# quantum_AnalougeEngine_V6_1.net
KiCad netlist of a schematic drawn in EAGLE
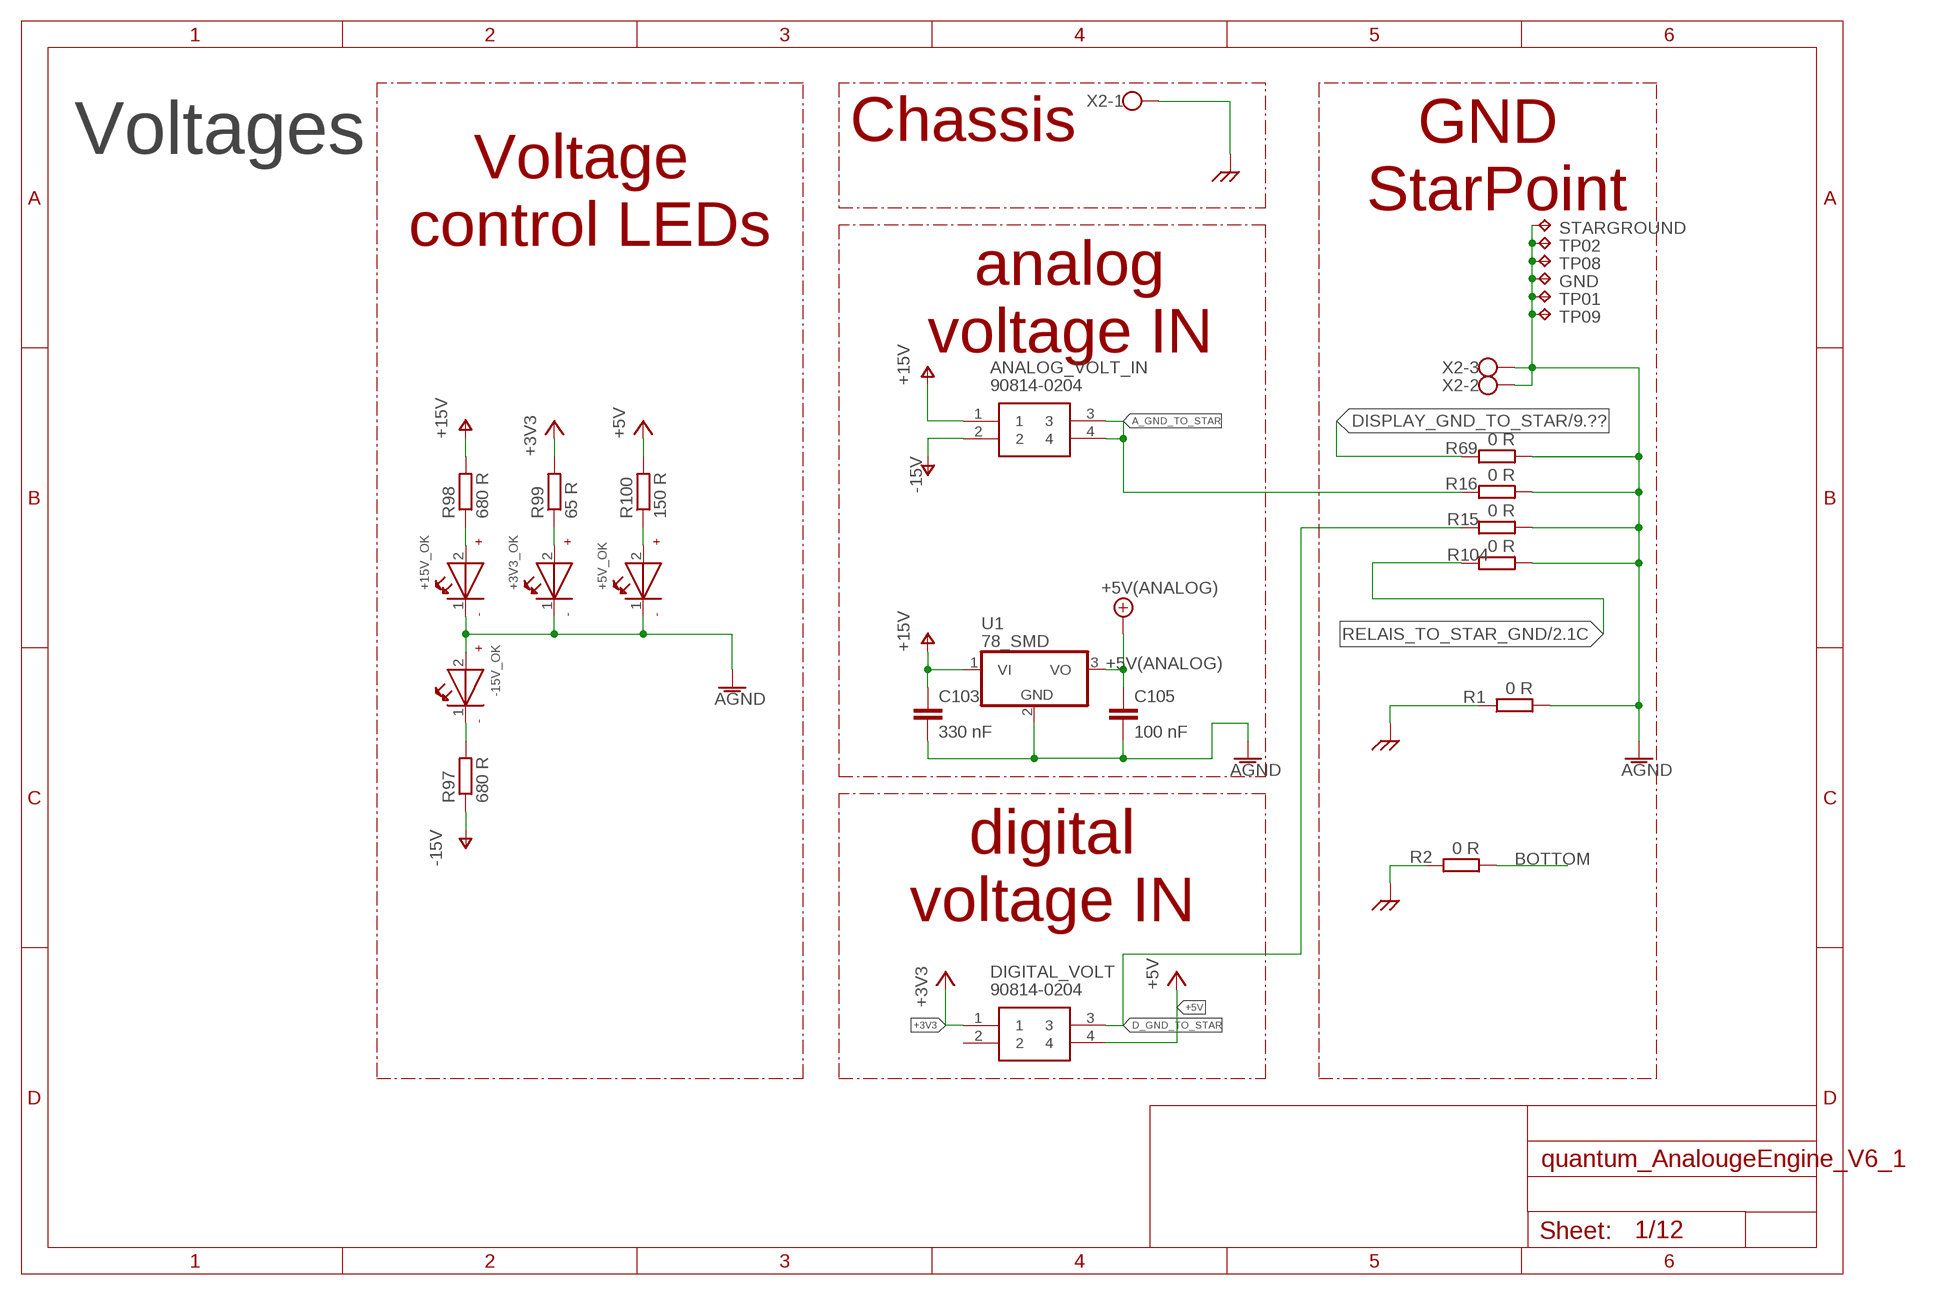
[diagram p0: schematic, sheet 1]
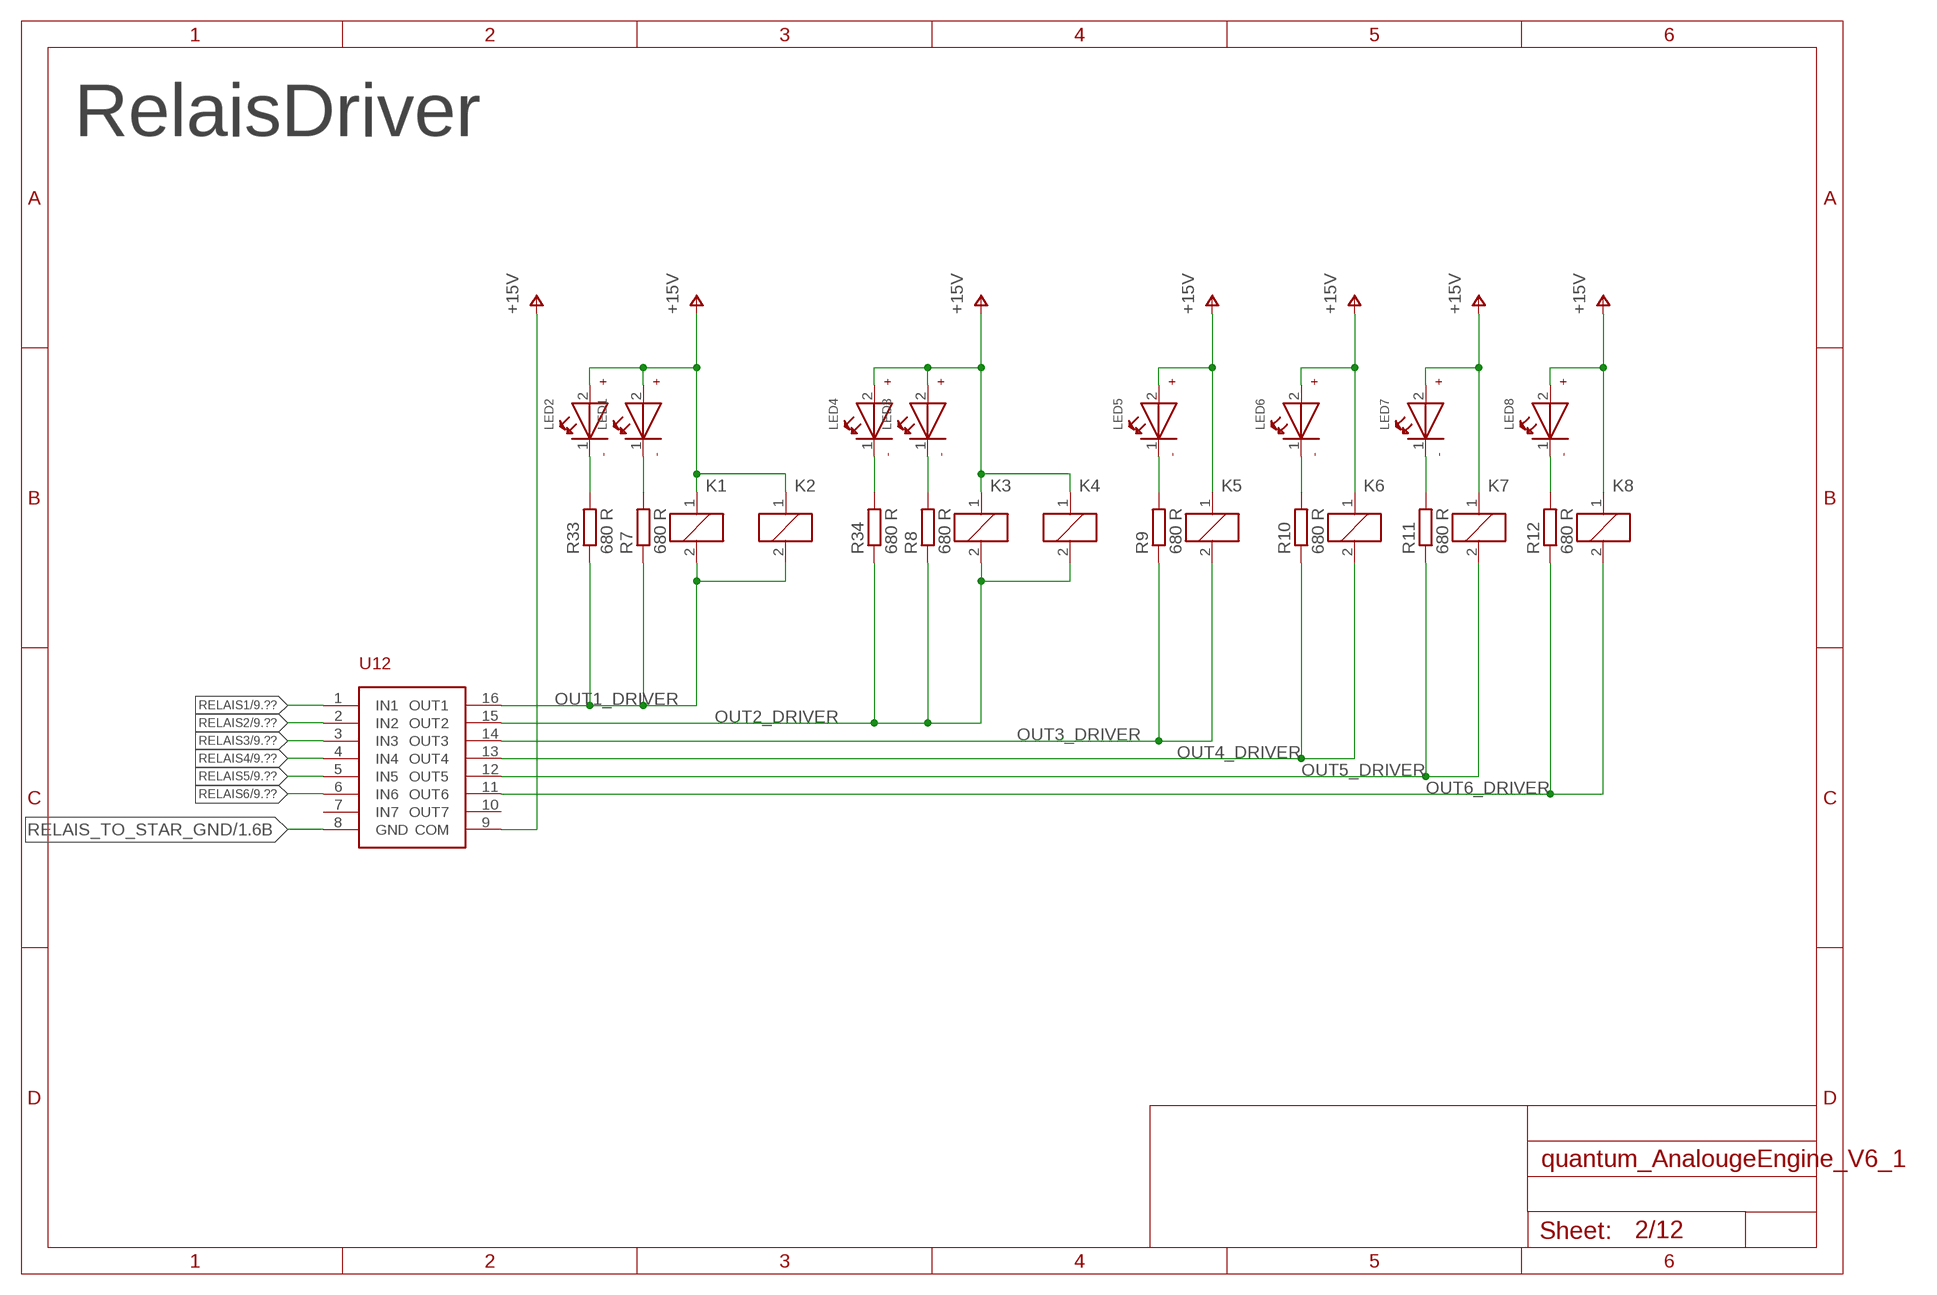
[diagram p1: schematic, sheet 2]
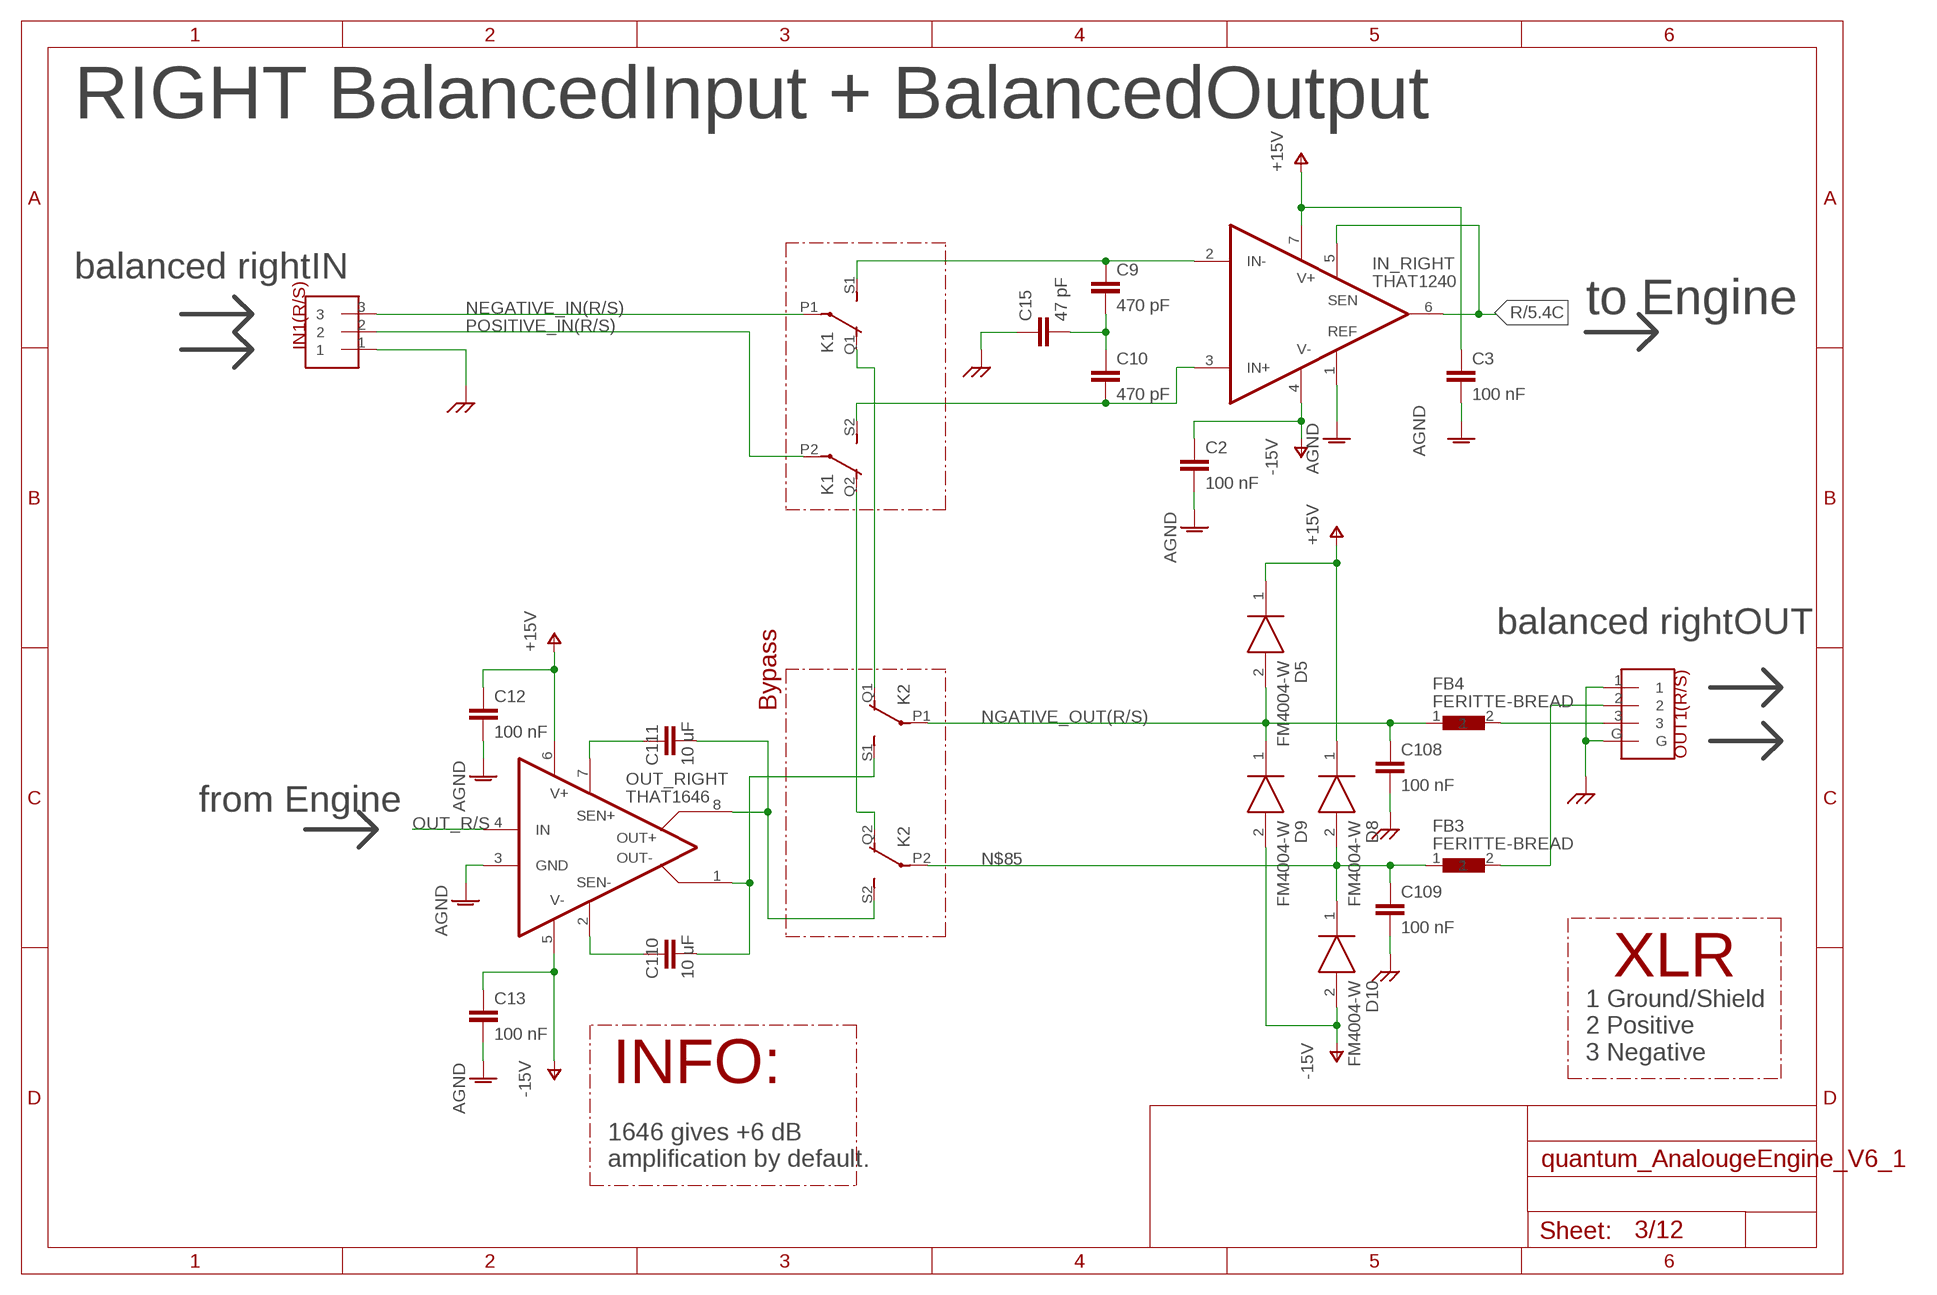
[diagram p2: schematic, sheet 3]
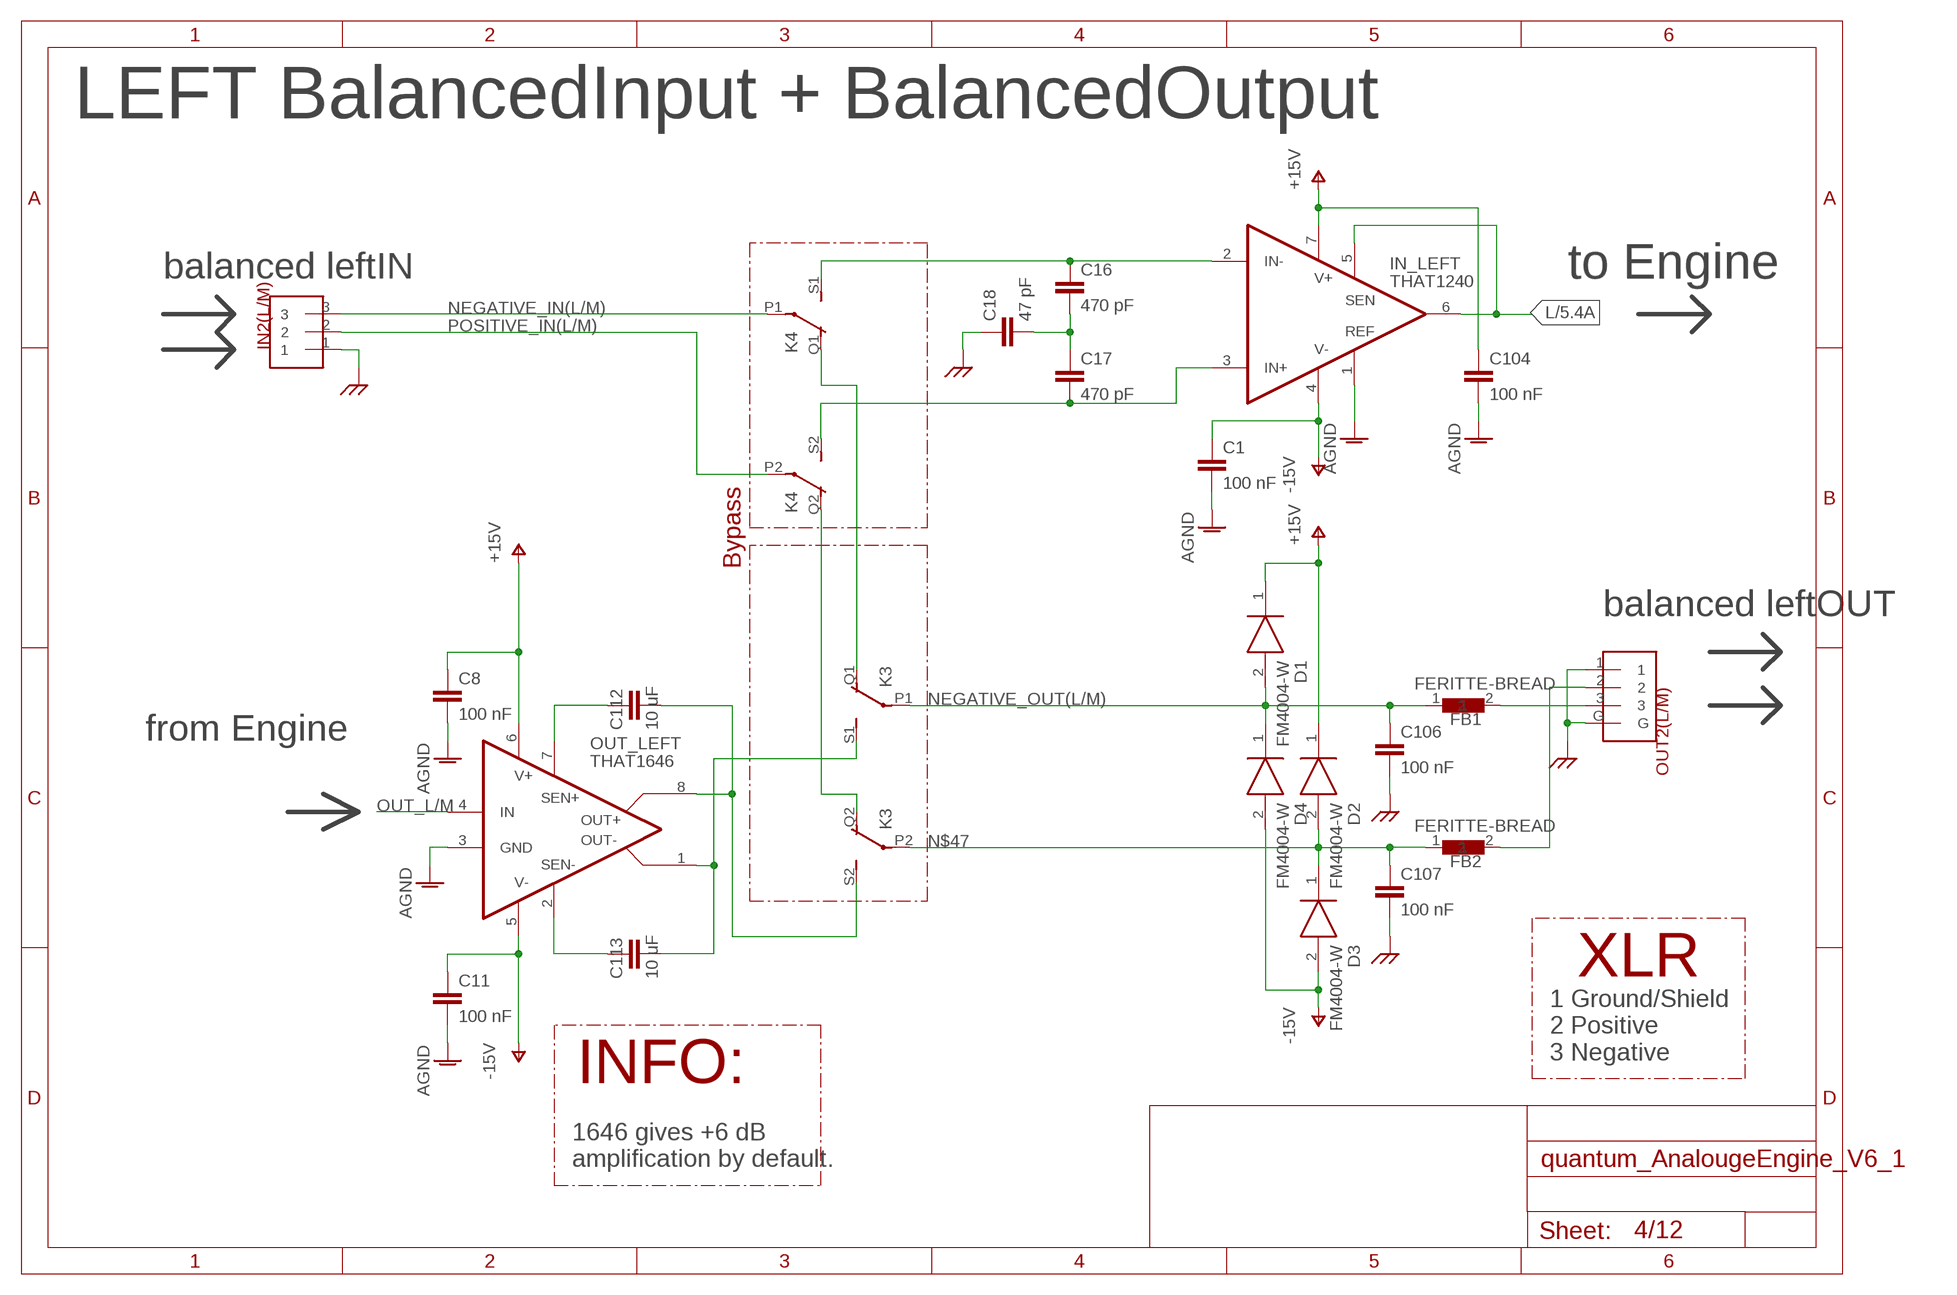
[diagram p3: schematic, sheet 4]
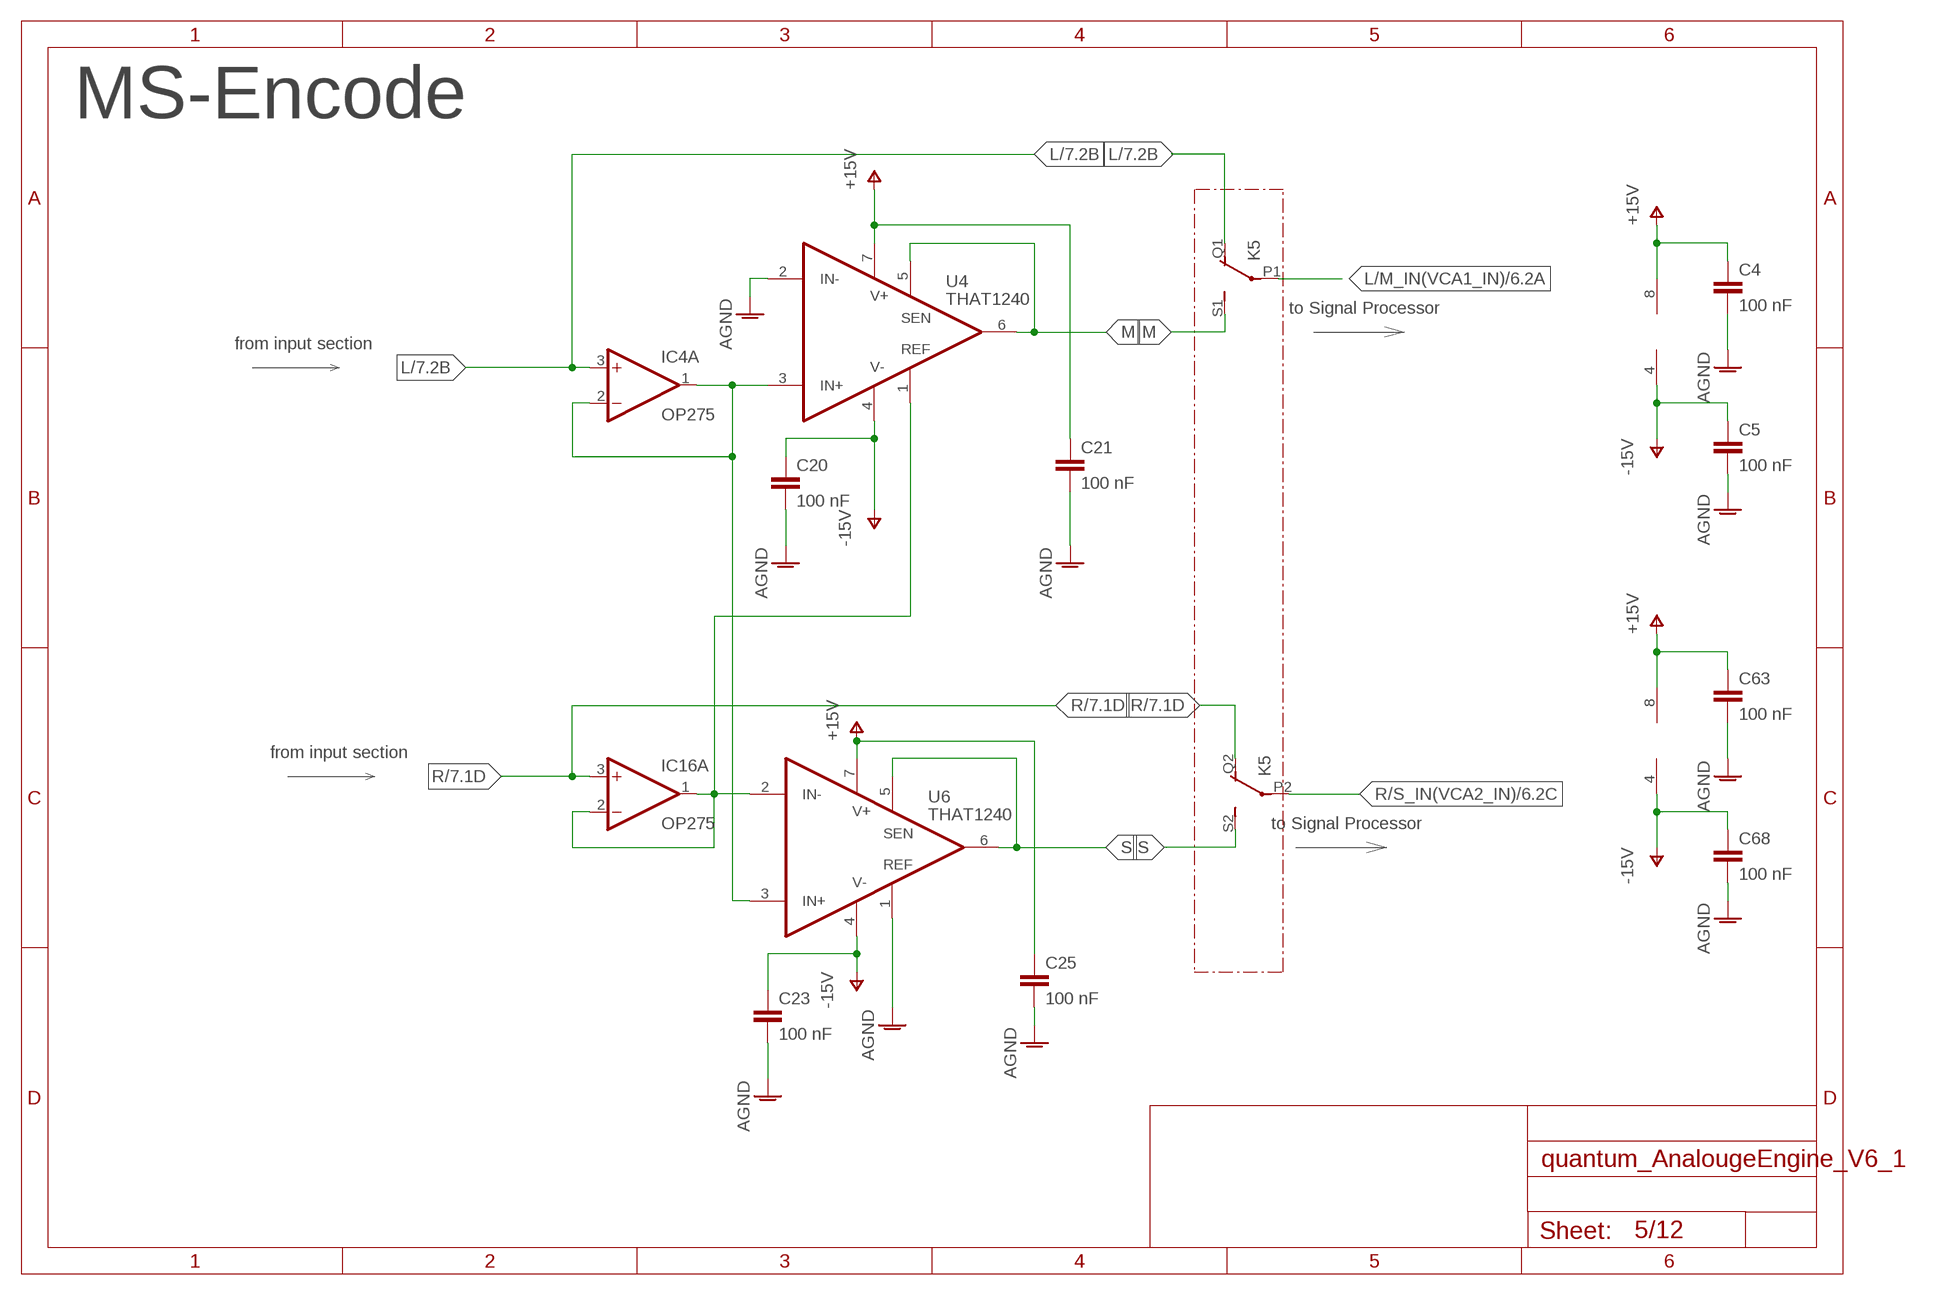
[diagram p4: schematic, sheet 5]
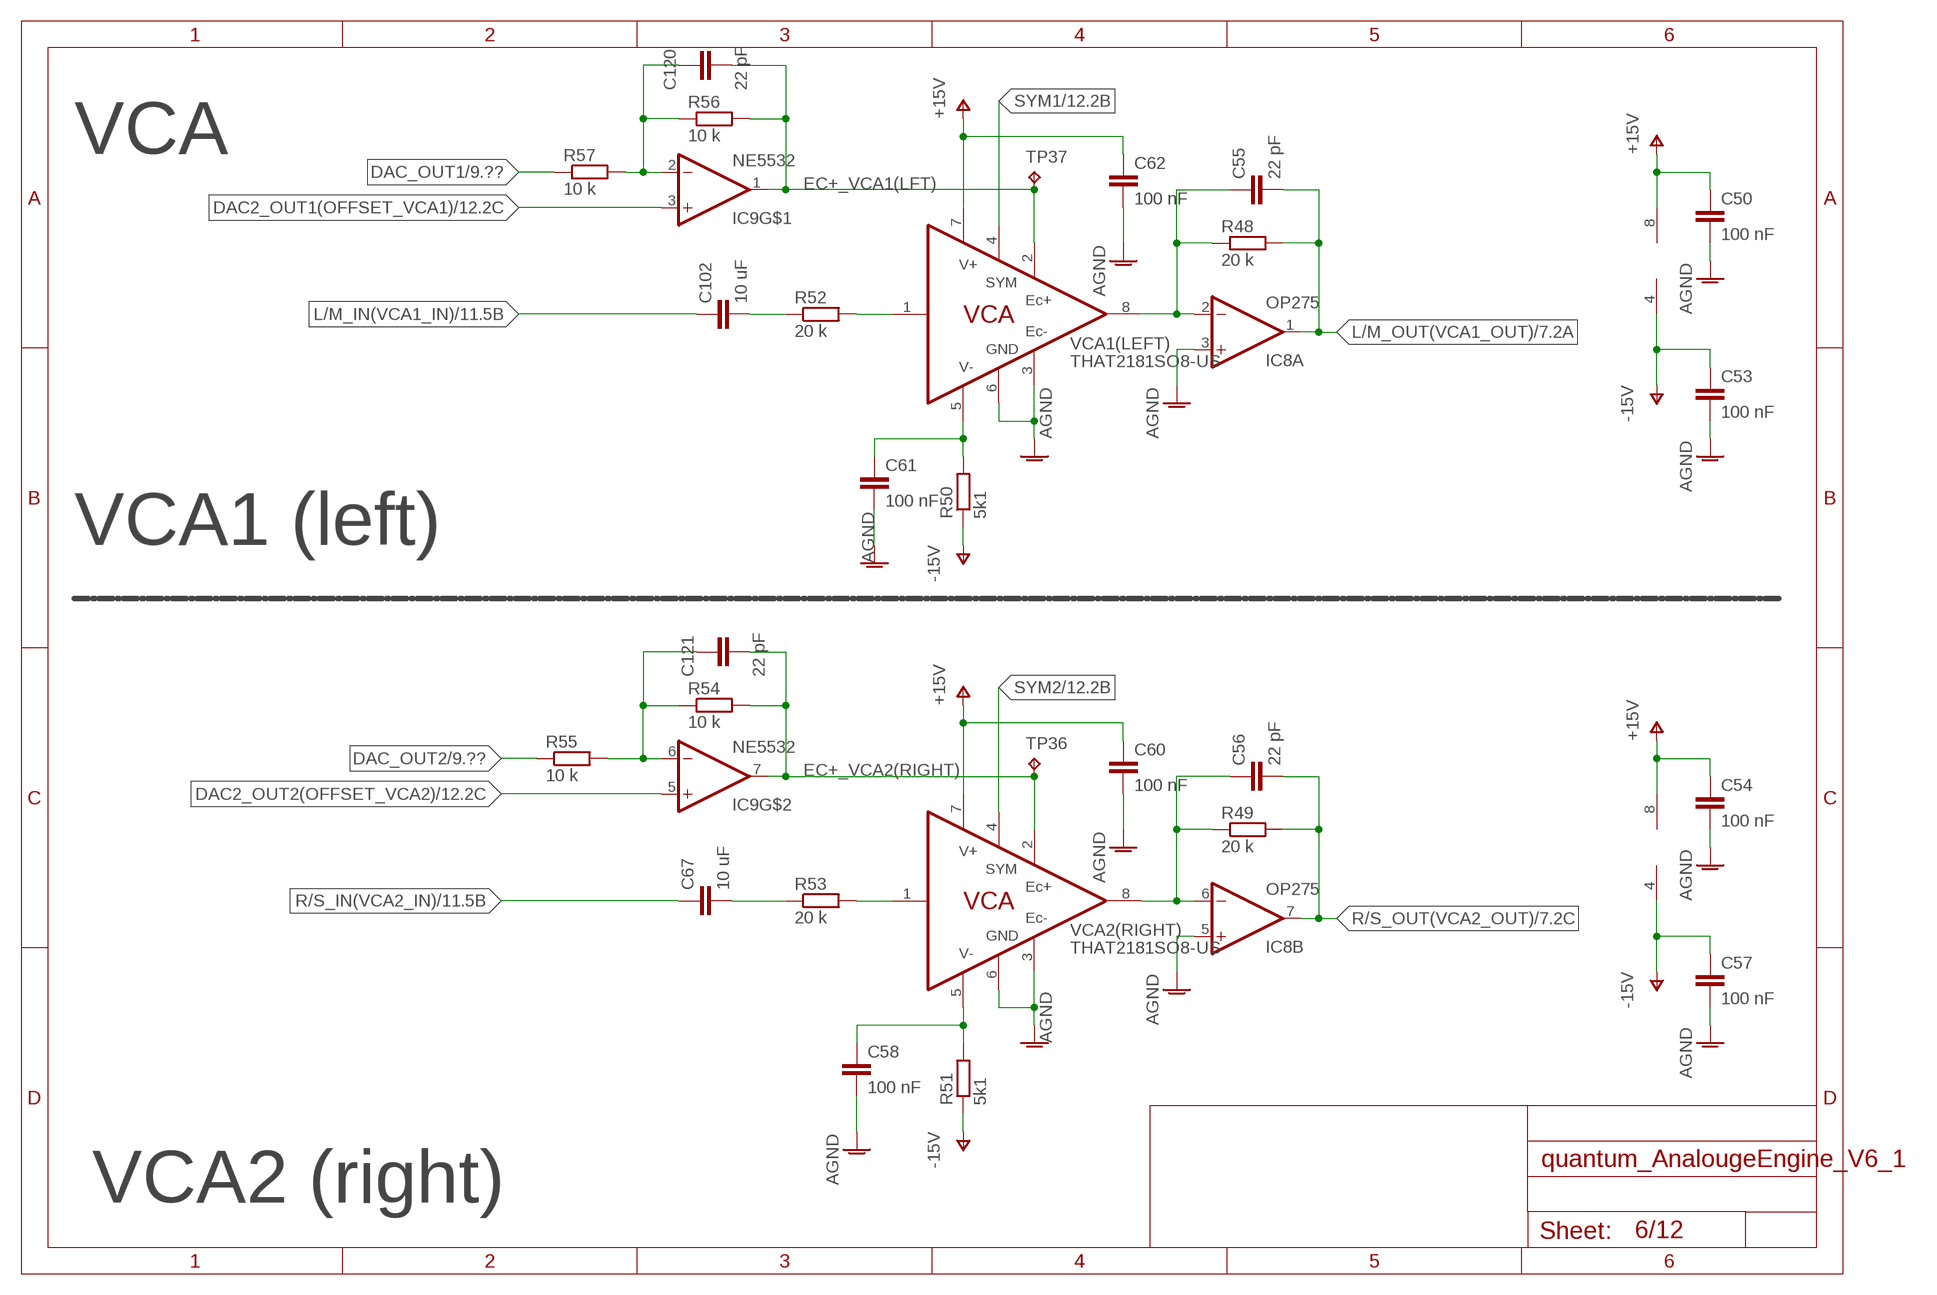
[diagram p5: schematic, sheet 6]
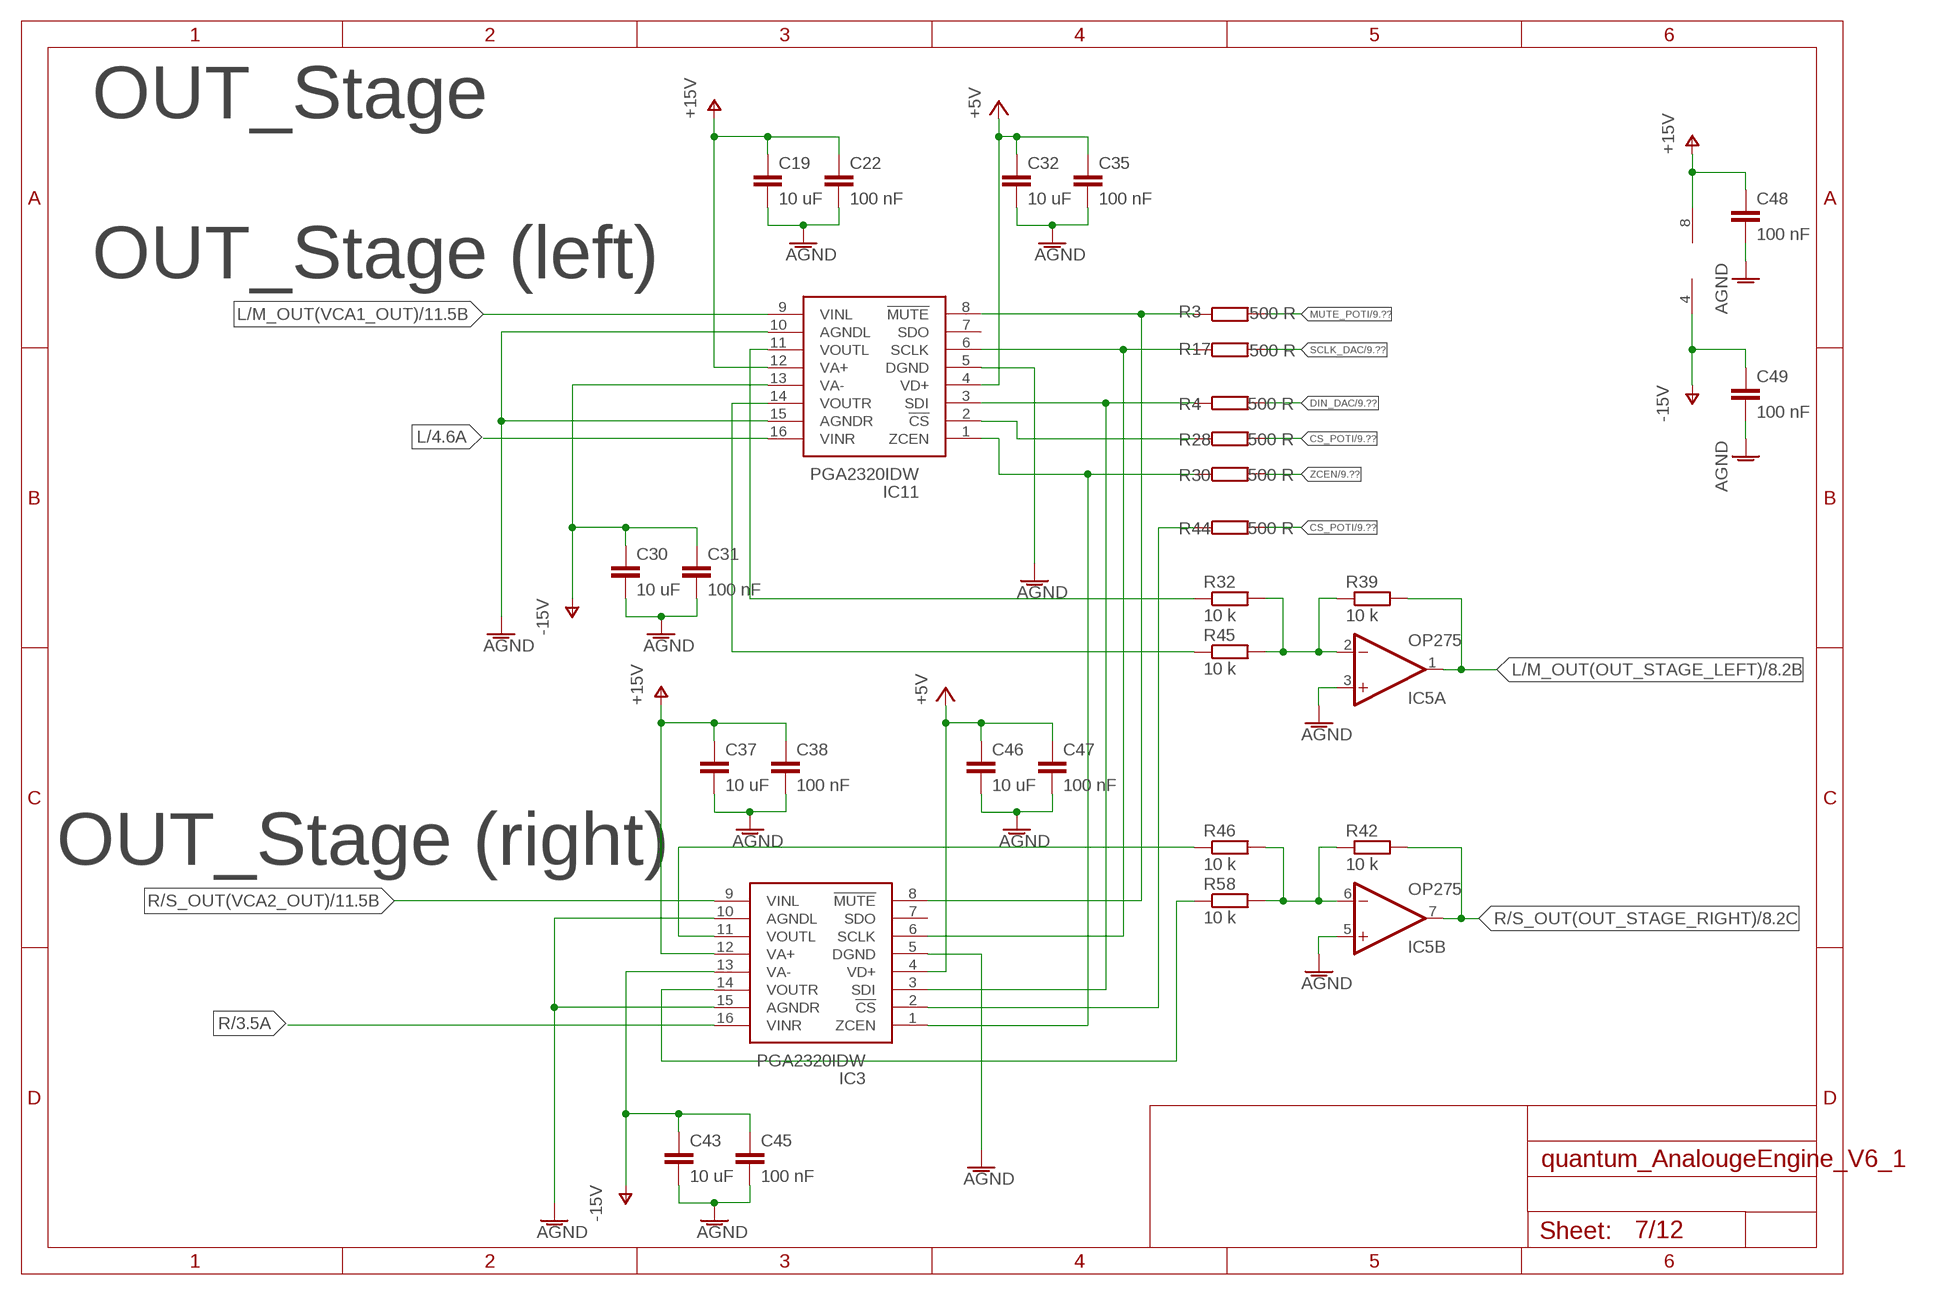
[diagram p6: schematic, sheet 7]
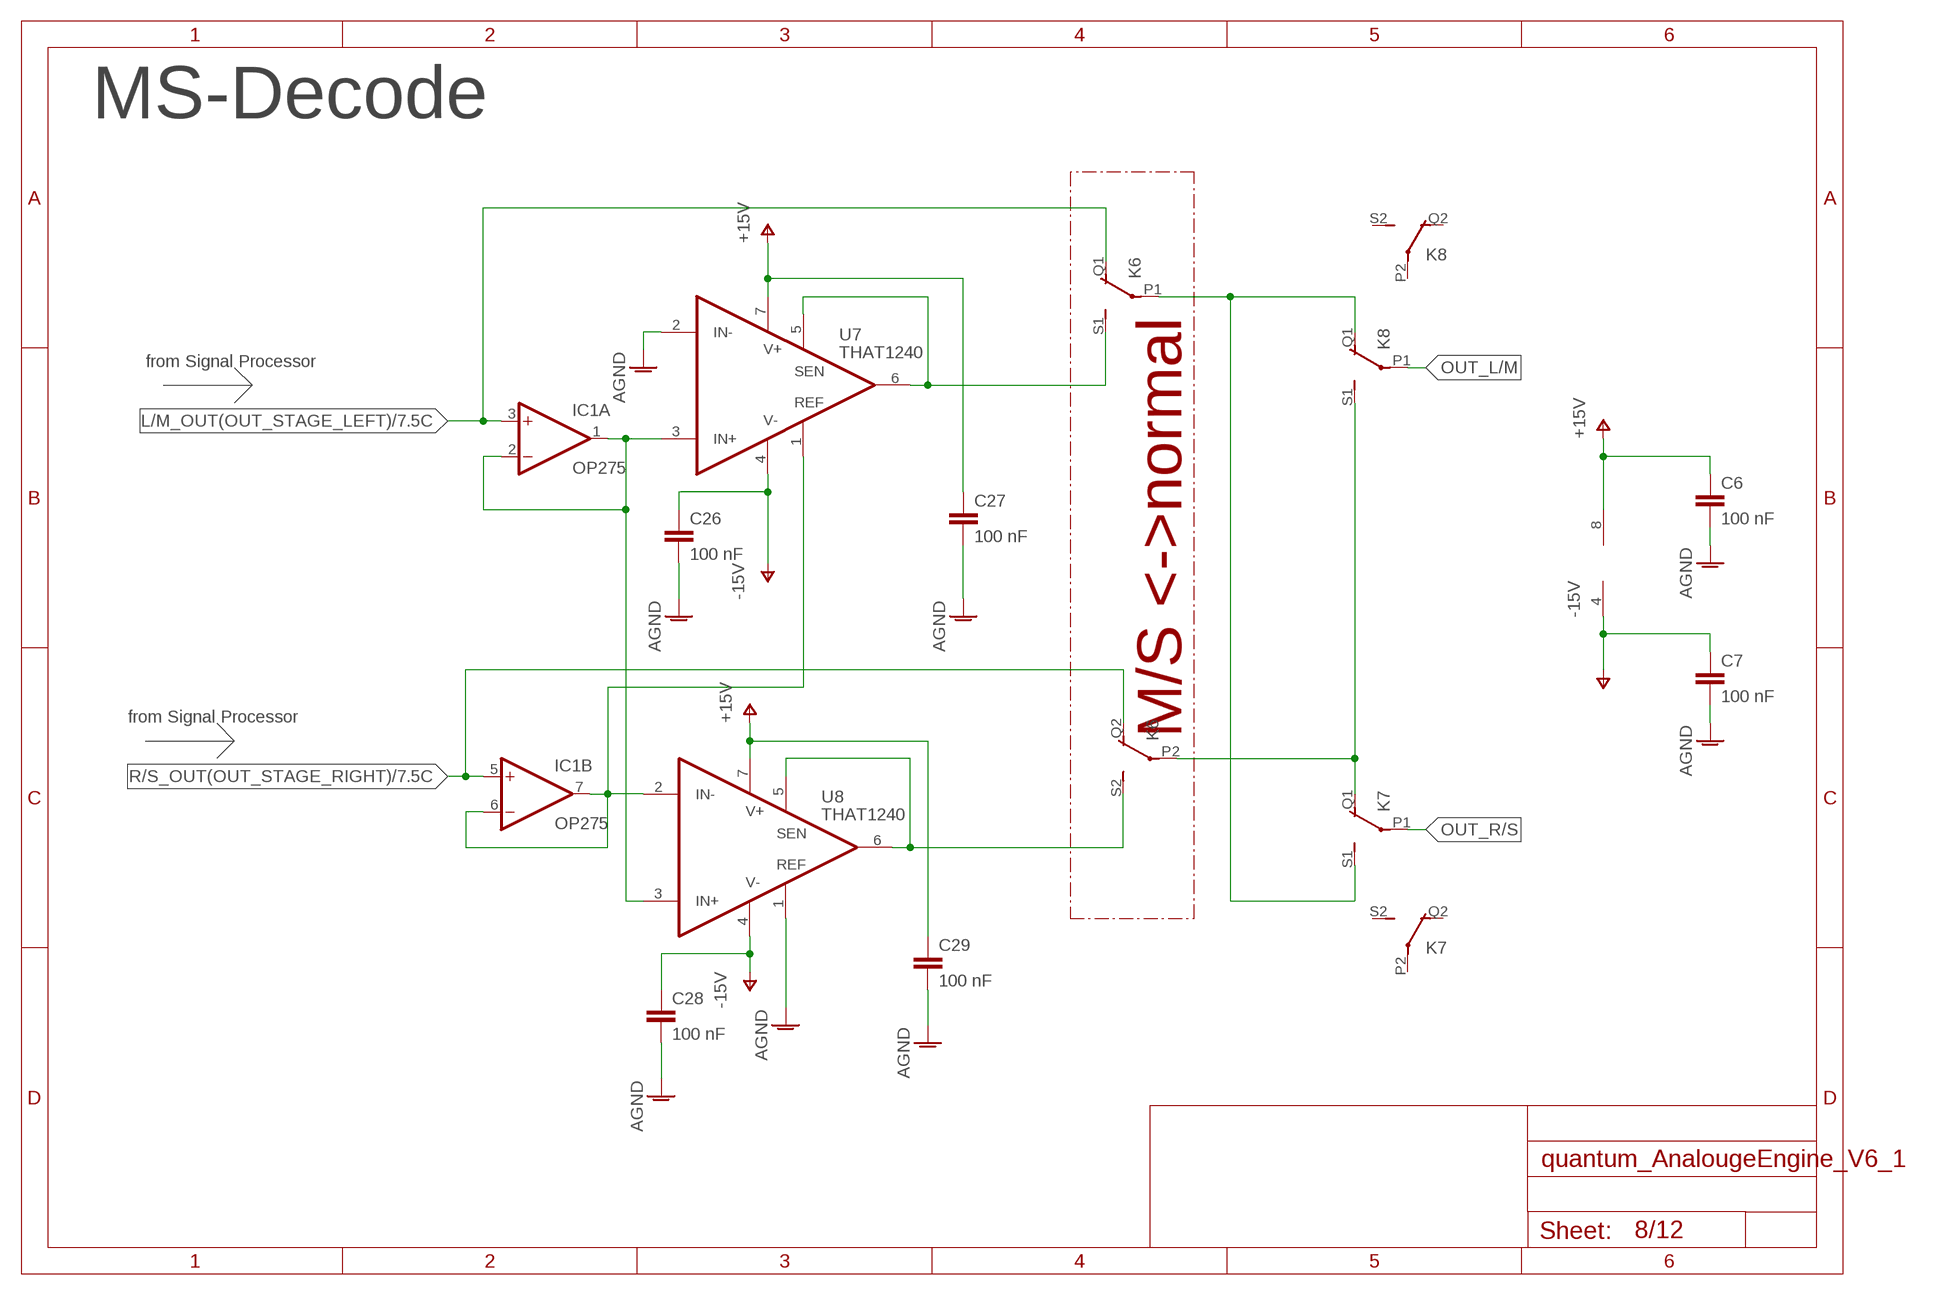
[diagram p7: schematic, sheet 8]
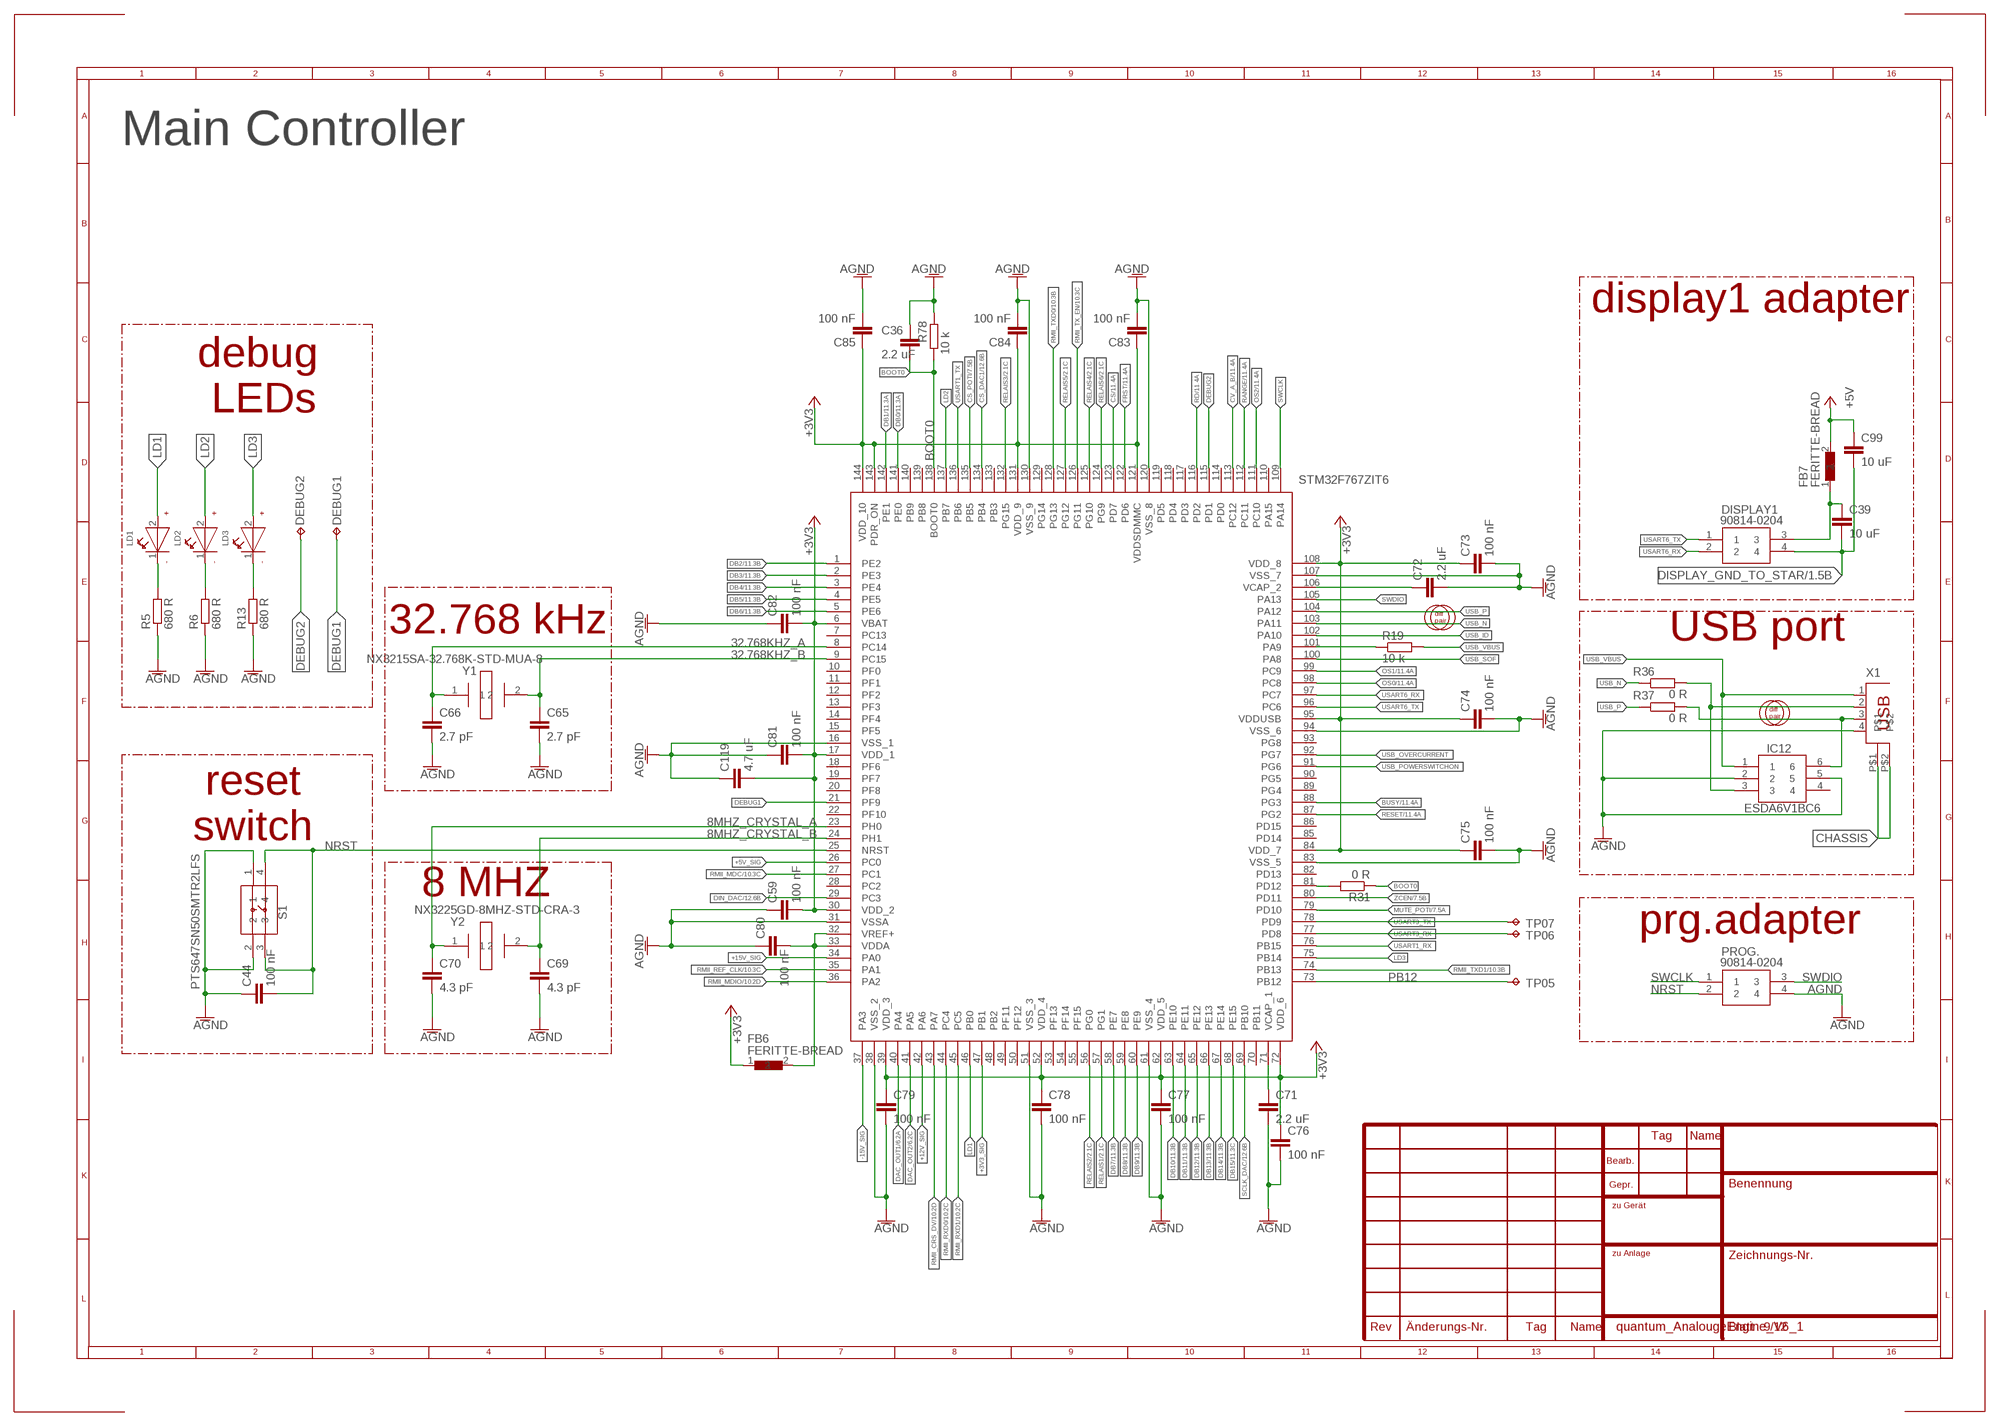
[diagram p8: schematic, sheet 9]
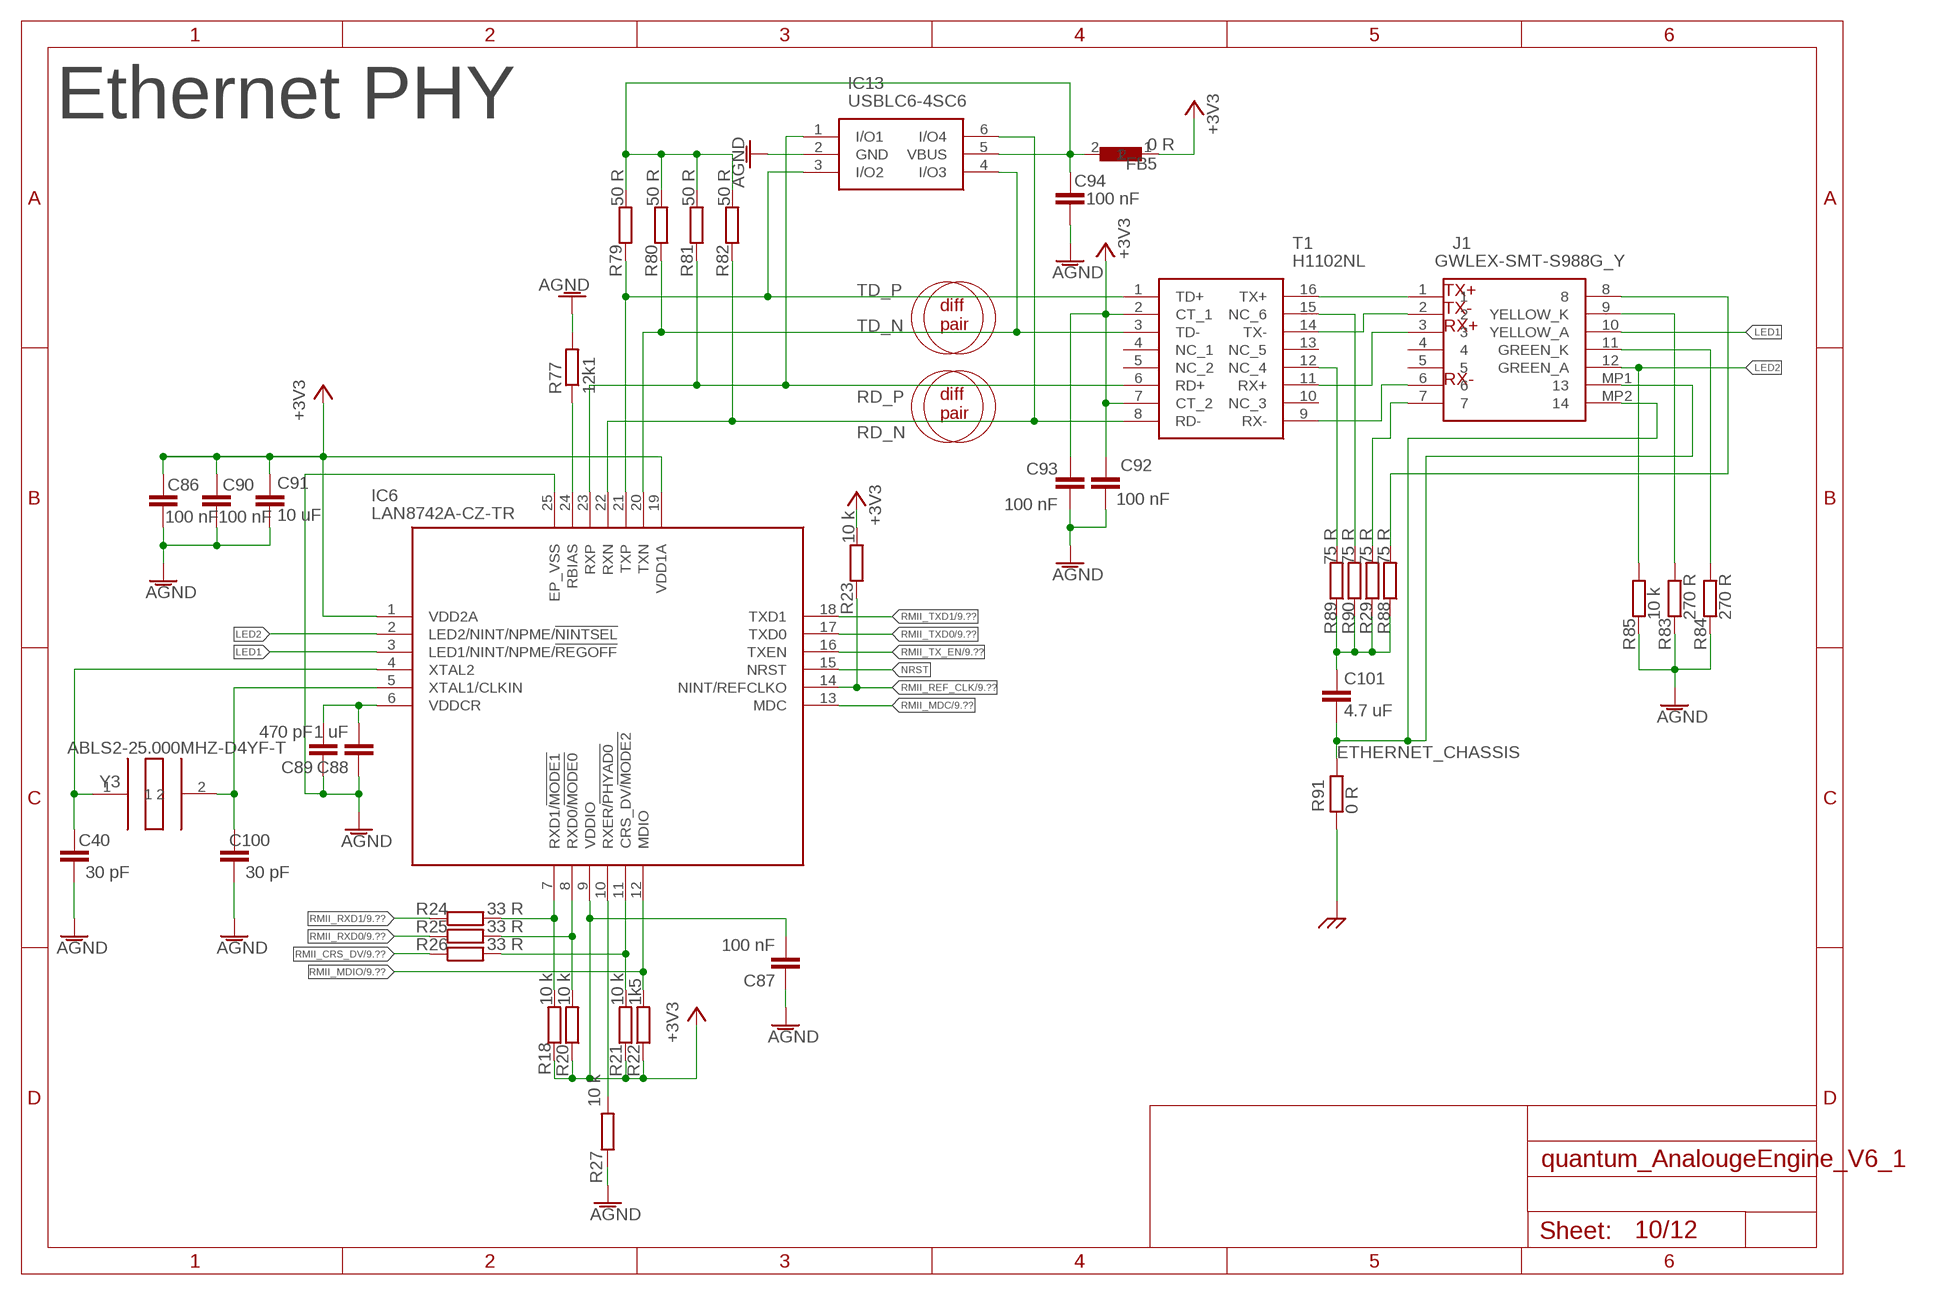
[diagram p9: schematic, sheet 10]
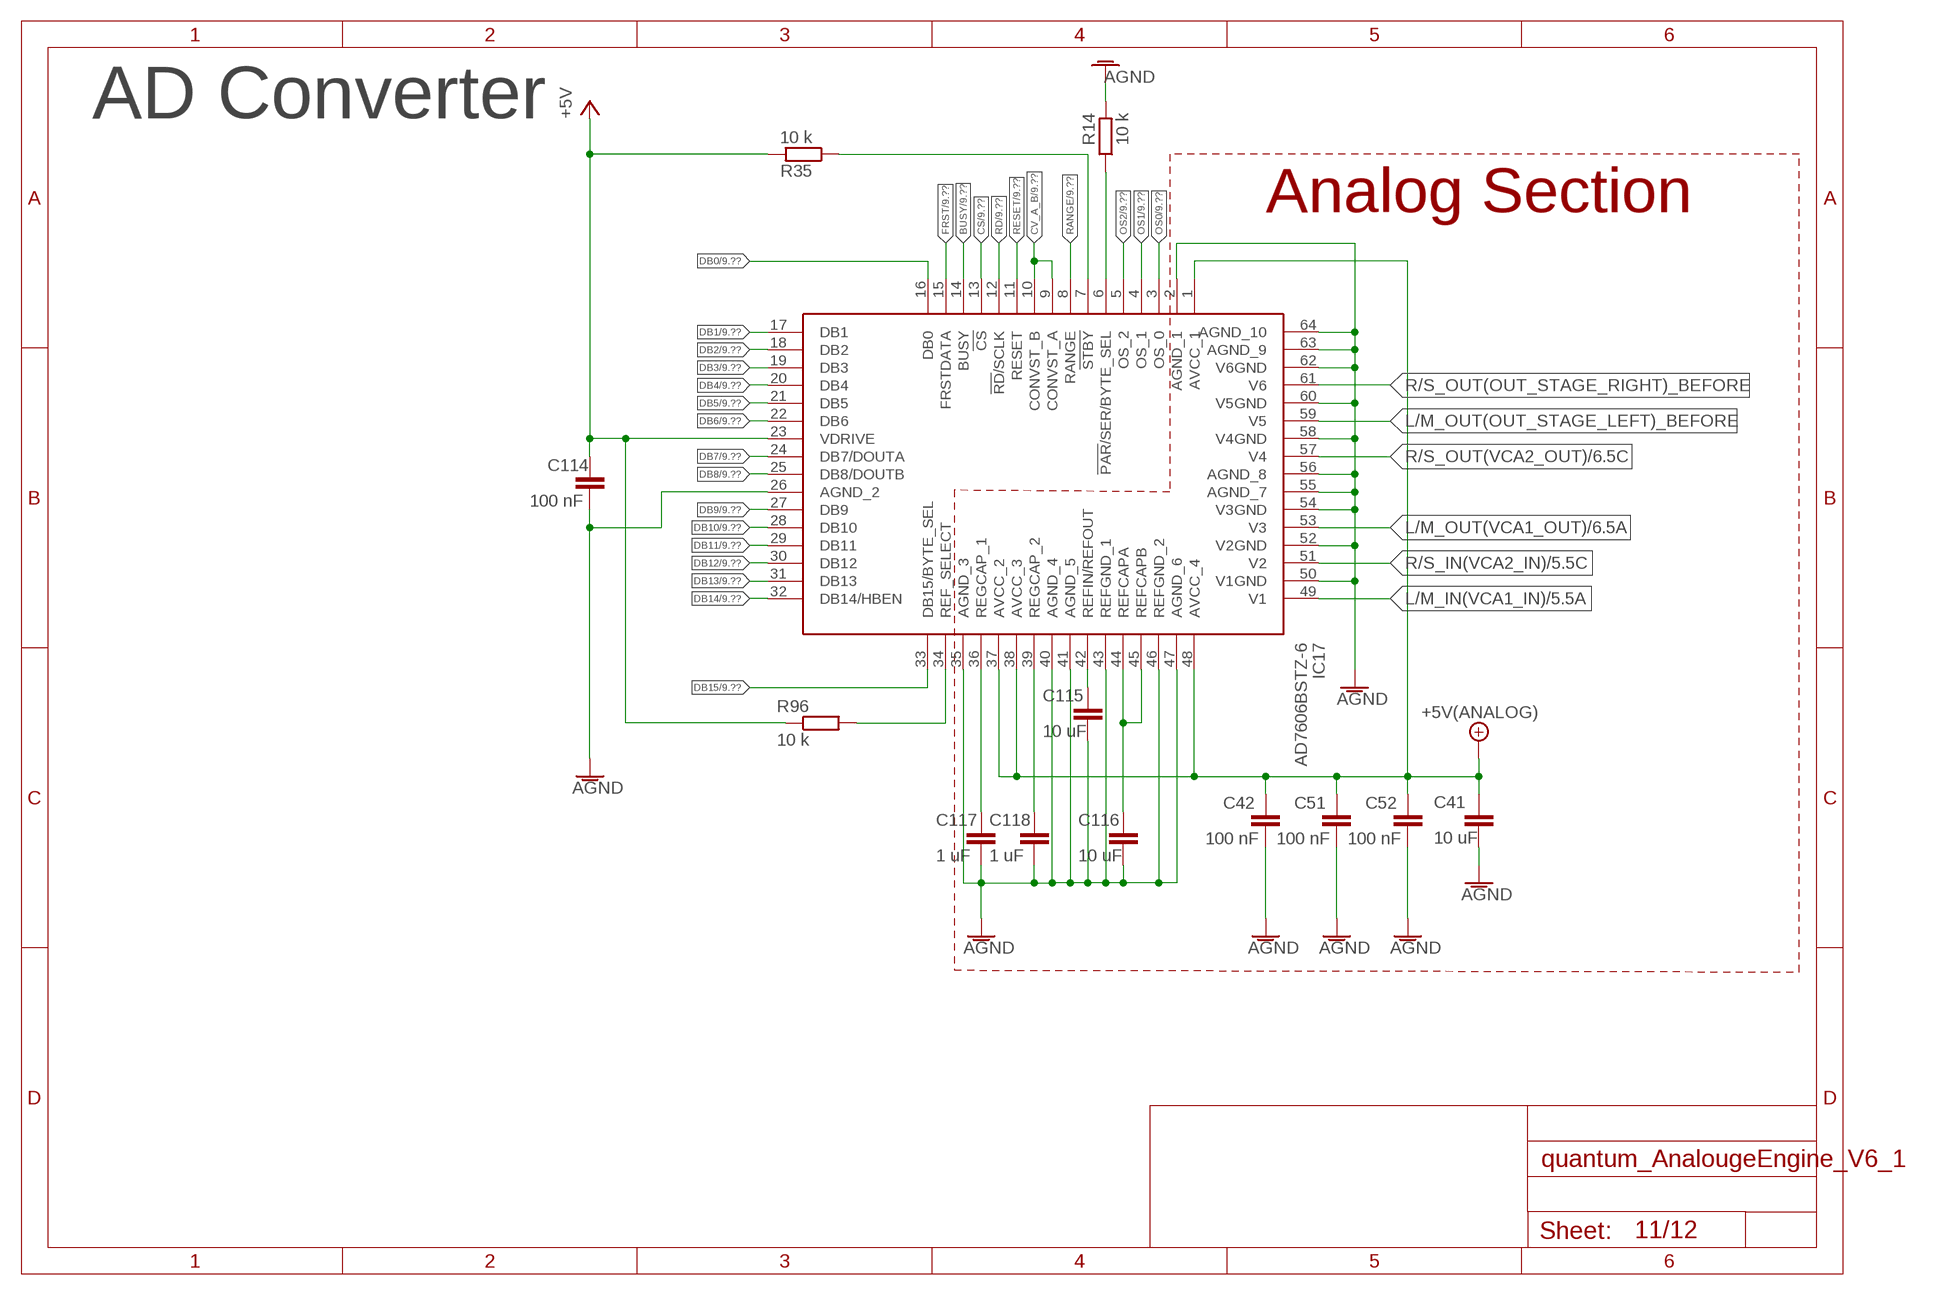
[diagram p10: schematic, sheet 11]
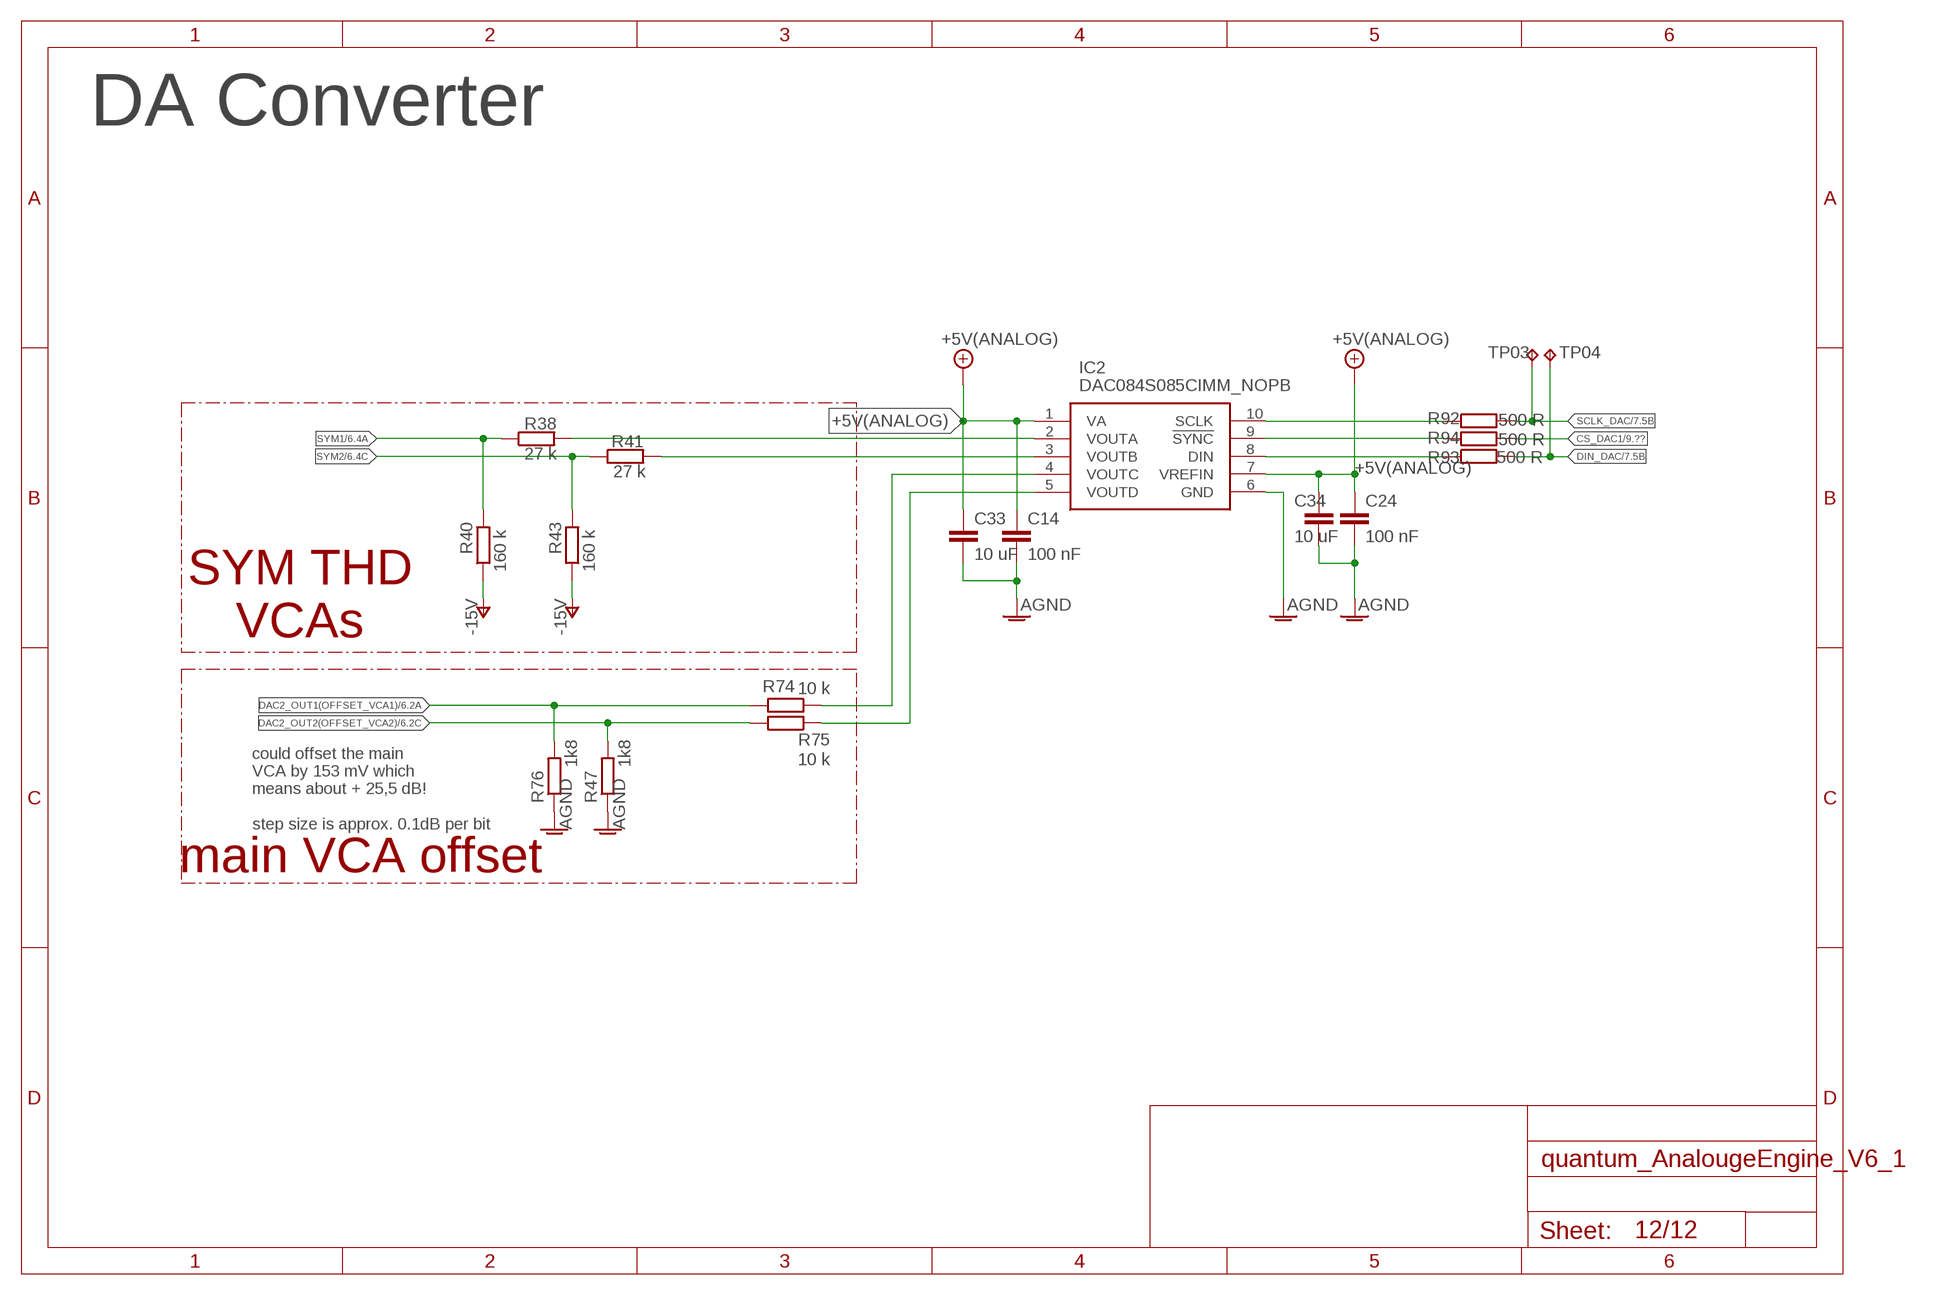
[diagram p11: schematic, sheet 12]

(export (version "E")
  (design (tool "Eeschema 10.0.6"))
  (components
    (comp (ref "C41")
      (value "10 uF")
      (footprint "eagle-import:C1206")
      (libsource (lib "eagle-import") (part "CAPACITOR_1206"))
    )
    (comp (ref "C42")
      (value "100 nF")
      (footprint "eagle-import:C0603")
      (libsource (lib "eagle-import") (part "CAPACITOR_0603"))
    )
    (comp (ref "C51")
      (value "100 nF")
      (footprint "eagle-import:C0603")
      (libsource (lib "eagle-import") (part "CAPACITOR_0603"))
    )
    (comp (ref "C52")
      (value "100 nF")
      (footprint "eagle-import:C0603")
      (libsource (lib "eagle-import") (part "CAPACITOR_0603"))
    )
    (comp (ref "C114")
      (value "100 nF")
      (footprint "eagle-import:C0603")
      (libsource (lib "eagle-import") (part "CAPACITOR_0603"))
    )
    (comp (ref "C115")
      (value "10 uF")
      (footprint "eagle-import:C1206")
      (libsource (lib "eagle-import") (part "CAPACITOR_1206"))
    )
    (comp (ref "C116")
      (value "10 uF")
      (footprint "eagle-import:C1206")
      (libsource (lib "eagle-import") (part "CAPACITOR_1206"))
    )
    (comp (ref "C117")
      (value "1 uF")
      (footprint "eagle-import:C0603")
      (libsource (lib "eagle-import") (part "CAPACITOR_0603"))
    )
    (comp (ref "C118")
      (value "1 uF")
      (footprint "eagle-import:C0603")
      (libsource (lib "eagle-import") (part "CAPACITOR_0603"))
    )
    (comp (ref "IC17")
      (value "AD7606BSTZ-6")
      (footprint "eagle-import:QFP50P1200X1200X160-64N")
      (fields (field (name "MOUSER_PART_NUMBER") "584-AD7606BSTZ-6"))
      (libsource (lib "eagle-import") (part "AD7606BSTZ-6"))
    )
    (comp (ref "R14")
      (value "10 k")
      (footprint "eagle-import:R0603")
      (libsource (lib "eagle-import") (part "RESISTOR_0603"))
    )
    (comp (ref "R35")
      (value "10 k")
      (footprint "eagle-import:R0603")
      (libsource (lib "eagle-import") (part "RESISTOR_0603"))
    )
    (comp (ref "R96")
      (value "10 k")
      (footprint "eagle-import:R0603")
      (libsource (lib "eagle-import") (part "RESISTOR_0603"))
    )
    (comp (ref "K1")
      (value "Relay")
      (footprint "eagle-import:351")
      (libsource (lib "eagle-import") (part "RELAY_EE2-5NU"))
    )
    (comp (ref "K2")
      (value "Relay")
      (footprint "eagle-import:351")
      (libsource (lib "eagle-import") (part "RELAY_EE2-5NU"))
    )
    (comp (ref "K3")
      (value "Relay")
      (footprint "eagle-import:351")
      (libsource (lib "eagle-import") (part "RELAY_EE2-5NU"))
    )
    (comp (ref "K4")
      (value "Relay")
      (footprint "eagle-import:351")
      (libsource (lib "eagle-import") (part "RELAY_EE2-5NU"))
    )
    (comp (ref "K5")
      (value "Relay")
      (footprint "eagle-import:351")
      (fields (field (name "SPICEPREFIX") "B"))
      (libsource (lib "eagle-import") (part "RELAY_EE2-5NU"))
    )
    (comp (ref "K6")
      (value "Relay")
      (footprint "eagle-import:351")
      (fields (field (name "SPICEPREFIX") "B"))
      (libsource (lib "eagle-import") (part "RELAY_EE2-5NU"))
    )
    (comp (ref "K7")
      (value "Relay")
      (footprint "eagle-import:351")
      (libsource (lib "eagle-import") (part "RELAY_EE2-5NU"))
    )
    (comp (ref "K8")
      (value "Relay")
      (footprint "eagle-import:351")
      (libsource (lib "eagle-import") (part "RELAY_EE2-5NU"))
    )
    (comp (ref "LED1")
      (value "LED_BLUE_SMD")
      (footprint "eagle-import:WL-SMCW_0603")
      (fields (field (name "MOUSER_PART_NUMBER") "..."))
      (libsource (lib "eagle-import") (part "LED_SMD_BLUE"))
    )
    (comp (ref "LED2")
      (value "LED_BLUE_SMD")
      (footprint "eagle-import:WL-SMCW_0603")
      (fields (field (name "MOUSER_PART_NUMBER") "..."))
      (libsource (lib "eagle-import") (part "LED_SMD_BLUE"))
    )
    (comp (ref "LED3")
      (value "LED_BLUE_SMD")
      (footprint "eagle-import:WL-SMCW_0603")
      (fields (field (name "MOUSER_PART_NUMBER") "..."))
      (libsource (lib "eagle-import") (part "LED_SMD_BLUE"))
    )
    (comp (ref "LED4")
      (value "LED_BLUE_SMD")
      (footprint "eagle-import:WL-SMCW_0603")
      (fields (field (name "MOUSER_PART_NUMBER") "..."))
      (libsource (lib "eagle-import") (part "LED_SMD_BLUE"))
    )
    (comp (ref "LED5")
      (value "LED_BLUE_SMD")
      (footprint "eagle-import:WL-SMCW_0603")
      (fields (field (name "MOUSER_PART_NUMBER") "..."))
      (libsource (lib "eagle-import") (part "LED_SMD_BLUE"))
    )
    (comp (ref "LED6")
      (value "LED_BLUE_SMD")
      (footprint "eagle-import:WL-SMCW_0603")
      (fields (field (name "MOUSER_PART_NUMBER") "..."))
      (libsource (lib "eagle-import") (part "LED_SMD_BLUE"))
    )
    (comp (ref "LED7")
      (value "LED_BLUE_SMD")
      (footprint "eagle-import:WL-SMCW_0603")
      (fields (field (name "MOUSER_PART_NUMBER") "..."))
      (libsource (lib "eagle-import") (part "LED_SMD_BLUE"))
    )
    (comp (ref "LED8")
      (value "LED_BLUE_SMD")
      (footprint "eagle-import:WL-SMCW_0603")
      (fields (field (name "MOUSER_PART_NUMBER") "..."))
      (libsource (lib "eagle-import") (part "LED_SMD_BLUE"))
    )
    (comp (ref "R7")
      (value "680 R")
      (footprint "eagle-import:R0603")
      (libsource (lib "eagle-import") (part "RESISTOR_0603"))
    )
    (comp (ref "R8")
      (value "680 R")
      (footprint "eagle-import:R0603")
      (libsource (lib "eagle-import") (part "RESISTOR_0603"))
    )
    (comp (ref "R9")
      (value "680 R")
      (footprint "eagle-import:R0603")
      (libsource (lib "eagle-import") (part "RESISTOR_0603"))
    )
    (comp (ref "R10")
      (value "680 R")
      (footprint "eagle-import:R0603")
      (libsource (lib "eagle-import") (part "RESISTOR_0603"))
    )
    (comp (ref "R11")
      (value "680 R")
      (footprint "eagle-import:R0603")
      (libsource (lib "eagle-import") (part "RESISTOR_0603"))
    )
    (comp (ref "R12")
      (value "680 R")
      (footprint "eagle-import:R0603")
      (libsource (lib "eagle-import") (part "RESISTOR_0603"))
    )
    (comp (ref "R33")
      (value "680 R")
      (footprint "eagle-import:R0603")
      (libsource (lib "eagle-import") (part "RESISTOR_0603"))
    )
    (comp (ref "R34")
      (value "680 R")
      (footprint "eagle-import:R0603")
      (libsource (lib "eagle-import") (part "RESISTOR_0603"))
    )
    (comp (ref "U12")
      (value "ULN2003")
      (footprint "eagle-import:SOIC16")
      (libsource (lib "eagle-import") (part "ULN2003"))
    )
    (comp (ref "C2")
      (value "100 nF")
      (footprint "eagle-import:C0603")
      (libsource (lib "eagle-import") (part "CAPACITOR_0603"))
    )
    (comp (ref "C3")
      (value "100 nF")
      (footprint "eagle-import:C0603")
      (libsource (lib "eagle-import") (part "CAPACITOR_0603"))
    )
    (comp (ref "C9")
      (value "470 pF")
      (footprint "eagle-import:C0603")
      (libsource (lib "eagle-import") (part "CAPACITOR_0603"))
    )
    (comp (ref "C10")
      (value "470 pF")
      (footprint "eagle-import:C0603")
      (libsource (lib "eagle-import") (part "CAPACITOR_0603"))
    )
    (comp (ref "C12")
      (value "100 nF")
      (footprint "eagle-import:C0603")
      (libsource (lib "eagle-import") (part "CAPACITOR_0603"))
    )
    (comp (ref "C13")
      (value "100 nF")
      (footprint "eagle-import:C0603")
      (libsource (lib "eagle-import") (part "CAPACITOR_0603"))
    )
    (comp (ref "C15")
      (value "47 pF")
      (footprint "eagle-import:C0603")
      (libsource (lib "eagle-import") (part "CAPACITOR_0603"))
    )
    (comp (ref "C108")
      (value "100 nF")
      (footprint "eagle-import:C0603")
      (libsource (lib "eagle-import") (part "CAPACITOR_0603"))
    )
    (comp (ref "C109")
      (value "100 nF")
      (footprint "eagle-import:C0603")
      (libsource (lib "eagle-import") (part "CAPACITOR_0603"))
    )
    (comp (ref "C110")
      (value "10 uF")
      (footprint "eagle-import:C1206")
      (libsource (lib "eagle-import") (part "CAPACITOR_1206"))
    )
    (comp (ref "C111")
      (value "10 uF")
      (footprint "eagle-import:C1206")
      (libsource (lib "eagle-import") (part "CAPACITOR_1206"))
    )
    (comp (ref "D5")
      (value "FM4004-W")
      (footprint "eagle-import:DIONM5025X231N")
      (fields (field (name "MOUSER_PART_NUMBER") "583-FM4004"))
      (libsource (lib "eagle-import") (part "FM4004-W"))
    )
    (comp (ref "D8")
      (value "FM4004-W")
      (footprint "eagle-import:DIONM5025X231N")
      (fields (field (name "MOUSER_PART_NUMBER") "583-FM4004"))
      (libsource (lib "eagle-import") (part "FM4004-W"))
    )
    (comp (ref "D9")
      (value "FM4004-W")
      (footprint "eagle-import:DIONM5025X231N")
      (fields (field (name "MOUSER_PART_NUMBER") "583-FM4004"))
      (libsource (lib "eagle-import") (part "FM4004-W"))
    )
    (comp (ref "D10")
      (value "FM4004-W")
      (footprint "eagle-import:DIONM5025X231N")
      (fields (field (name "MOUSER_PART_NUMBER") "583-FM4004"))
      (libsource (lib "eagle-import") (part "FM4004-W"))
    )
    (comp (ref "FB3")
      (value "FERITTE-BREAD")
      (footprint "eagle-import:BLM18KG102SH1J")
      (fields
        (field (name "MANUFACTURER_PART_NUMBER") "BLM18KG102SH1D")
        (field (name "MOUSER_PART_NUMBER") "81-BLM18KG102SH1D")
      )
      (libsource (lib "eagle-import") (part "FERITTE-BREAD"))
    )
    (comp (ref "FB4")
      (value "FERITTE-BREAD")
      (footprint "eagle-import:BLM18KG102SH1J")
      (fields
        (field (name "MANUFACTURER_PART_NUMBER") "BLM18KG102SH1D")
        (field (name "MOUSER_PART_NUMBER") "81-BLM18KG102SH1D")
      )
      (libsource (lib "eagle-import") (part "FERITTE-BREAD"))
    )
    (comp (ref "IN1(R/S)")
      (value "NEUTRIK_NC3FAH")
      (footprint "eagle-import:NEUTRIK_NC3FAH")
      (libsource (lib "eagle-import") (part "NEUTRIK_NC3FAH"))
    )
    (comp (ref "IN_RIGHT")
      (value "THAT1240")
      (footprint "eagle-import:SO08")
      (fields (field (name "MOUSER_PART_NUMBER") "887-1240S08-U"))
      (libsource (lib "eagle-import") (part "THAT1240SO8-USO8-U"))
    )
    (comp (ref "OUT1(R/S)")
      (value "NEUTRIK_NC3MAH")
      (footprint "eagle-import:NEUTRIK_NC3MAH")
      (libsource (lib "eagle-import") (part "NEUTRIK_NC3MAH"))
    )
    (comp (ref "OUT_RIGHT")
      (value "THAT1646")
      (footprint "eagle-import:SO08")
      (fields (field (name "MOUSER_PART_NUMBER") "887-1646S08-U"))
      (libsource (lib "eagle-import") (part "THAT1646SO8-USO8-U"))
    )
    (comp (ref "C1")
      (value "100 nF")
      (footprint "eagle-import:C0603")
      (libsource (lib "eagle-import") (part "CAPACITOR_0603"))
    )
    (comp (ref "C8")
      (value "100 nF")
      (footprint "eagle-import:C0603")
      (libsource (lib "eagle-import") (part "CAPACITOR_0603"))
    )
    (comp (ref "C11")
      (value "100 nF")
      (footprint "eagle-import:C0603")
      (libsource (lib "eagle-import") (part "CAPACITOR_0603"))
    )
    (comp (ref "C16")
      (value "470 pF")
      (footprint "eagle-import:C0603")
      (libsource (lib "eagle-import") (part "CAPACITOR_0603"))
    )
    (comp (ref "C17")
      (value "470 pF")
      (footprint "eagle-import:C0603")
      (libsource (lib "eagle-import") (part "CAPACITOR_0603"))
    )
    (comp (ref "C18")
      (value "47 pF")
      (footprint "eagle-import:C0603")
      (libsource (lib "eagle-import") (part "CAPACITOR_0603"))
    )
    (comp (ref "C104")
      (value "100 nF")
      (footprint "eagle-import:C0603")
      (libsource (lib "eagle-import") (part "CAPACITOR_0603"))
    )
    (comp (ref "C106")
      (value "100 nF")
      (footprint "eagle-import:C0603")
      (libsource (lib "eagle-import") (part "CAPACITOR_0603"))
    )
    (comp (ref "C107")
      (value "100 nF")
      (footprint "eagle-import:C0603")
      (libsource (lib "eagle-import") (part "CAPACITOR_0603"))
    )
    (comp (ref "C112")
      (value "10 uF")
      (footprint "eagle-import:C1206")
      (libsource (lib "eagle-import") (part "CAPACITOR_1206"))
    )
    (comp (ref "C113")
      (value "10 uF")
      (footprint "eagle-import:C1206")
      (libsource (lib "eagle-import") (part "CAPACITOR_1206"))
    )
    (comp (ref "D1")
      (value "FM4004-W")
      (footprint "eagle-import:DIONM5025X231N")
      (fields (field (name "MOUSER_PART_NUMBER") "583-FM4004"))
      (libsource (lib "eagle-import") (part "FM4004-W"))
    )
    (comp (ref "D2")
      (value "FM4004-W")
      (footprint "eagle-import:DIONM5025X231N")
      (fields (field (name "MOUSER_PART_NUMBER") "583-FM4004"))
      (libsource (lib "eagle-import") (part "FM4004-W"))
    )
    (comp (ref "D3")
      (value "FM4004-W")
      (footprint "eagle-import:DIONM5025X231N")
      (fields (field (name "MOUSER_PART_NUMBER") "583-FM4004"))
      (libsource (lib "eagle-import") (part "FM4004-W"))
    )
    (comp (ref "D4")
      (value "FM4004-W")
      (footprint "eagle-import:DIONM5025X231N")
      (fields (field (name "MOUSER_PART_NUMBER") "583-FM4004"))
      (libsource (lib "eagle-import") (part "FM4004-W"))
    )
    (comp (ref "FB1")
      (value "FERITTE-BREAD")
      (footprint "eagle-import:BLM18KG102SH1J")
      (fields
        (field (name "MANUFACTURER_PART_NUMBER") "BLM18KG102SH1D")
        (field (name "MOUSER_PART_NUMBER") "81-BLM18KG102SH1D")
      )
      (libsource (lib "eagle-import") (part "FERITTE-BREAD"))
    )
    (comp (ref "FB2")
      (value "FERITTE-BREAD")
      (footprint "eagle-import:BLM18KG102SH1J")
      (fields
        (field (name "MANUFACTURER_PART_NUMBER") "BLM18KG102SH1D")
        (field (name "MOUSER_PART_NUMBER") "81-BLM18KG102SH1D")
      )
      (libsource (lib "eagle-import") (part "FERITTE-BREAD"))
    )
    (comp (ref "IN2(L/M)")
      (value "NEUTRIK_NC3FAH")
      (footprint "eagle-import:NEUTRIK_NC3FAH")
      (libsource (lib "eagle-import") (part "NEUTRIK_NC3FAH"))
    )
    (comp (ref "IN_LEFT")
      (value "THAT1240")
      (footprint "eagle-import:SO08")
      (fields (field (name "MOUSER_PART_NUMBER") "887-1240S08-U"))
      (libsource (lib "eagle-import") (part "THAT1240SO8-USO8-U"))
    )
    (comp (ref "OUT2(L/M)")
      (value "NEUTRIK_NC3MAH")
      (footprint "eagle-import:NEUTRIK_NC3MAH")
      (libsource (lib "eagle-import") (part "NEUTRIK_NC3MAH"))
    )
    (comp (ref "OUT_LEFT")
      (value "THAT1646")
      (footprint "eagle-import:SO08")
      (fields (field (name "MOUSER_PART_NUMBER") "887-1646S08-U"))
      (libsource (lib "eagle-import") (part "THAT1646SO8-USO8-U"))
    )
    (comp (ref "C14")
      (value "100 nF")
      (footprint "eagle-import:C0603")
      (libsource (lib "eagle-import") (part "CAPACITOR_0603"))
    )
    (comp (ref "C24")
      (value "100 nF")
      (footprint "eagle-import:C0603")
      (libsource (lib "eagle-import") (part "CAPACITOR_0603"))
    )
    (comp (ref "C33")
      (value "10 uF")
      (footprint "eagle-import:C1206")
      (libsource (lib "eagle-import") (part "CAPACITOR_1206"))
    )
    (comp (ref "C34")
      (value "10 uF")
      (footprint "eagle-import:C1206")
      (libsource (lib "eagle-import") (part "CAPACITOR_1206"))
    )
    (comp (ref "IC2")
      (value "DAC084S085CIMM_NOPB")
      (footprint "eagle-import:SOP50P490X110-10N")
      (fields (field (name "MOUSER_PART_NUMBER") "926-DAC084S085CIMMNO"))
      (libsource (lib "eagle-import") (part "DAC084S085CIMM_NOPB"))
    )
    (comp (ref "R38")
      (value "27 k")
      (footprint "eagle-import:R0603")
      (libsource (lib "eagle-import") (part "RESISTOR_0603"))
    )
    (comp (ref "R40")
      (value "160 k")
      (footprint "eagle-import:R0603")
      (libsource (lib "eagle-import") (part "RESISTOR_0603"))
    )
    (comp (ref "R41")
      (value "27 k")
      (footprint "eagle-import:R0603")
      (libsource (lib "eagle-import") (part "RESISTOR_0603"))
    )
    (comp (ref "R43")
      (value "160 k")
      (footprint "eagle-import:R0603")
      (libsource (lib "eagle-import") (part "RESISTOR_0603"))
    )
    (comp (ref "R47")
      (value "1k8")
      (footprint "eagle-import:R0603")
      (libsource (lib "eagle-import") (part "RESISTOR_0603"))
    )
    (comp (ref "R74")
      (value "10 k")
      (footprint "eagle-import:R0603")
      (libsource (lib "eagle-import") (part "RESISTOR_0603"))
    )
    (comp (ref "R75")
      (value "10 k")
      (footprint "eagle-import:R0603")
      (libsource (lib "eagle-import") (part "RESISTOR_0603"))
    )
    (comp (ref "R76")
      (value "1k8")
      (footprint "eagle-import:R0603")
      (libsource (lib "eagle-import") (part "RESISTOR_0603"))
    )
    (comp (ref "R92")
      (value "500 R")
      (footprint "eagle-import:R0603")
      (libsource (lib "eagle-import") (part "RESISTOR_0603"))
    )
    (comp (ref "R93")
      (value "500 R")
      (footprint "eagle-import:R0603")
      (libsource (lib "eagle-import") (part "RESISTOR_0603"))
    )
    (comp (ref "R94")
      (value "500 R")
      (footprint "eagle-import:R0603")
      (libsource (lib "eagle-import") (part "RESISTOR_0603"))
    )
    (comp (ref "TP03")
      (value "TPTHT")
      (footprint "eagle-import:THT_PIN")
      (libsource (lib "eagle-import") (part "TPTHT"))
    )
    (comp (ref "TP04")
      (value "TPTHT")
      (footprint "eagle-import:THT_PIN")
      (libsource (lib "eagle-import") (part "TPTHT"))
    )
    (comp (ref "C4")
      (value "100 nF")
      (footprint "eagle-import:C0603")
      (libsource (lib "eagle-import") (part "CAPACITOR_0603"))
    )
    (comp (ref "C5")
      (value "100 nF")
      (footprint "eagle-import:C0603")
      (libsource (lib "eagle-import") (part "CAPACITOR_0603"))
    )
    (comp (ref "C20")
      (value "100 nF")
      (footprint "eagle-import:C0603")
      (libsource (lib "eagle-import") (part "CAPACITOR_0603"))
    )
    (comp (ref "C21")
      (value "100 nF")
      (footprint "eagle-import:C0603")
      (libsource (lib "eagle-import") (part "CAPACITOR_0603"))
    )
    (comp (ref "C23")
      (value "100 nF")
      (footprint "eagle-import:C0603")
      (libsource (lib "eagle-import") (part "CAPACITOR_0603"))
    )
    (comp (ref "C25")
      (value "100 nF")
      (footprint "eagle-import:C0603")
      (libsource (lib "eagle-import") (part "CAPACITOR_0603"))
    )
    (comp (ref "C63")
      (value "100 nF")
      (footprint "eagle-import:C0603")
      (libsource (lib "eagle-import") (part "CAPACITOR_0603"))
    )
    (comp (ref "C68")
      (value "100 nF")
      (footprint "eagle-import:C0603")
      (libsource (lib "eagle-import") (part "CAPACITOR_0603"))
    )
    (comp (ref "IC4")
      (value "OP275")
      (footprint "eagle-import:SOIC8")
      (libsource (lib "eagle-import") (part "OP275"))
    )
    (comp (ref "IC16")
      (value "OP275")
      (footprint "eagle-import:SOIC8")
      (libsource (lib "eagle-import") (part "OP275"))
    )
    (comp (ref "U4")
      (value "THAT1240")
      (footprint "eagle-import:SO08")
      (fields (field (name "MOUSER_PART_NUMBER") "887-1240S08-U"))
      (libsource (lib "eagle-import") (part "THAT1240SO8-USO8-U"))
    )
    (comp (ref "U6")
      (value "THAT1240")
      (footprint "eagle-import:SO08")
      (fields (field (name "MOUSER_PART_NUMBER") "887-1240S08-U"))
      (libsource (lib "eagle-import") (part "THAT1240SO8-USO8-U"))
    )
    (comp (ref "C50")
      (value "100 nF")
      (footprint "eagle-import:C0603")
      (libsource (lib "eagle-import") (part "CAPACITOR_0603"))
    )
    (comp (ref "C53")
      (value "100 nF")
      (footprint "eagle-import:C0603")
      (libsource (lib "eagle-import") (part "CAPACITOR_0603"))
    )
    (comp (ref "C54")
      (value "100 nF")
      (footprint "eagle-import:C0603")
      (libsource (lib "eagle-import") (part "CAPACITOR_0603"))
    )
    (comp (ref "C55")
      (value "22 pF")
      (footprint "eagle-import:C0603")
      (libsource (lib "eagle-import") (part "CAPACITOR_0603"))
    )
    (comp (ref "C56")
      (value "22 pF")
      (footprint "eagle-import:C0603")
      (libsource (lib "eagle-import") (part "CAPACITOR_0603"))
    )
    (comp (ref "C57")
      (value "100 nF")
      (footprint "eagle-import:C0603")
      (libsource (lib "eagle-import") (part "CAPACITOR_0603"))
    )
    (comp (ref "C58")
      (value "100 nF")
      (footprint "eagle-import:C0603")
      (libsource (lib "eagle-import") (part "CAPACITOR_0603"))
    )
    (comp (ref "C60")
      (value "100 nF")
      (footprint "eagle-import:C0603")
      (libsource (lib "eagle-import") (part "CAPACITOR_0603"))
    )
    (comp (ref "C61")
      (value "100 nF")
      (footprint "eagle-import:C0603")
      (libsource (lib "eagle-import") (part "CAPACITOR_0603"))
    )
    (comp (ref "C62")
      (value "100 nF")
      (footprint "eagle-import:C0603")
      (libsource (lib "eagle-import") (part "CAPACITOR_0603"))
    )
    (comp (ref "C67")
      (value "10 uF")
      (footprint "eagle-import:C1206")
      (libsource (lib "eagle-import") (part "CAPACITOR_1206"))
    )
    (comp (ref "C102")
      (value "10 uF")
      (footprint "eagle-import:C1206")
      (libsource (lib "eagle-import") (part "CAPACITOR_1206"))
    )
    (comp (ref "C120")
      (value "22 pF")
      (footprint "eagle-import:C0603")
      (libsource (lib "eagle-import") (part "CAPACITOR_0603"))
    )
    (comp (ref "C121")
      (value "22 pF")
      (footprint "eagle-import:C0603")
      (libsource (lib "eagle-import") (part "CAPACITOR_0603"))
    )
    (comp (ref "IC8")
      (value "OP275")
      (footprint "eagle-import:SOIC8")
      (libsource (lib "eagle-import") (part "OP275"))
    )
    (comp (ref "IC9")
      (value "NE5532")
      (footprint "eagle-import:SOIC8")
      (libsource (lib "eagle-import") (part "TL072"))
    )
    (comp (ref "R48")
      (value "20 k")
      (footprint "eagle-import:R0603")
      (libsource (lib "eagle-import") (part "RESISTOR_0603"))
    )
    (comp (ref "R49")
      (value "20 k")
      (footprint "eagle-import:R0603")
      (libsource (lib "eagle-import") (part "RESISTOR_0603"))
    )
    (comp (ref "R50")
      (value "5k1")
      (footprint "eagle-import:R0603")
      (libsource (lib "eagle-import") (part "RESISTOR_0603"))
    )
    (comp (ref "R51")
      (value "5k1")
      (footprint "eagle-import:R0603")
      (libsource (lib "eagle-import") (part "RESISTOR_0603"))
    )
    (comp (ref "R52")
      (value "20 k")
      (footprint "eagle-import:R0603")
      (libsource (lib "eagle-import") (part "RESISTOR_0603"))
    )
    (comp (ref "R53")
      (value "20 k")
      (footprint "eagle-import:R0603")
      (libsource (lib "eagle-import") (part "RESISTOR_0603"))
    )
    (comp (ref "R54")
      (value "10 k")
      (footprint "eagle-import:R0603")
      (libsource (lib "eagle-import") (part "RESISTOR_0603"))
    )
    (comp (ref "R55")
      (value "10 k")
      (footprint "eagle-import:R0603")
      (libsource (lib "eagle-import") (part "RESISTOR_0603"))
    )
    (comp (ref "R56")
      (value "10 k")
      (footprint "eagle-import:R0603")
      (libsource (lib "eagle-import") (part "RESISTOR_0603"))
    )
    (comp (ref "R57")
      (value "10 k")
      (footprint "eagle-import:R0603")
      (libsource (lib "eagle-import") (part "RESISTOR_0603"))
    )
    (comp (ref "TP36")
      (value "TPTHT")
      (footprint "eagle-import:THT_PIN")
      (libsource (lib "eagle-import") (part "TPTHT"))
    )
    (comp (ref "TP37")
      (value "TPTHT")
      (footprint "eagle-import:THT_PIN")
      (libsource (lib "eagle-import") (part "TPTHT"))
    )
    (comp (ref "VCA1(LEFT)")
      (value "THAT2181SO8-US")
      (footprint "eagle-import:SO08")
      (fields (field (name "MOUSER_PART_NUMBER") "887-2181CS08-U"))
      (libsource (lib "eagle-import") (part "THAT2181SSO8-U"))
    )
    (comp (ref "VCA2(RIGHT)")
      (value "THAT2181SO8-US")
      (footprint "eagle-import:SO08")
      (fields (field (name "MOUSER_PART_NUMBER") "887-2181CS08-U"))
      (libsource (lib "eagle-import") (part "THAT2181SSO8-U"))
    )
    (comp (ref "C19")
      (value "10 uF")
      (footprint "eagle-import:C1206")
      (libsource (lib "eagle-import") (part "CAPACITOR_1206"))
    )
    (comp (ref "C22")
      (value "100 nF")
      (footprint "eagle-import:C0603")
      (libsource (lib "eagle-import") (part "CAPACITOR_0603"))
    )
    (comp (ref "C30")
      (value "10 uF")
      (footprint "eagle-import:C1206")
      (libsource (lib "eagle-import") (part "CAPACITOR_1206"))
    )
    (comp (ref "C31")
      (value "100 nF")
      (footprint "eagle-import:C0603")
      (libsource (lib "eagle-import") (part "CAPACITOR_0603"))
    )
    (comp (ref "C32")
      (value "10 uF")
      (footprint "eagle-import:C1206")
      (libsource (lib "eagle-import") (part "CAPACITOR_1206"))
    )
    (comp (ref "C35")
      (value "100 nF")
      (footprint "eagle-import:C0603")
      (libsource (lib "eagle-import") (part "CAPACITOR_0603"))
    )
    (comp (ref "C37")
      (value "10 uF")
      (footprint "eagle-import:C1206")
      (libsource (lib "eagle-import") (part "CAPACITOR_1206"))
    )
    (comp (ref "C38")
      (value "100 nF")
      (footprint "eagle-import:C0603")
      (libsource (lib "eagle-import") (part "CAPACITOR_0603"))
    )
    (comp (ref "C43")
      (value "10 uF")
      (footprint "eagle-import:C1206")
      (libsource (lib "eagle-import") (part "CAPACITOR_1206"))
    )
    (comp (ref "C45")
      (value "100 nF")
      (footprint "eagle-import:C0603")
      (libsource (lib "eagle-import") (part "CAPACITOR_0603"))
    )
    (comp (ref "C46")
      (value "10 uF")
      (footprint "eagle-import:C1206")
      (libsource (lib "eagle-import") (part "CAPACITOR_1206"))
    )
    (comp (ref "C47")
      (value "100 nF")
      (footprint "eagle-import:C0603")
      (libsource (lib "eagle-import") (part "CAPACITOR_0603"))
    )
    (comp (ref "C48")
      (value "100 nF")
      (footprint "eagle-import:C0603")
      (libsource (lib "eagle-import") (part "CAPACITOR_0603"))
    )
    (comp (ref "C49")
      (value "100 nF")
      (footprint "eagle-import:C0603")
      (libsource (lib "eagle-import") (part "CAPACITOR_0603"))
    )
    (comp (ref "IC3")
      (value "PGA2320IDW")
      (footprint "eagle-import:SOIC127P1030X265-16N")
      (fields (field (name "MOUSER_PART_NUMBER") "595-PGA2320IDW"))
      (libsource (lib "eagle-import") (part "PGA2320IDW"))
    )
    (comp (ref "IC5")
      (value "OP275")
      (footprint "eagle-import:SOIC8")
      (libsource (lib "eagle-import") (part "OP275"))
    )
    (comp (ref "IC11")
      (value "PGA2320IDW")
      (footprint "eagle-import:SOIC127P1030X265-16N")
      (fields (field (name "MOUSER_PART_NUMBER") "595-PGA2320IDW"))
      (libsource (lib "eagle-import") (part "PGA2320IDW"))
    )
    (comp (ref "R3")
      (value "500 R")
      (footprint "eagle-import:R0603")
      (libsource (lib "eagle-import") (part "RESISTOR_0603"))
    )
    (comp (ref "R4")
      (value "500 R")
      (footprint "eagle-import:R0603")
      (libsource (lib "eagle-import") (part "RESISTOR_0603"))
    )
    (comp (ref "R17")
      (value "500 R")
      (footprint "eagle-import:R0603")
      (libsource (lib "eagle-import") (part "RESISTOR_0603"))
    )
    (comp (ref "R28")
      (value "500 R")
      (footprint "eagle-import:R0603")
      (libsource (lib "eagle-import") (part "RESISTOR_0603"))
    )
    (comp (ref "R30")
      (value "500 R")
      (footprint "eagle-import:R0603")
      (libsource (lib "eagle-import") (part "RESISTOR_0603"))
    )
    (comp (ref "R32")
      (value "10 k")
      (footprint "eagle-import:R0603")
      (libsource (lib "eagle-import") (part "RESISTOR_0603"))
    )
    (comp (ref "R39")
      (value "10 k")
      (footprint "eagle-import:R0603")
      (libsource (lib "eagle-import") (part "RESISTOR_0603"))
    )
    (comp (ref "R42")
      (value "10 k")
      (footprint "eagle-import:R0603")
      (libsource (lib "eagle-import") (part "RESISTOR_0603"))
    )
    (comp (ref "R44")
      (value "500 R")
      (footprint "eagle-import:R0603")
      (libsource (lib "eagle-import") (part "RESISTOR_0603"))
    )
    (comp (ref "R45")
      (value "10 k")
      (footprint "eagle-import:R0603")
      (libsource (lib "eagle-import") (part "RESISTOR_0603"))
    )
    (comp (ref "R46")
      (value "10 k")
      (footprint "eagle-import:R0603")
      (libsource (lib "eagle-import") (part "RESISTOR_0603"))
    )
    (comp (ref "R58")
      (value "10 k")
      (footprint "eagle-import:R0603")
      (libsource (lib "eagle-import") (part "RESISTOR_0603"))
    )
    (comp (ref "+3V3_OK")
      (value "LED_GREEN_SMD")
      (footprint "eagle-import:WL-SMCW_0603")
      (fields (field (name "MOUSER_PART_NUMBER") "..."))
      (libsource (lib "eagle-import") (part "LED_SMD_GREEN"))
    )
    (comp (ref "+5V_OK")
      (value "LED_GREEN_SMD")
      (footprint "eagle-import:WL-SMCW_0603")
      (fields (field (name "MOUSER_PART_NUMBER") "..."))
      (libsource (lib "eagle-import") (part "LED_SMD_GREEN"))
    )
    (comp (ref "+15V_OK")
      (value "LED_GREEN_SMD")
      (footprint "eagle-import:WL-SMCW_0603")
      (fields (field (name "MOUSER_PART_NUMBER") "..."))
      (libsource (lib "eagle-import") (part "LED_SMD_GREEN"))
    )
    (comp (ref "-15V_OK")
      (value "LED_GREEN_SMD")
      (footprint "eagle-import:WL-SMCW_0603")
      (fields (field (name "MOUSER_PART_NUMBER") "..."))
      (libsource (lib "eagle-import") (part "LED_SMD_GREEN"))
    )
    (comp (ref "ANALOG_VOLT_IN")
      (value "90814-0204")
      (footprint "eagle-import:MOLEX_90814-0204")
      (fields (field (name "MOUSER_PART_NUMBER") "538-90814-0204"))
      (libsource (lib "eagle-import") (part "90814-0204"))
    )
    (comp (ref "C103")
      (value "330 nF")
      (footprint "eagle-import:C0603")
      (libsource (lib "eagle-import") (part "CAPACITOR_0603"))
    )
    (comp (ref "C105")
      (value "100 nF")
      (footprint "eagle-import:C0603")
      (libsource (lib "eagle-import") (part "CAPACITOR_0603"))
    )
    (comp (ref "DIGITAL_VOLT")
      (value "90814-0204")
      (footprint "eagle-import:MOLEX_90814-0204")
      (fields (field (name "MOUSER_PART_NUMBER") "538-90814-0204"))
      (libsource (lib "eagle-import") (part "90814-0204"))
    )
    (comp (ref "GND")
      (value "TPTHT")
      (footprint "eagle-import:THT_PIN")
      (libsource (lib "eagle-import") (part "TPTHT"))
    )
    (comp (ref "R1")
      (value "0 R")
      (footprint "eagle-import:R0603")
      (libsource (lib "eagle-import") (part "RESISTOR_0603"))
    )
    (comp (ref "R2")
      (value "0 R")
      (footprint "eagle-import:R0603")
      (libsource (lib "eagle-import") (part "RESISTOR_0603"))
    )
    (comp (ref "R15")
      (value "0 R")
      (footprint "eagle-import:R0603")
      (libsource (lib "eagle-import") (part "RESISTOR_0603"))
    )
    (comp (ref "R16")
      (value "0 R")
      (footprint "eagle-import:R0603")
      (libsource (lib "eagle-import") (part "RESISTOR_0603"))
    )
    (comp (ref "R69")
      (value "0 R")
      (footprint "eagle-import:R0603")
      (libsource (lib "eagle-import") (part "RESISTOR_0603"))
    )
    (comp (ref "R97")
      (value "680 R")
      (footprint "eagle-import:R0603")
      (libsource (lib "eagle-import") (part "RESISTOR_0603"))
    )
    (comp (ref "R98")
      (value "680 R")
      (footprint "eagle-import:R0603")
      (libsource (lib "eagle-import") (part "RESISTOR_0603"))
    )
    (comp (ref "R99")
      (value "65 R")
      (footprint "eagle-import:R0603")
      (libsource (lib "eagle-import") (part "RESISTOR_0603"))
    )
    (comp (ref "R100")
      (value "150 R")
      (footprint "eagle-import:R0603")
      (libsource (lib "eagle-import") (part "RESISTOR_0603"))
    )
    (comp (ref "R104")
      (value "0 R")
      (footprint "eagle-import:R0603")
      (libsource (lib "eagle-import") (part "RESISTOR_0603"))
    )
    (comp (ref "STARGROUND")
      (value "TPTHT")
      (footprint "eagle-import:THT_PIN")
      (libsource (lib "eagle-import") (part "TPTHT"))
    )
    (comp (ref "TP01")
      (value "TPTHT")
      (footprint "eagle-import:THT_PIN")
      (libsource (lib "eagle-import") (part "TPTHT"))
    )
    (comp (ref "TP02")
      (value "TPTHT")
      (footprint "eagle-import:THT_PIN")
      (libsource (lib "eagle-import") (part "TPTHT"))
    )
    (comp (ref "TP08")
      (value "TPTHT")
      (footprint "eagle-import:THT_PIN")
      (libsource (lib "eagle-import") (part "TPTHT"))
    )
    (comp (ref "TP09")
      (value "TPTHT")
      (footprint "eagle-import:THT_PIN")
      (libsource (lib "eagle-import") (part "TPTHT"))
    )
    (comp (ref "U1")
      (value "78_SMD")
      (footprint "eagle-import:TO252")
      (libsource (lib "eagle-import") (part "78_SMD"))
    )
    (comp (ref "X2")
      (value "CONNECTOR_3POL")
      (footprint "eagle-import:W237-103")
      (libsource (lib "eagle-import") (part "CONNECTOR_3POL"))
    )
    (comp (ref "C36")
      (value "2.2 uF")
      (footprint "eagle-import:C1206")
      (libsource (lib "eagle-import") (part "CAPACITOR_1206"))
    )
    (comp (ref "C39")
      (value "10 uF")
      (footprint "eagle-import:C1206")
      (libsource (lib "eagle-import") (part "CAPACITOR_1206"))
    )
    (comp (ref "C44")
      (value "100 nF")
      (footprint "eagle-import:C0603")
      (libsource (lib "eagle-import") (part "CAPACITOR_0603"))
    )
    (comp (ref "C59")
      (value "100 nF")
      (footprint "eagle-import:C0603")
      (libsource (lib "eagle-import") (part "CAPACITOR_0603"))
    )
    (comp (ref "C65")
      (value "2.7 pF")
      (footprint "eagle-import:C0603")
      (libsource (lib "eagle-import") (part "CAPACITOR_0603"))
    )
    (comp (ref "C66")
      (value "2.7 pF")
      (footprint "eagle-import:C0603")
      (libsource (lib "eagle-import") (part "CAPACITOR_0603"))
    )
    (comp (ref "C69")
      (value "4.3 pF")
      (footprint "eagle-import:C0603")
      (libsource (lib "eagle-import") (part "CAPACITOR_0603"))
    )
    (comp (ref "C70")
      (value "4.3 pF")
      (footprint "eagle-import:C0603")
      (libsource (lib "eagle-import") (part "CAPACITOR_0603"))
    )
    (comp (ref "C71")
      (value "2.2 uF")
      (footprint "eagle-import:C1206")
      (libsource (lib "eagle-import") (part "CAPACITOR_1206"))
    )
    (comp (ref "C72")
      (value "2.2 uF")
      (footprint "eagle-import:C1206")
      (libsource (lib "eagle-import") (part "CAPACITOR_1206"))
    )
    (comp (ref "C73")
      (value "100 nF")
      (footprint "eagle-import:C0603")
      (libsource (lib "eagle-import") (part "CAPACITOR_0603"))
    )
    (comp (ref "C74")
      (value "100 nF")
      (footprint "eagle-import:C0603")
      (libsource (lib "eagle-import") (part "CAPACITOR_0603"))
    )
    (comp (ref "C75")
      (value "100 nF")
      (footprint "eagle-import:C0603")
      (libsource (lib "eagle-import") (part "CAPACITOR_0603"))
    )
    (comp (ref "C76")
      (value "100 nF")
      (footprint "eagle-import:C0603")
      (libsource (lib "eagle-import") (part "CAPACITOR_0603"))
    )
    (comp (ref "C77")
      (value "100 nF")
      (footprint "eagle-import:C0603")
      (libsource (lib "eagle-import") (part "CAPACITOR_0603"))
    )
    (comp (ref "C78")
      (value "100 nF")
      (footprint "eagle-import:C0603")
      (libsource (lib "eagle-import") (part "CAPACITOR_0603"))
    )
    (comp (ref "C79")
      (value "100 nF")
      (footprint "eagle-import:C0603")
      (libsource (lib "eagle-import") (part "CAPACITOR_0603"))
    )
    (comp (ref "C80")
      (value "100 nF")
      (footprint "eagle-import:C0603")
      (libsource (lib "eagle-import") (part "CAPACITOR_0603"))
    )
    (comp (ref "C81")
      (value "100 nF")
      (footprint "eagle-import:C0603")
      (libsource (lib "eagle-import") (part "CAPACITOR_0603"))
    )
    (comp (ref "C82")
      (value "100 nF")
      (footprint "eagle-import:C0603")
      (libsource (lib "eagle-import") (part "CAPACITOR_0603"))
    )
    (comp (ref "C83")
      (value "100 nF")
      (footprint "eagle-import:C0603")
      (libsource (lib "eagle-import") (part "CAPACITOR_0603"))
    )
    (comp (ref "C84")
      (value "100 nF")
      (footprint "eagle-import:C0603")
      (libsource (lib "eagle-import") (part "CAPACITOR_0603"))
    )
    (comp (ref "C85")
      (value "100 nF")
      (footprint "eagle-import:C0603")
      (libsource (lib "eagle-import") (part "CAPACITOR_0603"))
    )
    (comp (ref "C99")
      (value "10 uF")
      (footprint "eagle-import:C1206")
      (libsource (lib "eagle-import") (part "CAPACITOR_1206"))
    )
    (comp (ref "C119")
      (value "4.7 uF")
      (footprint "eagle-import:C1206")
      (libsource (lib "eagle-import") (part "CAPACITOR_1206"))
    )
    (comp (ref "DEBUG1")
      (value "TPTHT")
      (footprint "eagle-import:THT_PIN")
      (libsource (lib "eagle-import") (part "TPTHT"))
    )
    (comp (ref "DEBUG2")
      (value "TPTHT")
      (footprint "eagle-import:THT_PIN")
      (libsource (lib "eagle-import") (part "TPTHT"))
    )
    (comp (ref "DISPLAY1")
      (value "90814-0204")
      (footprint "eagle-import:MOLEX_90814-0204")
      (fields (field (name "MOUSER_PART_NUMBER") "538-90814-0204"))
      (libsource (lib "eagle-import") (part "90814-0204"))
    )
    (comp (ref "FB6")
      (value "FERITTE-BREAD")
      (footprint "eagle-import:BLM18KG102SH1J")
      (fields
        (field (name "MANUFACTURER_PART_NUMBER") "BLM18KG102SH1D")
        (field (name "MOUSER_PART_NUMBER") "81-BLM18KG102SH1D")
      )
      (libsource (lib "eagle-import") (part "FERITTE-BREAD"))
    )
    (comp (ref "FB7")
      (value "FERITTE-BREAD")
      (footprint "eagle-import:BLM18KG102SH1J")
      (fields
        (field (name "MANUFACTURER_PART_NUMBER") "BLM18KG102SH1D")
        (field (name "MOUSER_PART_NUMBER") "81-BLM18KG102SH1D")
      )
      (libsource (lib "eagle-import") (part "FERITTE-BREAD"))
    )
    (comp (ref "IC10")
      (value "STM32F767ZIT6")
      (footprint "eagle-import:QFP50P2200X2200X160-144N")
      (fields (field (name "MOUSER_PART_NUMBER") "511-STM32F767ZIT6"))
      (libsource (lib "eagle-import") (part "STM32F767ZIT6"))
    )
    (comp (ref "IC12")
      (value "ESDA6V1BC6")
      (footprint "eagle-import:SOT95P280X145-6N")
      (fields (field (name "MOUSER_PART_NUMBER") "511-ESDA6V1BC6"))
      (libsource (lib "eagle-import") (part "ESDA6V1BC6"))
    )
    (comp (ref "LD1")
      (value "LED_YELOW_SMD")
      (footprint "eagle-import:WL-SMCW_0603")
      (fields (field (name "MOUSER_PART_NUMBER") "..."))
      (libsource (lib "eagle-import") (part "LED_SMD_YELOW"))
    )
    (comp (ref "LD2")
      (value "LED_RED_SMD")
      (footprint "eagle-import:WL-SMCW_0603")
      (fields (field (name "MOUSER_PART_NUMBER") "..."))
      (libsource (lib "eagle-import") (part "LED_SMD_RED"))
    )
    (comp (ref "LD3")
      (value "LED_GREEN_SMD")
      (footprint "eagle-import:WL-SMCW_0603")
      (fields (field (name "MOUSER_PART_NUMBER") "..."))
      (libsource (lib "eagle-import") (part "LED_SMD_GREEN"))
    )
    (comp (ref "PROG.")
      (value "90814-0204")
      (footprint "eagle-import:MOLEX_90814-0204")
      (fields (field (name "MOUSER_PART_NUMBER") "538-90814-0204"))
      (libsource (lib "eagle-import") (part "90814-0204"))
    )
    (comp (ref "R5")
      (value "680 R")
      (footprint "eagle-import:R0603")
      (libsource (lib "eagle-import") (part "RESISTOR_0603"))
    )
    (comp (ref "R6")
      (value "680 R")
      (footprint "eagle-import:R0603")
      (libsource (lib "eagle-import") (part "RESISTOR_0603"))
    )
    (comp (ref "R13")
      (value "680 R")
      (footprint "eagle-import:R0603")
      (libsource (lib "eagle-import") (part "RESISTOR_0603"))
    )
    (comp (ref "R19")
      (value "10 k")
      (footprint "eagle-import:R0603")
      (libsource (lib "eagle-import") (part "RESISTOR_0603"))
    )
    (comp (ref "R31")
      (value "0 R")
      (footprint "eagle-import:R0603")
      (libsource (lib "eagle-import") (part "RESISTOR_0603"))
    )
    (comp (ref "R36")
      (value "0 R")
      (footprint "eagle-import:R0603")
      (libsource (lib "eagle-import") (part "RESISTOR_0603"))
    )
    (comp (ref "R37")
      (value "0 R")
      (footprint "eagle-import:R0603")
      (libsource (lib "eagle-import") (part "RESISTOR_0603"))
    )
    (comp (ref "R78")
      (value "10 k")
      (footprint "eagle-import:R0603")
      (libsource (lib "eagle-import") (part "RESISTOR_0603"))
    )
    (comp (ref "S1")
      (value "PTS647SN50SMTR2LFS")
      (footprint "eagle-import:PTS647SN50SMTR2LFS")
      (fields (field (name "MOUSER_PART_NUMBER") "611-PTS647SN50SMTR2L"))
      (libsource (lib "eagle-import") (part "PTS647SN50SMTR2LFS"))
    )
    (comp (ref "TP05")
      (value "TPTHT")
      (footprint "eagle-import:THT_PIN")
      (libsource (lib "eagle-import") (part "TPTHT"))
    )
    (comp (ref "TP06")
      (value "TPTHT")
      (footprint "eagle-import:THT_PIN")
      (libsource (lib "eagle-import") (part "TPTHT"))
    )
    (comp (ref "TP07")
      (value "TPTHT")
      (footprint "eagle-import:THT_PIN")
      (libsource (lib "eagle-import") (part "TPTHT"))
    )
    (comp (ref "X1")
      (value "USB_B_CONNECTOR")
      (footprint "eagle-import:SMARTPRJ_PN61729")
      (fields (field (name "MOUSER_PART_NUMBER") "649-61729-0010BLF"))
      (libsource (lib "eagle-import") (part "USB_B_CONNECTOR"))
    )
    (comp (ref "Y1")
      (value "NX3215SA-32.768K-STD-MUA-8")
      (footprint "eagle-import:NX3215SA")
      (fields (field (name "MOUSER_PART_NUMBER") "344-NX3215SA32768K8"))
      (libsource (lib "eagle-import") (part "NX3215SA-32.768K-STD-MUA-8"))
    )
    (comp (ref "Y2")
      (value "NX3225GD-8MHZ-STD-CRA-3")
      (footprint "eagle-import:RESC3226X100N")
      (fields (field (name "MOUSER_PART_NUMBER") "344-NX3225GD8MCRA3"))
      (libsource (lib "eagle-import") (part "NX3225GD-8MHZ-STD-CRA-3"))
    )
    (comp (ref "C6")
      (value "100 nF")
      (footprint "eagle-import:C0603")
      (libsource (lib "eagle-import") (part "CAPACITOR_0603"))
    )
    (comp (ref "C7")
      (value "100 nF")
      (footprint "eagle-import:C0603")
      (libsource (lib "eagle-import") (part "CAPACITOR_0603"))
    )
    (comp (ref "C26")
      (value "100 nF")
      (footprint "eagle-import:C0603")
      (libsource (lib "eagle-import") (part "CAPACITOR_0603"))
    )
    (comp (ref "C27")
      (value "100 nF")
      (footprint "eagle-import:C0603")
      (libsource (lib "eagle-import") (part "CAPACITOR_0603"))
    )
    (comp (ref "C28")
      (value "100 nF")
      (footprint "eagle-import:C0603")
      (libsource (lib "eagle-import") (part "CAPACITOR_0603"))
    )
    (comp (ref "C29")
      (value "100 nF")
      (footprint "eagle-import:C0603")
      (libsource (lib "eagle-import") (part "CAPACITOR_0603"))
    )
    (comp (ref "IC1")
      (value "OP275")
      (footprint "eagle-import:SOIC8")
      (libsource (lib "eagle-import") (part "OP275"))
    )
    (comp (ref "U7")
      (value "THAT1240")
      (footprint "eagle-import:SO08")
      (fields (field (name "MOUSER_PART_NUMBER") "887-1240S08-U"))
      (libsource (lib "eagle-import") (part "THAT1240SO8-USO8-U"))
    )
    (comp (ref "U8")
      (value "THAT1240")
      (footprint "eagle-import:SO08")
      (fields (field (name "MOUSER_PART_NUMBER") "887-1240S08-U"))
      (libsource (lib "eagle-import") (part "THAT1240SO8-USO8-U"))
    )
    (comp (ref "C40")
      (value "30 pF")
      (footprint "eagle-import:C0603")
      (libsource (lib "eagle-import") (part "CAPACITOR_0603"))
    )
    (comp (ref "C86")
      (value "100 nF")
      (footprint "eagle-import:C0603")
      (libsource (lib "eagle-import") (part "CAPACITOR_0603"))
    )
    (comp (ref "C87")
      (value "100 nF")
      (footprint "eagle-import:C0603")
      (libsource (lib "eagle-import") (part "CAPACITOR_0603"))
    )
    (comp (ref "C88")
      (value "1 uF")
      (footprint "eagle-import:C0603")
      (libsource (lib "eagle-import") (part "CAPACITOR_0603"))
    )
    (comp (ref "C89")
      (value "470 pF")
      (footprint "eagle-import:C0603")
      (libsource (lib "eagle-import") (part "CAPACITOR_0603"))
    )
    (comp (ref "C90")
      (value "100 nF")
      (footprint "eagle-import:C0603")
      (libsource (lib "eagle-import") (part "CAPACITOR_0603"))
    )
    (comp (ref "C91")
      (value "10 uF")
      (footprint "eagle-import:C1206")
      (libsource (lib "eagle-import") (part "CAPACITOR_1206"))
    )
    (comp (ref "C92")
      (value "100 nF")
      (footprint "eagle-import:C0603")
      (libsource (lib "eagle-import") (part "CAPACITOR_0603"))
    )
    (comp (ref "C93")
      (value "100 nF")
      (footprint "eagle-import:C0603")
      (libsource (lib "eagle-import") (part "CAPACITOR_0603"))
    )
    (comp (ref "C94")
      (value "100 nF")
      (footprint "eagle-import:C0603")
      (libsource (lib "eagle-import") (part "CAPACITOR_0603"))
    )
    (comp (ref "C100")
      (value "30 pF")
      (footprint "eagle-import:C0603")
      (libsource (lib "eagle-import") (part "CAPACITOR_0603"))
    )
    (comp (ref "C101")
      (value "4.7 uF")
      (footprint "eagle-import:C1206")
      (libsource (lib "eagle-import") (part "CAPACITOR_1206"))
    )
    (comp (ref "FB5")
      (value "0 R")
      (footprint "eagle-import:BLM18KG102SH1J")
      (fields
        (field (name "MANUFACTURER_PART_NUMBER") "BLM18KG102SH1D")
        (field (name "MOUSER_PART_NUMBER") "81-BLM18KG102SH1D")
      )
      (libsource (lib "eagle-import") (part "FERITTE-BREAD"))
    )
    (comp (ref "IC6")
      (value "LAN8742A-CZ-TR")
      (footprint "eagle-import:QFN50P400X400X100-25N")
      (fields (field (name "MOUSER_PART_NUMBER") "579-LAN8742A-CZ-TR"))
      (libsource (lib "eagle-import") (part "LAN8742A-CZ-TR"))
    )
    (comp (ref "IC13")
      (value "USBLC6-4SC6")
      (footprint "eagle-import:SOT95P280X145-6N")
      (fields (field (name "MOUSER_PART_NUMBER") "511-USBLC6-4SC6"))
      (libsource (lib "eagle-import") (part "USBLC6-4SC6"))
    )
    (comp (ref "J1")
      (value "GWLEX-SMT-S988G_Y")
      (footprint "eagle-import:GWLEXSMTS988GY")
      (fields
        (field (name "MANUFACTURER_PART_NUMBER") "GWLEX-SMT-S988G/Y")
        (field (name "MOUSER_PART_NUMBER") "806-GWLEX-SMT-S988GY")
      )
      (libsource (lib "eagle-import") (part "GWLEX-SMT-S988G_Y"))
    )
    (comp (ref "R18")
      (value "10 k")
      (footprint "eagle-import:R0603")
      (libsource (lib "eagle-import") (part "RESISTOR_0603"))
    )
    (comp (ref "R20")
      (value "10 k")
      (footprint "eagle-import:R0603")
      (libsource (lib "eagle-import") (part "RESISTOR_0603"))
    )
    (comp (ref "R21")
      (value "10 k")
      (footprint "eagle-import:R0603")
      (libsource (lib "eagle-import") (part "RESISTOR_0603"))
    )
    (comp (ref "R22")
      (value "1k5")
      (footprint "eagle-import:R0603")
      (libsource (lib "eagle-import") (part "RESISTOR_0603"))
    )
    (comp (ref "R23")
      (value "10 k")
      (footprint "eagle-import:R0603")
      (libsource (lib "eagle-import") (part "RESISTOR_0603"))
    )
    (comp (ref "R24")
      (value "33 R")
      (footprint "eagle-import:R0603")
      (libsource (lib "eagle-import") (part "RESISTOR_0603"))
    )
    (comp (ref "R25")
      (value "33 R")
      (footprint "eagle-import:R0603")
      (libsource (lib "eagle-import") (part "RESISTOR_0603"))
    )
    (comp (ref "R26")
      (value "33 R")
      (footprint "eagle-import:R0603")
      (libsource (lib "eagle-import") (part "RESISTOR_0603"))
    )
    (comp (ref "R27")
      (value "10 k")
      (footprint "eagle-import:R0603")
      (libsource (lib "eagle-import") (part "RESISTOR_0603"))
    )
    (comp (ref "R29")
      (value "75 R")
      (footprint "eagle-import:R0603")
      (libsource (lib "eagle-import") (part "RESISTOR_0603"))
    )
    (comp (ref "R77")
      (value "12k1")
      (footprint "eagle-import:R0603")
      (libsource (lib "eagle-import") (part "RESISTOR_0603"))
    )
    (comp (ref "R79")
      (value "50 R")
      (footprint "eagle-import:R0603")
      (libsource (lib "eagle-import") (part "RESISTOR_0603"))
    )
    (comp (ref "R80")
      (value "50 R")
      (footprint "eagle-import:R0603")
      (libsource (lib "eagle-import") (part "RESISTOR_0603"))
    )
    (comp (ref "R81")
      (value "50 R")
      (footprint "eagle-import:R0603")
      (libsource (lib "eagle-import") (part "RESISTOR_0603"))
    )
    (comp (ref "R82")
      (value "50 R")
      (footprint "eagle-import:R0603")
      (libsource (lib "eagle-import") (part "RESISTOR_0603"))
    )
    (comp (ref "R83")
      (value "270 R")
      (footprint "eagle-import:R0603")
      (libsource (lib "eagle-import") (part "RESISTOR_0603"))
    )
    (comp (ref "R84")
      (value "270 R")
      (footprint "eagle-import:R0603")
      (libsource (lib "eagle-import") (part "RESISTOR_0603"))
    )
    (comp (ref "R85")
      (value "10 k")
      (footprint "eagle-import:R0603")
      (libsource (lib "eagle-import") (part "RESISTOR_0603"))
    )
    (comp (ref "R88")
      (value "75 R")
      (footprint "eagle-import:R0603")
      (libsource (lib "eagle-import") (part "RESISTOR_0603"))
    )
    (comp (ref "R89")
      (value "75 R")
      (footprint "eagle-import:R0603")
      (libsource (lib "eagle-import") (part "RESISTOR_0603"))
    )
    (comp (ref "R90")
      (value "75 R")
      (footprint "eagle-import:R0603")
      (libsource (lib "eagle-import") (part "RESISTOR_0603"))
    )
    (comp (ref "R91")
      (value "0 R")
      (footprint "eagle-import:R0603")
      (libsource (lib "eagle-import") (part "RESISTOR_0603"))
    )
    (comp (ref "T1")
      (value "H1102NL")
      (footprint "eagle-import:SOIC127P940X597-16N")
      (fields (field (name "MOUSER_PART_NUMBER") "673-H1102NL"))
      (libsource (lib "eagle-import") (part "H1102NL"))
    )
    (comp (ref "Y3")
      (value "ABLS2-25.000MHZ-D4YF-T")
      (footprint "eagle-import:ABLS")
      (fields (field (name "MOUSER_PART_NUMBER") "815-ABLS2-25-D4YF-T"))
      (libsource (lib "eagle-import") (part "ABLS2-25.000MHZ-D4YF-T"))
    )
  )
  (nets
    (net (code "1") (name "+3V3") (class "Default")
      (node (ref "C119") (pin "2") (pinfunction "2_2") (pintype "passive"))
      (node (ref "C59") (pin "2") (pinfunction "2_2") (pintype "passive"))
      (node (ref "C73") (pin "1") (pinfunction "1_1") (pintype "passive"))
      (node (ref "C74") (pin "1") (pinfunction "1_1") (pintype "passive"))
      (node (ref "C75") (pin "1") (pinfunction "1_1") (pintype "passive"))
      (node (ref "C76") (pin "1") (pinfunction "1_1") (pintype "passive"))
      (node (ref "C77") (pin "1") (pinfunction "1_1") (pintype "passive"))
      (node (ref "C78") (pin "1") (pinfunction "1_1") (pintype "passive"))
      (node (ref "C79") (pin "1") (pinfunction "1_1") (pintype "passive"))
      (node (ref "C81") (pin "2") (pinfunction "2_2") (pintype "passive"))
      (node (ref "C82") (pin "2") (pinfunction "2_2") (pintype "passive"))
      (node (ref "C83") (pin "1") (pinfunction "1_1") (pintype "passive"))
      (node (ref "C84") (pin "1") (pinfunction "1_1") (pintype "passive"))
      (node (ref "C85") (pin "1") (pinfunction "1_1") (pintype "passive"))
      (node (ref "C86") (pin "2") (pinfunction "2_2") (pintype "passive"))
      (node (ref "C87") (pin "2") (pinfunction "2_2") (pintype "passive"))
      (node (ref "C90") (pin "2") (pinfunction "2_2") (pintype "passive"))
      (node (ref "C91") (pin "1") (pinfunction "1_1") (pintype "passive"))
      (node (ref "C92") (pin "2") (pinfunction "2_2") (pintype "passive"))
      (node (ref "C93") (pin "2") (pinfunction "2_2") (pintype "passive"))
      (node (ref "DIGITAL_VOLT") (pin "1") (pinfunction "1_1") (pintype "bidirectional"))
      (node (ref "FB5") (pin "1") (pinfunction "1_1") (pintype "bidirectional"))
      (node (ref "FB6") (pin "1") (pinfunction "1_1") (pintype "bidirectional"))
      (node (ref "IC10") (pin "108") (pinfunction "VDD_8_108") (pintype "bidirectional"))
      (node (ref "IC10") (pin "121") (pinfunction "VDDSDMMC_121") (pintype "bidirectional"))
      (node (ref "IC10") (pin "131") (pinfunction "VDD_9_131") (pintype "bidirectional"))
      (node (ref "IC10") (pin "143") (pinfunction "PDR_ON_143") (pintype "bidirectional"))
      (node (ref "IC10") (pin "144") (pinfunction "VDD_10_144") (pintype "bidirectional"))
      (node (ref "IC10") (pin "17") (pinfunction "VDD_1_17") (pintype "bidirectional"))
      (node (ref "IC10") (pin "30") (pinfunction "VDD_2_30") (pintype "bidirectional"))
      (node (ref "IC10") (pin "39") (pinfunction "VDD_3_39") (pintype "bidirectional"))
      (node (ref "IC10") (pin "52") (pinfunction "VDD_4_52") (pintype "bidirectional"))
      (node (ref "IC10") (pin "6") (pinfunction "VBAT_6") (pintype "bidirectional"))
      (node (ref "IC10") (pin "62") (pinfunction "VDD_5_62") (pintype "bidirectional"))
      (node (ref "IC10") (pin "72") (pinfunction "VDD_6_72") (pintype "bidirectional"))
      (node (ref "IC10") (pin "84") (pinfunction "VDD_7_84") (pintype "bidirectional"))
      (node (ref "IC10") (pin "95") (pinfunction "VDDUSB_95") (pintype "bidirectional"))
      (node (ref "IC6") (pin "1") (pinfunction "VDD2A_1") (pintype "power_in"))
      (node (ref "IC6") (pin "19") (pinfunction "VDD1A_19") (pintype "power_in"))
      (node (ref "IC6") (pin "9") (pinfunction "VDDIO_9") (pintype "power_in"))
      (node (ref "R18") (pin "1") (pinfunction "1_1") (pintype "passive"))
      (node (ref "R20") (pin "1") (pinfunction "1_1") (pintype "passive"))
      (node (ref "R21") (pin "1") (pinfunction "1_1") (pintype "passive"))
      (node (ref "R22") (pin "1") (pinfunction "1_1") (pintype "passive"))
      (node (ref "R23") (pin "2") (pinfunction "2_2") (pintype "passive"))
      (node (ref "R99") (pin "2") (pinfunction "2_2") (pintype "passive"))
      (node (ref "T1") (pin "2") (pinfunction "CT_1_2") (pintype "bidirectional"))
      (node (ref "T1") (pin "7") (pinfunction "CT_2_7") (pintype "bidirectional"))
    )
    (net (code "2") (name "+3V3_SIG") (class "Default")
      (node (ref "IC10") (pin "47") (pinfunction "PB1_47") (pintype "bidirectional"))
    )
    (net (code "3") (name "+5V") (class "Default")
      (node (ref "C114") (pin "1") (pinfunction "1_1") (pintype "passive"))
      (node (ref "C32") (pin "1") (pinfunction "1_1") (pintype "passive"))
      (node (ref "C35") (pin "1") (pinfunction "1_1") (pintype "passive"))
      (node (ref "C46") (pin "1") (pinfunction "1_1") (pintype "passive"))
      (node (ref "C47") (pin "1") (pinfunction "1_1") (pintype "passive"))
      (node (ref "C99") (pin "1") (pinfunction "1_1") (pintype "passive"))
      (node (ref "DIGITAL_VOLT") (pin "4") (pinfunction "4_4") (pintype "bidirectional"))
      (node (ref "FB7") (pin "2") (pinfunction "2_2") (pintype "bidirectional"))
      (node (ref "IC11") (pin "4") (pinfunction "VD+_4") (pintype "bidirectional"))
      (node (ref "IC17") (pin "23") (pinfunction "VDRIVE_23") (pintype "bidirectional"))
      (node (ref "IC3") (pin "4") (pinfunction "VD+_4") (pintype "bidirectional"))
      (node (ref "R100") (pin "2") (pinfunction "2_2") (pintype "passive"))
      (node (ref "R35") (pin "2") (pinfunction "2_2") (pintype "passive"))
      (node (ref "R96") (pin "1") (pinfunction "1_1") (pintype "passive"))
    )
    (net (code "4") (name "+5V(ANALOG)") (class "Default")
      (node (ref "C105") (pin "1") (pinfunction "1_1") (pintype "passive"))
      (node (ref "C14") (pin "1") (pinfunction "1_1") (pintype "passive"))
      (node (ref "C24") (pin "1") (pinfunction "1_1") (pintype "passive"))
      (node (ref "C33") (pin "1") (pinfunction "1_1") (pintype "passive"))
      (node (ref "C34") (pin "1") (pinfunction "1_1") (pintype "passive"))
      (node (ref "C41") (pin "1") (pinfunction "1_1") (pintype "passive"))
      (node (ref "C42") (pin "1") (pinfunction "1_1") (pintype "passive"))
      (node (ref "C51") (pin "1") (pinfunction "1_1") (pintype "passive"))
      (node (ref "C52") (pin "1") (pinfunction "1_1") (pintype "passive"))
      (node (ref "IC17") (pin "1") (pinfunction "AVCC_1_1") (pintype "bidirectional"))
      (node (ref "IC17") (pin "37") (pinfunction "AVCC_2_37") (pintype "bidirectional"))
      (node (ref "IC17") (pin "38") (pinfunction "AVCC_3_38") (pintype "bidirectional"))
      (node (ref "IC17") (pin "48") (pinfunction "AVCC_4_48") (pintype "bidirectional"))
      (node (ref "IC2") (pin "1") (pinfunction "VA_1") (pintype "bidirectional"))
      (node (ref "IC2") (pin "7") (pinfunction "VREFIN_7") (pintype "bidirectional"))
      (node (ref "U1") (pin "3") (pinfunction "VO_3") (pintype "passive"))
    )
    (net (code "5") (name "+5V_SIG") (class "Default")
      (node (ref "IC10") (pin "26") (pinfunction "PC0_26") (pintype "bidirectional"))
    )
    (net (code "6") (name "+12V_SIG") (class "Default")
      (node (ref "IC10") (pin "42") (pinfunction "PA6_42") (pintype "bidirectional"))
    )
    (net (code "7") (name "+15V_SIG") (class "Default")
      (node (ref "IC10") (pin "34") (pinfunction "PA0_34") (pintype "bidirectional"))
    )
    (net (code "8") (name "-15V_SIG") (class "Default")
      (node (ref "IC10") (pin "37") (pinfunction "PA3_37") (pintype "bidirectional"))
    )
    (net (code "9") (name "8MHZ_CRYSTAL_A") (class "Default")
      (node (ref "C70") (pin "1") (pinfunction "1_1") (pintype "passive"))
      (node (ref "IC10") (pin "23") (pinfunction "PH0_23") (pintype "bidirectional"))
      (node (ref "Y2") (pin "1") (pinfunction "1_1") (pintype "bidirectional"))
    )
    (net (code "10") (name "8MHZ_CRYSTAL_B") (class "Default")
      (node (ref "C69") (pin "1") (pinfunction "1_1") (pintype "passive"))
      (node (ref "IC10") (pin "24") (pinfunction "PH1_24") (pintype "bidirectional"))
      (node (ref "Y2") (pin "2") (pinfunction "2_2") (pintype "bidirectional"))
    )
    (net (code "11") (name "32.768KHZ_A") (class "Default")
      (node (ref "C66") (pin "1") (pinfunction "1_1") (pintype "passive"))
      (node (ref "IC10") (pin "8") (pinfunction "PC14_8") (pintype "bidirectional"))
      (node (ref "Y1") (pin "1") (pinfunction "1_1") (pintype "bidirectional"))
    )
    (net (code "12") (name "32.768KHZ_B") (class "Default")
      (node (ref "C65") (pin "1") (pinfunction "1_1") (pintype "passive"))
      (node (ref "IC10") (pin "9") (pinfunction "PC15_9") (pintype "bidirectional"))
      (node (ref "Y1") (pin "2") (pinfunction "2_2") (pintype "bidirectional"))
    )
    (net (code "13") (name "AGND") (class "Default")
      (node (ref "+15V_OK") (pin "1") (pinfunction "-_1") (pintype "passive"))
      (node (ref "+3V3_OK") (pin "1") (pinfunction "-_1") (pintype "passive"))
      (node (ref "+5V_OK") (pin "1") (pinfunction "-_1") (pintype "passive"))
      (node (ref "-15V_OK") (pin "2") (pinfunction "+_2") (pintype "passive"))
      (node (ref "C1") (pin "2") (pinfunction "2_2") (pintype "passive"))
      (node (ref "C100") (pin "1") (pinfunction "1_1") (pintype "passive"))
      (node (ref "C103") (pin "2") (pinfunction "2_2") (pintype "passive"))
      (node (ref "C104") (pin "2") (pinfunction "2_2") (pintype "passive"))
      (node (ref "C105") (pin "2") (pinfunction "2_2") (pintype "passive"))
      (node (ref "C11") (pin "2") (pinfunction "2_2") (pintype "passive"))
      (node (ref "C114") (pin "2") (pinfunction "2_2") (pintype "passive"))
      (node (ref "C115") (pin "2") (pinfunction "2_2") (pintype "passive"))
      (node (ref "C116") (pin "2") (pinfunction "2_2") (pintype "passive"))
      (node (ref "C117") (pin "2") (pinfunction "2_2") (pintype "passive"))
      (node (ref "C118") (pin "2") (pinfunction "2_2") (pintype "passive"))
      (node (ref "C119") (pin "1") (pinfunction "1_1") (pintype "passive"))
      (node (ref "C12") (pin "2") (pinfunction "2_2") (pintype "passive"))
      (node (ref "C13") (pin "2") (pinfunction "2_2") (pintype "passive"))
      (node (ref "C14") (pin "2") (pinfunction "2_2") (pintype "passive"))
      (node (ref "C19") (pin "2") (pinfunction "2_2") (pintype "passive"))
      (node (ref "C2") (pin "2") (pinfunction "2_2") (pintype "passive"))
      (node (ref "C20") (pin "2") (pinfunction "2_2") (pintype "passive"))
      (node (ref "C21") (pin "2") (pinfunction "2_2") (pintype "passive"))
      (node (ref "C22") (pin "2") (pinfunction "2_2") (pintype "passive"))
      (node (ref "C23") (pin "2") (pinfunction "2_2") (pintype "passive"))
      (node (ref "C24") (pin "2") (pinfunction "2_2") (pintype "passive"))
      (node (ref "C25") (pin "2") (pinfunction "2_2") (pintype "passive"))
      (node (ref "C26") (pin "2") (pinfunction "2_2") (pintype "passive"))
      (node (ref "C27") (pin "2") (pinfunction "2_2") (pintype "passive"))
      (node (ref "C28") (pin "2") (pinfunction "2_2") (pintype "passive"))
      (node (ref "C29") (pin "2") (pinfunction "2_2") (pintype "passive"))
      (node (ref "C3") (pin "2") (pinfunction "2_2") (pintype "passive"))
      (node (ref "C30") (pin "2") (pinfunction "2_2") (pintype "passive"))
      (node (ref "C31") (pin "2") (pinfunction "2_2") (pintype "passive"))
      (node (ref "C32") (pin "2") (pinfunction "2_2") (pintype "passive"))
      (node (ref "C33") (pin "2") (pinfunction "2_2") (pintype "passive"))
      (node (ref "C34") (pin "2") (pinfunction "2_2") (pintype "passive"))
      (node (ref "C35") (pin "2") (pinfunction "2_2") (pintype "passive"))
      (node (ref "C36") (pin "1") (pinfunction "1_1") (pintype "passive"))
      (node (ref "C37") (pin "2") (pinfunction "2_2") (pintype "passive"))
      (node (ref "C38") (pin "2") (pinfunction "2_2") (pintype "passive"))
      (node (ref "C4") (pin "2") (pinfunction "2_2") (pintype "passive"))
      (node (ref "C40") (pin "1") (pinfunction "1_1") (pintype "passive"))
      (node (ref "C41") (pin "2") (pinfunction "2_2") (pintype "passive"))
      (node (ref "C42") (pin "2") (pinfunction "2_2") (pintype "passive"))
      (node (ref "C43") (pin "2") (pinfunction "2_2") (pintype "passive"))
      (node (ref "C44") (pin "1") (pinfunction "1_1") (pintype "passive"))
      (node (ref "C45") (pin "2") (pinfunction "2_2") (pintype "passive"))
      (node (ref "C46") (pin "2") (pinfunction "2_2") (pintype "passive"))
      (node (ref "C47") (pin "2") (pinfunction "2_2") (pintype "passive"))
      (node (ref "C48") (pin "2") (pinfunction "2_2") (pintype "passive"))
      (node (ref "C49") (pin "2") (pinfunction "2_2") (pintype "passive"))
      (node (ref "C5") (pin "2") (pinfunction "2_2") (pintype "passive"))
      (node (ref "C50") (pin "2") (pinfunction "2_2") (pintype "passive"))
      (node (ref "C51") (pin "2") (pinfunction "2_2") (pintype "passive"))
      (node (ref "C52") (pin "2") (pinfunction "2_2") (pintype "passive"))
      (node (ref "C53") (pin "2") (pinfunction "2_2") (pintype "passive"))
      (node (ref "C54") (pin "2") (pinfunction "2_2") (pintype "passive"))
      (node (ref "C57") (pin "2") (pinfunction "2_2") (pintype "passive"))
      (node (ref "C58") (pin "2") (pinfunction "2_2") (pintype "passive"))
      (node (ref "C59") (pin "1") (pinfunction "1_1") (pintype "passive"))
      (node (ref "C6") (pin "2") (pinfunction "2_2") (pintype "passive"))
      (node (ref "C60") (pin "2") (pinfunction "2_2") (pintype "passive"))
      (node (ref "C61") (pin "2") (pinfunction "2_2") (pintype "passive"))
      (node (ref "C62") (pin "2") (pinfunction "2_2") (pintype "passive"))
      (node (ref "C63") (pin "2") (pinfunction "2_2") (pintype "passive"))
      (node (ref "C65") (pin "2") (pinfunction "2_2") (pintype "passive"))
      (node (ref "C66") (pin "2") (pinfunction "2_2") (pintype "passive"))
      (node (ref "C68") (pin "2") (pinfunction "2_2") (pintype "passive"))
      (node (ref "C69") (pin "2") (pinfunction "2_2") (pintype "passive"))
      (node (ref "C7") (pin "2") (pinfunction "2_2") (pintype "passive"))
      (node (ref "C70") (pin "2") (pinfunction "2_2") (pintype "passive"))
      (node (ref "C71") (pin "2") (pinfunction "2_2") (pintype "passive"))
      (node (ref "C72") (pin "2") (pinfunction "2_2") (pintype "passive"))
      (node (ref "C73") (pin "2") (pinfunction "2_2") (pintype "passive"))
      (node (ref "C74") (pin "2") (pinfunction "2_2") (pintype "passive"))
      (node (ref "C75") (pin "2") (pinfunction "2_2") (pintype "passive"))
      (node (ref "C76") (pin "2") (pinfunction "2_2") (pintype "passive"))
      (node (ref "C77") (pin "2") (pinfunction "2_2") (pintype "passive"))
      (node (ref "C78") (pin "2") (pinfunction "2_2") (pintype "passive"))
      (node (ref "C79") (pin "2") (pinfunction "2_2") (pintype "passive"))
      (node (ref "C8") (pin "2") (pinfunction "2_2") (pintype "passive"))
      (node (ref "C80") (pin "1") (pinfunction "1_1") (pintype "passive"))
      (node (ref "C81") (pin "1") (pinfunction "1_1") (pintype "passive"))
      (node (ref "C82") (pin "1") (pinfunction "1_1") (pintype "passive"))
      (node (ref "C83") (pin "2") (pinfunction "2_2") (pintype "passive"))
      (node (ref "C84") (pin "2") (pinfunction "2_2") (pintype "passive"))
      (node (ref "C85") (pin "2") (pinfunction "2_2") (pintype "passive"))
      (node (ref "C86") (pin "1") (pinfunction "1_1") (pintype "passive"))
      (node (ref "C87") (pin "1") (pinfunction "1_1") (pintype "passive"))
      (node (ref "C88") (pin "1") (pinfunction "1_1") (pintype "passive"))
      (node (ref "C89") (pin "1") (pinfunction "1_1") (pintype "passive"))
      (node (ref "C90") (pin "1") (pinfunction "1_1") (pintype "passive"))
      (node (ref "C91") (pin "2") (pinfunction "2_2") (pintype "passive"))
      (node (ref "C92") (pin "1") (pinfunction "1_1") (pintype "passive"))
      (node (ref "C93") (pin "1") (pinfunction "1_1") (pintype "passive"))
      (node (ref "C94") (pin "1") (pinfunction "1_1") (pintype "passive"))
      (node (ref "GND") (pin "P$1") (pinfunction "TP_P$1") (pintype "input"))
      (node (ref "IC10") (pin "107") (pinfunction "VSS_7_107") (pintype "bidirectional"))
      (node (ref "IC10") (pin "120") (pinfunction "VSS_8_120") (pintype "bidirectional"))
      (node (ref "IC10") (pin "130") (pinfunction "VSS_9_130") (pintype "bidirectional"))
      (node (ref "IC10") (pin "16") (pinfunction "VSS_1_16") (pintype "bidirectional"))
      (node (ref "IC10") (pin "31") (pinfunction "VSSA_31") (pintype "bidirectional"))
      (node (ref "IC10") (pin "38") (pinfunction "VSS_2_38") (pintype "bidirectional"))
      (node (ref "IC10") (pin "51") (pinfunction "VSS_3_51") (pintype "bidirectional"))
      (node (ref "IC10") (pin "61") (pinfunction "VSS_4_61") (pintype "bidirectional"))
      (node (ref "IC10") (pin "83") (pinfunction "VSS_5_83") (pintype "bidirectional"))
      (node (ref "IC10") (pin "94") (pinfunction "VSS_6_94") (pintype "bidirectional"))
      (node (ref "IC11") (pin "10") (pinfunction "AGNDL_10") (pintype "bidirectional"))
      (node (ref "IC11") (pin "15") (pinfunction "AGNDR_15") (pintype "bidirectional"))
      (node (ref "IC11") (pin "5") (pinfunction "DGND_5") (pintype "bidirectional"))
      (node (ref "IC12") (pin "2") (pinfunction "2_2") (pintype "bidirectional"))
      (node (ref "IC12") (pin "5") (pinfunction "5_5") (pintype "bidirectional"))
      (node (ref "IC13") (pin "2") (pinfunction "GND_2") (pintype "power_in"))
      (node (ref "IC17") (pin "2") (pinfunction "AGND_1_2") (pintype "bidirectional"))
      (node (ref "IC17") (pin "26") (pinfunction "AGND_2_26") (pintype "bidirectional"))
      (node (ref "IC17") (pin "35") (pinfunction "AGND_3_35") (pintype "bidirectional"))
      (node (ref "IC17") (pin "40") (pinfunction "AGND_4_40") (pintype "bidirectional"))
      (node (ref "IC17") (pin "41") (pinfunction "AGND_5_41") (pintype "bidirectional"))
      (node (ref "IC17") (pin "43") (pinfunction "REFGND_1_43") (pintype "bidirectional"))
      (node (ref "IC17") (pin "46") (pinfunction "REFGND_2_46") (pintype "bidirectional"))
      (node (ref "IC17") (pin "47") (pinfunction "AGND_6_47") (pintype "bidirectional"))
      (node (ref "IC17") (pin "50") (pinfunction "V1GND_50") (pintype "bidirectional"))
      (node (ref "IC17") (pin "52") (pinfunction "V2GND_52") (pintype "bidirectional"))
      (node (ref "IC17") (pin "54") (pinfunction "V3GND_54") (pintype "bidirectional"))
      (node (ref "IC17") (pin "55") (pinfunction "AGND_7_55") (pintype "bidirectional"))
      (node (ref "IC17") (pin "56") (pinfunction "AGND_8_56") (pintype "bidirectional"))
      (node (ref "IC17") (pin "58") (pinfunction "V4GND_58") (pintype "bidirectional"))
      (node (ref "IC17") (pin "60") (pinfunction "V5GND_60") (pintype "bidirectional"))
      (node (ref "IC17") (pin "62") (pinfunction "V6GND_62") (pintype "bidirectional"))
      (node (ref "IC17") (pin "63") (pinfunction "AGND_9_63") (pintype "bidirectional"))
      (node (ref "IC17") (pin "64") (pinfunction "AGND_10_64") (pintype "bidirectional"))
      (node (ref "IC2") (pin "6") (pinfunction "GND_6") (pintype "bidirectional"))
      (node (ref "IC3") (pin "10") (pinfunction "AGNDL_10") (pintype "bidirectional"))
      (node (ref "IC3") (pin "15") (pinfunction "AGNDR_15") (pintype "bidirectional"))
      (node (ref "IC3") (pin "5") (pinfunction "DGND_5") (pintype "bidirectional"))
      (node (ref "IC5") (pin "3") (pinfunction "+IN_3") (pintype "input"))
      (node (ref "IC5") (pin "5") (pinfunction "+IN_5") (pintype "input"))
      (node (ref "IC6") (pin "25") (pinfunction "EP_VSS_25") (pintype "power_in"))
      (node (ref "IC8") (pin "3") (pinfunction "+IN_3") (pintype "input"))
      (node (ref "IC8") (pin "5") (pinfunction "+IN_5") (pintype "input"))
      (node (ref "IN_LEFT") (pin "1") (pinfunction "REF_1") (pintype "passive"))
      (node (ref "IN_RIGHT") (pin "1") (pinfunction "REF_1") (pintype "passive"))
      (node (ref "OUT_LEFT") (pin "3") (pinfunction "GND_3") (pintype "input"))
      (node (ref "OUT_RIGHT") (pin "3") (pinfunction "GND_3") (pintype "input"))
      (node (ref "PROG.") (pin "4") (pinfunction "4_4") (pintype "bidirectional"))
      (node (ref "R1") (pin "2") (pinfunction "2_2") (pintype "passive"))
      (node (ref "R104") (pin "2") (pinfunction "2_2") (pintype "passive"))
      (node (ref "R13") (pin "1") (pinfunction "1_1") (pintype "passive"))
      (node (ref "R14") (pin "2") (pinfunction "2_2") (pintype "passive"))
      (node (ref "R15") (pin "2") (pinfunction "2_2") (pintype "passive"))
      (node (ref "R16") (pin "2") (pinfunction "2_2") (pintype "passive"))
      (node (ref "R27") (pin "1") (pinfunction "1_1") (pintype "passive"))
      (node (ref "R47") (pin "1") (pinfunction "1_1") (pintype "passive"))
      (node (ref "R5") (pin "1") (pinfunction "1_1") (pintype "passive"))
      (node (ref "R6") (pin "1") (pinfunction "1_1") (pintype "passive"))
      (node (ref "R69") (pin "2") (pinfunction "2_2") (pintype "passive"))
      (node (ref "R76") (pin "1") (pinfunction "1_1") (pintype "passive"))
      (node (ref "R77") (pin "2") (pinfunction "2_2") (pintype "passive"))
      (node (ref "R78") (pin "2") (pinfunction "2_2") (pintype "passive"))
      (node (ref "R83") (pin "1") (pinfunction "1_1") (pintype "passive"))
      (node (ref "R84") (pin "1") (pinfunction "1_1") (pintype "passive"))
      (node (ref "R85") (pin "1") (pinfunction "1_1") (pintype "passive"))
      (node (ref "S1") (pin "1") (pinfunction "1_1") (pintype "bidirectional"))
      (node (ref "S1") (pin "2") (pinfunction "2_2") (pintype "bidirectional"))
      (node (ref "STARGROUND") (pin "P$1") (pinfunction "TP_P$1") (pintype "input"))
      (node (ref "TP01") (pin "P$1") (pinfunction "TP_P$1") (pintype "input"))
      (node (ref "TP02") (pin "P$1") (pinfunction "TP_P$1") (pintype "input"))
      (node (ref "TP08") (pin "P$1") (pinfunction "TP_P$1") (pintype "input"))
      (node (ref "TP09") (pin "P$1") (pinfunction "TP_P$1") (pintype "input"))
      (node (ref "U1") (pin "2") (pinfunction "GND_2") (pintype "passive"))
      (node (ref "U4") (pin "2") (pinfunction "IN-_2") (pintype "input"))
      (node (ref "U6") (pin "1") (pinfunction "REF_1") (pintype "passive"))
      (node (ref "U7") (pin "2") (pinfunction "IN-_2") (pintype "input"))
      (node (ref "U8") (pin "1") (pinfunction "REF_1") (pintype "passive"))
      (node (ref "VCA1(LEFT)") (pin "3") (pinfunction "EC-_3") (pintype "output"))
      (node (ref "VCA1(LEFT)") (pin "6") (pinfunction "GND_6") (pintype "passive"))
      (node (ref "VCA2(RIGHT)") (pin "3") (pinfunction "EC-_3") (pintype "output"))
      (node (ref "VCA2(RIGHT)") (pin "6") (pinfunction "GND_6") (pintype "passive"))
      (node (ref "X1") (pin "4") (pinfunction "4_4") (pintype "bidirectional"))
      (node (ref "X2") (pin "2") (pinfunction "KL_2") (pintype "passive"))
      (node (ref "X2") (pin "3") (pinfunction "KL_3") (pintype "passive"))
    )
    (net (code "14") (name "A_GND_TO_STAR") (class "Default")
      (node (ref "ANALOG_VOLT_IN") (pin "3") (pinfunction "3_3") (pintype "bidirectional"))
      (node (ref "ANALOG_VOLT_IN") (pin "4") (pinfunction "4_4") (pintype "bidirectional"))
      (node (ref "R16") (pin "1") (pinfunction "1_1") (pintype "passive"))
    )
    (net (code "15") (name "BOOT0") (class "Default")
      (node (ref "C36") (pin "2") (pinfunction "2_2") (pintype "passive"))
      (node (ref "IC10") (pin "138") (pinfunction "BOOT0_138") (pintype "bidirectional"))
      (node (ref "R31") (pin "1") (pinfunction "1_1") (pintype "passive"))
      (node (ref "R78") (pin "1") (pinfunction "1_1") (pintype "passive"))
    )
    (net (code "16") (name "BOTTOM") (class "Default")
      (node (ref "R2") (pin "2") (pinfunction "2_2") (pintype "passive"))
    )
    (net (code "17") (name "BUSY") (class "Default")
      (node (ref "IC10") (pin "88") (pinfunction "PG3_88") (pintype "bidirectional"))
      (node (ref "IC17") (pin "14") (pinfunction "BUSY_14") (pintype "bidirectional"))
    )
    (net (code "18") (name "CHASSIS") (class "Default")
      (node (ref "C106") (pin "2") (pinfunction "2_2") (pintype "passive"))
      (node (ref "C107") (pin "2") (pinfunction "2_2") (pintype "passive"))
      (node (ref "C108") (pin "2") (pinfunction "2_2") (pintype "passive"))
      (node (ref "C109") (pin "2") (pinfunction "2_2") (pintype "passive"))
      (node (ref "C15") (pin "1") (pinfunction "1_1") (pintype "passive"))
      (node (ref "C18") (pin "1") (pinfunction "1_1") (pintype "passive"))
      (node (ref "IN1(R/S)") (pin "1") (pinfunction "1_1") (pintype "bidirectional"))
      (node (ref "IN2(L/M)") (pin "1") (pinfunction "1_1") (pintype "bidirectional"))
      (node (ref "OUT1(R/S)") (pin "1") (pinfunction "1_1") (pintype "bidirectional"))
      (node (ref "OUT1(R/S)") (pin "G") (pinfunction "G_G") (pintype "bidirectional"))
      (node (ref "OUT2(L/M)") (pin "1") (pinfunction "1_1") (pintype "bidirectional"))
      (node (ref "OUT2(L/M)") (pin "G") (pinfunction "G_G") (pintype "bidirectional"))
      (node (ref "R1") (pin "1") (pinfunction "1_1") (pintype "passive"))
      (node (ref "R2") (pin "1") (pinfunction "1_1") (pintype "passive"))
      (node (ref "R91") (pin "1") (pinfunction "1_1") (pintype "passive"))
      (node (ref "X1") (pin "P$1") (pinfunction "P$1_P$1") (pintype "bidirectional"))
      (node (ref "X1") (pin "P$2") (pinfunction "P$2_P$2") (pintype "bidirectional"))
      (node (ref "X2") (pin "1") (pinfunction "KL_1") (pintype "passive"))
    )
    (net (code "19") (name "CS") (class "Default")
      (node (ref "IC10") (pin "123") (pinfunction "PD7_123") (pintype "bidirectional"))
      (node (ref "IC17") (pin "13") (pinfunction "~{CS}_13") (pintype "bidirectional"))
    )
    (net (code "20") (name "CS_DAC1") (class "Default")
      (node (ref "IC10") (pin "134") (pinfunction "PB4_134") (pintype "bidirectional"))
      (node (ref "R94") (pin "2") (pinfunction "2_2") (pintype "passive"))
    )
    (net (code "21") (name "CS_POTI") (class "Default")
      (node (ref "IC10") (pin "135") (pinfunction "PB5_135") (pintype "bidirectional"))
      (node (ref "R28") (pin "2") (pinfunction "2_2") (pintype "passive"))
      (node (ref "R44") (pin "2") (pinfunction "2_2") (pintype "passive"))
    )
    (net (code "22") (name "CV_A_B") (class "Default")
      (node (ref "IC10") (pin "113") (pinfunction "PC12_113") (pintype "bidirectional"))
      (node (ref "IC17") (pin "10") (pinfunction "CONVST_B_10") (pintype "bidirectional"))
      (node (ref "IC17") (pin "9") (pinfunction "CONVST_A_9") (pintype "bidirectional"))
    )
    (net (code "23") (name "DAC2_OUT1(OFFSET_VCA1)") (class "Default")
      (node (ref "IC9") (pin "3") (pinfunction "+IN_3") (pintype "input"))
      (node (ref "R74") (pin "2") (pinfunction "2_2") (pintype "passive"))
      (node (ref "R76") (pin "2") (pinfunction "2_2") (pintype "passive"))
    )
    (net (code "24") (name "DAC2_OUT2(OFFSET_VCA2)") (class "Default")
      (node (ref "IC9") (pin "5") (pinfunction "+IN_5") (pintype "input"))
      (node (ref "R47") (pin "2") (pinfunction "2_2") (pintype "passive"))
      (node (ref "R75") (pin "2") (pinfunction "2_2") (pintype "passive"))
    )
    (net (code "25") (name "DAC_OUT1") (class "Default")
      (node (ref "IC10") (pin "40") (pinfunction "PA4_40") (pintype "bidirectional"))
      (node (ref "R57") (pin "1") (pinfunction "1_1") (pintype "passive"))
    )
    (net (code "26") (name "DAC_OUT2") (class "Default")
      (node (ref "IC10") (pin "41") (pinfunction "PA5_41") (pintype "bidirectional"))
      (node (ref "R55") (pin "1") (pinfunction "1_1") (pintype "passive"))
    )
    (net (code "27") (name "DB0") (class "Default")
      (node (ref "IC10") (pin "141") (pinfunction "PE0_141") (pintype "bidirectional"))
      (node (ref "IC17") (pin "16") (pinfunction "DB0_16") (pintype "bidirectional"))
    )
    (net (code "28") (name "DB1") (class "Default")
      (node (ref "IC10") (pin "142") (pinfunction "PE1_142") (pintype "bidirectional"))
      (node (ref "IC17") (pin "17") (pinfunction "DB1_17") (pintype "bidirectional"))
    )
    (net (code "29") (name "DB2") (class "Default")
      (node (ref "IC10") (pin "1") (pinfunction "PE2_1") (pintype "bidirectional"))
      (node (ref "IC17") (pin "18") (pinfunction "DB2_18") (pintype "bidirectional"))
    )
    (net (code "30") (name "DB3") (class "Default")
      (node (ref "IC10") (pin "2") (pinfunction "PE3_2") (pintype "bidirectional"))
      (node (ref "IC17") (pin "19") (pinfunction "DB3_19") (pintype "bidirectional"))
    )
    (net (code "31") (name "DB4") (class "Default")
      (node (ref "IC10") (pin "3") (pinfunction "PE4_3") (pintype "bidirectional"))
      (node (ref "IC17") (pin "20") (pinfunction "DB4_20") (pintype "bidirectional"))
    )
    (net (code "32") (name "DB5") (class "Default")
      (node (ref "IC10") (pin "4") (pinfunction "PE5_4") (pintype "bidirectional"))
      (node (ref "IC17") (pin "21") (pinfunction "DB5_21") (pintype "bidirectional"))
    )
    (net (code "33") (name "DB6") (class "Default")
      (node (ref "IC10") (pin "5") (pinfunction "PE6_5") (pintype "bidirectional"))
      (node (ref "IC17") (pin "22") (pinfunction "DB6_22") (pintype "bidirectional"))
    )
    (net (code "34") (name "DB7") (class "Default")
      (node (ref "IC10") (pin "58") (pinfunction "PE7_58") (pintype "bidirectional"))
      (node (ref "IC17") (pin "24") (pinfunction "DB7/DOUTA_24") (pintype "bidirectional"))
    )
    (net (code "35") (name "DB8") (class "Default")
      (node (ref "IC10") (pin "59") (pinfunction "PE8_59") (pintype "bidirectional"))
      (node (ref "IC17") (pin "25") (pinfunction "DB8/DOUTB_25") (pintype "bidirectional"))
    )
    (net (code "36") (name "DB9") (class "Default")
      (node (ref "IC10") (pin "60") (pinfunction "PE9_60") (pintype "bidirectional"))
      (node (ref "IC17") (pin "27") (pinfunction "DB9_27") (pintype "bidirectional"))
    )
    (net (code "37") (name "DB10") (class "Default")
      (node (ref "IC10") (pin "63") (pinfunction "PE10_63") (pintype "bidirectional"))
      (node (ref "IC17") (pin "28") (pinfunction "DB10_28") (pintype "bidirectional"))
    )
    (net (code "38") (name "DB11") (class "Default")
      (node (ref "IC10") (pin "64") (pinfunction "PE11_64") (pintype "bidirectional"))
      (node (ref "IC17") (pin "29") (pinfunction "DB11_29") (pintype "bidirectional"))
    )
    (net (code "39") (name "DB12") (class "Default")
      (node (ref "IC10") (pin "65") (pinfunction "PE12_65") (pintype "bidirectional"))
      (node (ref "IC17") (pin "30") (pinfunction "DB12_30") (pintype "bidirectional"))
    )
    (net (code "40") (name "DB13") (class "Default")
      (node (ref "IC10") (pin "66") (pinfunction "PE13_66") (pintype "bidirectional"))
      (node (ref "IC17") (pin "31") (pinfunction "DB13_31") (pintype "bidirectional"))
    )
    (net (code "41") (name "DB14") (class "Default")
      (node (ref "IC10") (pin "67") (pinfunction "PE14_67") (pintype "bidirectional"))
      (node (ref "IC17") (pin "32") (pinfunction "DB14/HBEN_32") (pintype "bidirectional"))
    )
    (net (code "42") (name "DB15") (class "Default")
      (node (ref "IC10") (pin "68") (pinfunction "PE15_68") (pintype "bidirectional"))
      (node (ref "IC17") (pin "33") (pinfunction "DB15/BYTE_SEL_33") (pintype "bidirectional"))
    )
    (net (code "43") (name "DEBUG1") (class "Default")
      (node (ref "DEBUG1") (pin "P$1") (pinfunction "TP_P$1") (pintype "input"))
      (node (ref "IC10") (pin "21") (pinfunction "PF9_21") (pintype "bidirectional"))
    )
    (net (code "44") (name "DEBUG2") (class "Default")
      (node (ref "DEBUG2") (pin "P$1") (pinfunction "TP_P$1") (pintype "input"))
      (node (ref "IC10") (pin "115") (pinfunction "PD1_115") (pintype "bidirectional"))
    )
    (net (code "45") (name "DIN_DAC") (class "Default")
      (node (ref "IC10") (pin "29") (pinfunction "PC3_29") (pintype "bidirectional"))
      (node (ref "R4") (pin "2") (pinfunction "2_2") (pintype "passive"))
      (node (ref "R93") (pin "2") (pinfunction "2_2") (pintype "passive"))
      (node (ref "TP04") (pin "P$1") (pinfunction "TP_P$1") (pintype "input"))
    )
    (net (code "46") (name "DISPLAY_GND_TO_STAR") (class "Default")
      (node (ref "C39") (pin "2") (pinfunction "2_2") (pintype "passive"))
      (node (ref "C99") (pin "2") (pinfunction "2_2") (pintype "passive"))
      (node (ref "DISPLAY1") (pin "4") (pinfunction "4_4") (pintype "bidirectional"))
      (node (ref "R69") (pin "1") (pinfunction "1_1") (pintype "passive"))
    )
    (net (code "47") (name "D_GND_TO_STAR") (class "Default")
      (node (ref "DIGITAL_VOLT") (pin "3") (pinfunction "3_3") (pintype "bidirectional"))
      (node (ref "R15") (pin "1") (pinfunction "1_1") (pintype "passive"))
    )
    (net (code "48") (name "EC+_VCA1(LFT)") (class "Default")
      (node (ref "C120") (pin "2") (pinfunction "2_2") (pintype "passive"))
      (node (ref "IC9") (pin "1") (pinfunction "OUT_1") (pintype "output"))
      (node (ref "R56") (pin "2") (pinfunction "2_2") (pintype "passive"))
      (node (ref "TP37") (pin "P$1") (pinfunction "TP_P$1") (pintype "input"))
      (node (ref "VCA1(LEFT)") (pin "2") (pinfunction "EC+_2") (pintype "passive"))
    )
    (net (code "49") (name "EC+_VCA2(RIGHT)") (class "Default")
      (node (ref "C121") (pin "2") (pinfunction "2_2") (pintype "passive"))
      (node (ref "IC9") (pin "7") (pinfunction "OUT_7") (pintype "output"))
      (node (ref "R54") (pin "2") (pinfunction "2_2") (pintype "passive"))
      (node (ref "TP36") (pin "P$1") (pinfunction "TP_P$1") (pintype "input"))
      (node (ref "VCA2(RIGHT)") (pin "2") (pinfunction "EC+_2") (pintype "passive"))
    )
    (net (code "50") (name "ETHERNET_CHASSIS") (class "Default")
      (node (ref "C101") (pin "2") (pinfunction "2_2") (pintype "passive"))
      (node (ref "J1") (pin "MP1") (pinfunction "13_MP1") (pintype "bidirectional"))
      (node (ref "J1") (pin "MP2") (pinfunction "14_MP2") (pintype "bidirectional"))
      (node (ref "R91") (pin "2") (pinfunction "2_2") (pintype "passive"))
    )
    (net (code "51") (name "FRST") (class "Default")
      (node (ref "IC10") (pin "122") (pinfunction "PD6_122") (pintype "bidirectional"))
      (node (ref "IC17") (pin "15") (pinfunction "FRSTDATA_15") (pintype "bidirectional"))
    )
    (net (code "52") (name "L") (class "Default")
      (node (ref "IC11") (pin "16") (pinfunction "VINR_16") (pintype "bidirectional"))
      (node (ref "IC4") (pin "3") (pinfunction "+IN_3") (pintype "input"))
      (node (ref "IN_LEFT") (pin "5") (pinfunction "SEN_5") (pintype "output"))
      (node (ref "IN_LEFT") (pin "6") (pinfunction "OUT_6") (pintype "output"))
      (node (ref "K5") (pin "Q1") (pinfunction "O_Q1") (pintype "passive"))
    )
    (net (code "53") (name "LD1") (class "Default")
      (node (ref "IC10") (pin "46") (pinfunction "PB0_46") (pintype "bidirectional"))
      (node (ref "LD1") (pin "2") (pinfunction "+_2") (pintype "passive"))
    )
    (net (code "54") (name "LD2") (class "Default")
      (node (ref "IC10") (pin "137") (pinfunction "PB7_137") (pintype "bidirectional"))
      (node (ref "LD2") (pin "2") (pinfunction "+_2") (pintype "passive"))
    )
    (net (code "55") (name "LD3") (class "Default")
      (node (ref "IC10") (pin "75") (pinfunction "PB14_75") (pintype "bidirectional"))
      (node (ref "LD3") (pin "2") (pinfunction "+_2") (pintype "passive"))
    )
    (net (code "56") (name "LED1") (class "Default")
      (node (ref "IC6") (pin "3") (pinfunction "LED1/NINT/NPME/~{REGOFF}_3") (pintype "input"))
      (node (ref "J1") (pin "10") (pinfunction "YELLOW_A_10") (pintype "bidirectional"))
    )
    (net (code "57") (name "LED2") (class "Default")
      (node (ref "IC6") (pin "2") (pinfunction "LED2/NINT/NPME/~{NINTSEL}_2") (pintype "input"))
      (node (ref "J1") (pin "12") (pinfunction "GREEN_A_12") (pintype "bidirectional"))
      (node (ref "R85") (pin "2") (pinfunction "2_2") (pintype "passive"))
    )
    (net (code "58") (name "L{slash}M_IN(VCA1_IN)") (class "Default")
      (node (ref "C102") (pin "1") (pinfunction "1_1") (pintype "passive"))
      (node (ref "IC17") (pin "49") (pinfunction "V1_49") (pintype "bidirectional"))
      (node (ref "K5") (pin "P1") (pinfunction "P_P1") (pintype "passive"))
    )
    (net (code "59") (name "L{slash}M_OUT(OUT_STAGE_LEFT)") (class "Default")
      (node (ref "IC1") (pin "3") (pinfunction "+IN_3") (pintype "input"))
      (node (ref "IC5") (pin "1") (pinfunction "OUT_1") (pintype "output"))
      (node (ref "K6") (pin "Q1") (pinfunction "O_Q1") (pintype "passive"))
      (node (ref "R39") (pin "2") (pinfunction "2_2") (pintype "passive"))
    )
    (net (code "60") (name "L{slash}M_OUT(OUT_STAGE_LEFT)_BEFORE") (class "Default")
      (node (ref "IC17") (pin "59") (pinfunction "V5_59") (pintype "bidirectional"))
    )
    (net (code "61") (name "L{slash}M_OUT(VCA1_OUT)") (class "Default")
      (node (ref "C55") (pin "2") (pinfunction "2_2") (pintype "passive"))
      (node (ref "IC11") (pin "9") (pinfunction "VINL_9") (pintype "bidirectional"))
      (node (ref "IC17") (pin "53") (pinfunction "V3_53") (pintype "bidirectional"))
      (node (ref "IC8") (pin "1") (pinfunction "OUT_1") (pintype "output"))
      (node (ref "R48") (pin "2") (pinfunction "2_2") (pintype "passive"))
    )
    (net (code "62") (name "M") (class "Default")
      (node (ref "K5") (pin "S1") (pinfunction "S_S1") (pintype "passive"))
      (node (ref "U4") (pin "5") (pinfunction "SEN_5") (pintype "output"))
      (node (ref "U4") (pin "6") (pinfunction "OUT_6") (pintype "output"))
    )
    (net (code "63") (name "MUTE_POTI") (class "Default")
      (node (ref "IC10") (pin "79") (pinfunction "PD10_79") (pintype "bidirectional"))
      (node (ref "R3") (pin "2") (pinfunction "2_2") (pintype "passive"))
    )
    (net (code "64") (name "N$47") (class "Default")
      (node (ref "C107") (pin "1") (pinfunction "1_1") (pintype "passive"))
      (node (ref "D2") (pin "2") (pinfunction "A_2") (pintype "input"))
      (node (ref "D3") (pin "1") (pinfunction "K_1") (pintype "output"))
      (node (ref "FB2") (pin "1") (pinfunction "1_1") (pintype "bidirectional"))
      (node (ref "K3") (pin "P2") (pinfunction "P_P2") (pintype "passive"))
    )
    (net (code "65") (name "N$85") (class "Default")
      (node (ref "C109") (pin "1") (pinfunction "1_1") (pintype "passive"))
      (node (ref "D10") (pin "1") (pinfunction "K_1") (pintype "output"))
      (node (ref "D8") (pin "2") (pinfunction "A_2") (pintype "input"))
      (node (ref "FB3") (pin "1") (pinfunction "1_1") (pintype "bidirectional"))
      (node (ref "K2") (pin "P2") (pinfunction "P_P2") (pintype "passive"))
    )
    (net (code "66") (name "NEGATIVE_IN(L{slash}M)") (class "Default")
      (node (ref "IN2(L/M)") (pin "3") (pinfunction "3_3") (pintype "bidirectional"))
      (node (ref "K4") (pin "P1") (pinfunction "P_P1") (pintype "passive"))
    )
    (net (code "67") (name "NEGATIVE_IN(R{slash}S)") (class "Default")
      (node (ref "IN1(R/S)") (pin "3") (pinfunction "3_3") (pintype "bidirectional"))
      (node (ref "K1") (pin "P1") (pinfunction "P_P1") (pintype "passive"))
    )
    (net (code "68") (name "NEGATIVE_OUT(L{slash}M)") (class "Default")
      (node (ref "C106") (pin "1") (pinfunction "1_1") (pintype "passive"))
      (node (ref "D1") (pin "2") (pinfunction "A_2") (pintype "input"))
      (node (ref "D4") (pin "1") (pinfunction "K_1") (pintype "output"))
      (node (ref "FB1") (pin "1") (pinfunction "1_1") (pintype "bidirectional"))
      (node (ref "K3") (pin "P1") (pinfunction "P_P1") (pintype "passive"))
    )
    (net (code "69") (name "NGATIVE_OUT(R{slash}S)") (class "Default")
      (node (ref "C108") (pin "1") (pinfunction "1_1") (pintype "passive"))
      (node (ref "D5") (pin "2") (pinfunction "A_2") (pintype "input"))
      (node (ref "D9") (pin "1") (pinfunction "K_1") (pintype "output"))
      (node (ref "FB4") (pin "1") (pinfunction "1_1") (pintype "bidirectional"))
      (node (ref "K2") (pin "P1") (pinfunction "P_P1") (pintype "passive"))
    )
    (net (code "70") (name "NRST") (class "Default")
      (node (ref "C44") (pin "2") (pinfunction "2_2") (pintype "passive"))
      (node (ref "IC10") (pin "25") (pinfunction "NRST_25") (pintype "bidirectional"))
      (node (ref "IC6") (pin "15") (pinfunction "NRST_15") (pintype "input"))
      (node (ref "PROG.") (pin "2") (pinfunction "2_2") (pintype "bidirectional"))
      (node (ref "S1") (pin "3") (pinfunction "3_3") (pintype "bidirectional"))
      (node (ref "S1") (pin "4") (pinfunction "4_4") (pintype "bidirectional"))
    )
    (net (code "71") (name "Net-(+3V3_OK-+)") (class "Default")
      (node (ref "+3V3_OK") (pin "2") (pinfunction "+_2") (pintype "passive"))
      (node (ref "R99") (pin "1") (pinfunction "1_1") (pintype "passive"))
    )
    (net (code "72") (name "Net-(+5V_OK-+)") (class "Default")
      (node (ref "+5V_OK") (pin "2") (pinfunction "+_2") (pintype "passive"))
      (node (ref "R100") (pin "1") (pinfunction "1_1") (pintype "passive"))
    )
    (net (code "73") (name "Net-(+15V_OK-+)") (class "Default")
      (node (ref "+15V_OK") (pin "2") (pinfunction "+_2") (pintype "passive"))
      (node (ref "R98") (pin "1") (pinfunction "1_1") (pintype "passive"))
    )
    (net (code "74") (name "Net-(-15V_OK--)") (class "Default")
      (node (ref "-15V_OK") (pin "1") (pinfunction "-_1") (pintype "passive"))
      (node (ref "R97") (pin "2") (pinfunction "2_2") (pintype "passive"))
    )
    (net (code "75") (name "Net-(C10-Pad1)") (class "Default")
      (node (ref "C10") (pin "1") (pinfunction "1_1") (pintype "passive"))
      (node (ref "C15") (pin "2") (pinfunction "2_2") (pintype "passive"))
      (node (ref "C9") (pin "2") (pinfunction "2_2") (pintype "passive"))
    )
    (net (code "76") (name "Net-(C16-Pad2)") (class "Default")
      (node (ref "C16") (pin "2") (pinfunction "2_2") (pintype "passive"))
      (node (ref "C17") (pin "1") (pinfunction "1_1") (pintype "passive"))
      (node (ref "C18") (pin "2") (pinfunction "2_2") (pintype "passive"))
    )
    (net (code "77") (name "Net-(C39-Pad1)") (class "Default")
      (node (ref "C39") (pin "1") (pinfunction "1_1") (pintype "passive"))
      (node (ref "DISPLAY1") (pin "3") (pinfunction "3_3") (pintype "bidirectional"))
      (node (ref "FB7") (pin "1") (pinfunction "1_1") (pintype "bidirectional"))
    )
    (net (code "78") (name "Net-(C67-Pad2)") (class "Default")
      (node (ref "C67") (pin "2") (pinfunction "2_2") (pintype "passive"))
      (node (ref "R53") (pin "1") (pinfunction "1_1") (pintype "passive"))
    )
    (net (code "79") (name "Net-(C101-Pad1)") (class "Default")
      (node (ref "C101") (pin "1") (pinfunction "1_1") (pintype "passive"))
      (node (ref "R29") (pin "1") (pinfunction "1_1") (pintype "passive"))
      (node (ref "R88") (pin "1") (pinfunction "1_1") (pintype "passive"))
      (node (ref "R89") (pin "1") (pinfunction "1_1") (pintype "passive"))
      (node (ref "R90") (pin "1") (pinfunction "1_1") (pintype "passive"))
    )
    (net (code "80") (name "Net-(C102-Pad2)") (class "Default")
      (node (ref "C102") (pin "2") (pinfunction "2_2") (pintype "passive"))
      (node (ref "R52") (pin "1") (pinfunction "1_1") (pintype "passive"))
    )
    (net (code "81") (name "Net-(FB1-Pad2)") (class "Default")
      (node (ref "FB1") (pin "2") (pinfunction "2_2") (pintype "bidirectional"))
      (node (ref "OUT2(L/M)") (pin "3") (pinfunction "3_3") (pintype "bidirectional"))
    )
    (net (code "82") (name "Net-(FB2-Pad2)") (class "Default")
      (node (ref "FB2") (pin "2") (pinfunction "2_2") (pintype "bidirectional"))
      (node (ref "OUT2(L/M)") (pin "2") (pinfunction "2_2") (pintype "bidirectional"))
    )
    (net (code "83") (name "Net-(FB3-Pad2)") (class "Default")
      (node (ref "FB3") (pin "2") (pinfunction "2_2") (pintype "bidirectional"))
      (node (ref "OUT1(R/S)") (pin "2") (pinfunction "2_2") (pintype "bidirectional"))
    )
    (net (code "84") (name "Net-(FB4-Pad2)") (class "Default")
      (node (ref "FB4") (pin "2") (pinfunction "2_2") (pintype "bidirectional"))
      (node (ref "OUT1(R/S)") (pin "3") (pinfunction "3_3") (pintype "bidirectional"))
    )
    (net (code "85") (name "Net-(IC1A--IN)") (class "Default")
      (node (ref "IC1") (pin "1") (pinfunction "OUT_1") (pintype "output"))
      (node (ref "IC1") (pin "2") (pinfunction "-IN_2") (pintype "input"))
      (node (ref "U7") (pin "3") (pinfunction "IN+_3") (pintype "input"))
      (node (ref "U8") (pin "3") (pinfunction "IN+_3") (pintype "input"))
    )
    (net (code "86") (name "Net-(IC1B--IN)") (class "Default")
      (node (ref "IC1") (pin "6") (pinfunction "-IN_6") (pintype "input"))
      (node (ref "IC1") (pin "7") (pinfunction "OUT_7") (pintype "output"))
      (node (ref "U7") (pin "1") (pinfunction "REF_1") (pintype "passive"))
      (node (ref "U8") (pin "2") (pinfunction "IN-_2") (pintype "input"))
    )
    (net (code "87") (name "Net-(IC2-DIN)") (class "Default")
      (node (ref "IC2") (pin "8") (pinfunction "DIN_8") (pintype "bidirectional"))
      (node (ref "R93") (pin "1") (pinfunction "1_1") (pintype "passive"))
    )
    (net (code "88") (name "Net-(IC2-SCLK)") (class "Default")
      (node (ref "IC2") (pin "10") (pinfunction "SCLK_10") (pintype "bidirectional"))
      (node (ref "R92") (pin "1") (pinfunction "1_1") (pintype "passive"))
    )
    (net (code "89") (name "Net-(IC2-VOUTA)") (class "Default")
      (node (ref "IC2") (pin "2") (pinfunction "VOUTA_2") (pintype "bidirectional"))
      (node (ref "R38") (pin "2") (pinfunction "2_2") (pintype "passive"))
    )
    (net (code "90") (name "Net-(IC2-VOUTB)") (class "Default")
      (node (ref "IC2") (pin "3") (pinfunction "VOUTB_3") (pintype "bidirectional"))
      (node (ref "R41") (pin "2") (pinfunction "2_2") (pintype "passive"))
    )
    (net (code "91") (name "Net-(IC2-VOUTC)") (class "Default")
      (node (ref "IC2") (pin "4") (pinfunction "VOUTC_4") (pintype "bidirectional"))
      (node (ref "R74") (pin "1") (pinfunction "1_1") (pintype "passive"))
    )
    (net (code "92") (name "Net-(IC2-VOUTD)") (class "Default")
      (node (ref "IC2") (pin "5") (pinfunction "VOUTD_5") (pintype "bidirectional"))
      (node (ref "R75") (pin "1") (pinfunction "1_1") (pintype "passive"))
    )
    (net (code "93") (name "Net-(IC2-~{SYNC})") (class "Default")
      (node (ref "IC2") (pin "9") (pinfunction "~{SYNC}_9") (pintype "bidirectional"))
      (node (ref "R94") (pin "1") (pinfunction "1_1") (pintype "passive"))
    )
    (net (code "94") (name "Net-(IC3-VOUTL)") (class "Default")
      (node (ref "IC3") (pin "11") (pinfunction "VOUTL_11") (pintype "bidirectional"))
      (node (ref "R46") (pin "1") (pinfunction "1_1") (pintype "passive"))
    )
    (net (code "95") (name "Net-(IC3-VOUTR)") (class "Default")
      (node (ref "IC3") (pin "14") (pinfunction "VOUTR_14") (pintype "bidirectional"))
      (node (ref "R58") (pin "1") (pinfunction "1_1") (pintype "passive"))
    )
    (net (code "96") (name "Net-(IC3-~{CS})") (class "Default")
      (node (ref "IC3") (pin "2") (pinfunction "~{CS}_2") (pintype "bidirectional"))
      (node (ref "R44") (pin "1") (pinfunction "1_1") (pintype "passive"))
    )
    (net (code "97") (name "Net-(IC4A--IN)") (class "Default")
      (node (ref "IC4") (pin "1") (pinfunction "OUT_1") (pintype "output"))
      (node (ref "IC4") (pin "2") (pinfunction "-IN_2") (pintype "input"))
      (node (ref "U4") (pin "3") (pinfunction "IN+_3") (pintype "input"))
      (node (ref "U6") (pin "3") (pinfunction "IN+_3") (pintype "input"))
    )
    (net (code "98") (name "Net-(IC5A--IN)") (class "Default")
      (node (ref "IC5") (pin "2") (pinfunction "-IN_2") (pintype "input"))
      (node (ref "R32") (pin "2") (pinfunction "2_2") (pintype "passive"))
      (node (ref "R39") (pin "1") (pinfunction "1_1") (pintype "passive"))
      (node (ref "R45") (pin "2") (pinfunction "2_2") (pintype "passive"))
    )
    (net (code "99") (name "Net-(IC5B--IN)") (class "Default")
      (node (ref "IC5") (pin "6") (pinfunction "-IN_6") (pintype "input"))
      (node (ref "R42") (pin "1") (pinfunction "1_1") (pintype "passive"))
      (node (ref "R46") (pin "2") (pinfunction "2_2") (pintype "passive"))
      (node (ref "R58") (pin "2") (pinfunction "2_2") (pintype "passive"))
    )
    (net (code "100") (name "Net-(IC6-CRS_DV{slash}~{MODE2})") (class "Default")
      (node (ref "IC6") (pin "11") (pinfunction "CRS_DV/~{MODE2}_11") (pintype "bidirectional"))
      (node (ref "R21") (pin "2") (pinfunction "2_2") (pintype "passive"))
      (node (ref "R26") (pin "2") (pinfunction "2_2") (pintype "passive"))
    )
    (net (code "101") (name "Net-(IC6-RBIAS)") (class "Default")
      (node (ref "IC6") (pin "24") (pinfunction "RBIAS_24") (pintype "bidirectional"))
      (node (ref "R77") (pin "1") (pinfunction "1_1") (pintype "passive"))
    )
    (net (code "102") (name "Net-(IC6-RXD0{slash}~{MODE0})") (class "Default")
      (node (ref "IC6") (pin "8") (pinfunction "RXD0/~{MODE0}_8") (pintype "bidirectional"))
      (node (ref "R20") (pin "2") (pinfunction "2_2") (pintype "passive"))
      (node (ref "R25") (pin "2") (pinfunction "2_2") (pintype "passive"))
    )
    (net (code "103") (name "Net-(IC6-RXD1{slash}~{MODE1})") (class "Default")
      (node (ref "IC6") (pin "7") (pinfunction "RXD1/~{MODE1}_7") (pintype "bidirectional"))
      (node (ref "R18") (pin "2") (pinfunction "2_2") (pintype "passive"))
      (node (ref "R24") (pin "2") (pinfunction "2_2") (pintype "passive"))
    )
    (net (code "104") (name "Net-(IC6-RXER{slash}~{PHYAD0})") (class "Default")
      (node (ref "IC6") (pin "10") (pinfunction "RXER/~{PHYAD0}_10") (pintype "bidirectional"))
      (node (ref "R27") (pin "2") (pinfunction "2_2") (pintype "passive"))
    )
    (net (code "105") (name "Net-(IC6-VDDCR)") (class "Default")
      (node (ref "C88") (pin "2") (pinfunction "2_2") (pintype "passive"))
      (node (ref "C89") (pin "2") (pinfunction "2_2") (pintype "passive"))
      (node (ref "IC6") (pin "6") (pinfunction "VDDCR_6") (pintype "power_in"))
    )
    (net (code "106") (name "Net-(IC6-XTAL1{slash}CLKIN)") (class "Default")
      (node (ref "C100") (pin "2") (pinfunction "2_2") (pintype "passive"))
      (node (ref "IC6") (pin "5") (pinfunction "XTAL1/CLKIN_5") (pintype "input"))
      (node (ref "Y3") (pin "2") (pinfunction "2_2") (pintype "bidirectional"))
    )
    (net (code "107") (name "Net-(IC6-XTAL2)") (class "Default")
      (node (ref "C40") (pin "2") (pinfunction "2_2") (pintype "passive"))
      (node (ref "IC6") (pin "4") (pinfunction "XTAL2_4") (pintype "bidirectional"))
      (node (ref "Y3") (pin "1") (pinfunction "1_1") (pintype "bidirectional"))
    )
    (net (code "108") (name "Net-(IC8A--IN)") (class "Default")
      (node (ref "C55") (pin "1") (pinfunction "1_1") (pintype "passive"))
      (node (ref "IC8") (pin "2") (pinfunction "-IN_2") (pintype "input"))
      (node (ref "R48") (pin "1") (pinfunction "1_1") (pintype "passive"))
      (node (ref "VCA1(LEFT)") (pin "8") (pinfunction "OUT_8") (pintype "output"))
    )
    (net (code "109") (name "Net-(IC8B--IN)") (class "Default")
      (node (ref "C56") (pin "1") (pinfunction "1_1") (pintype "passive"))
      (node (ref "IC8") (pin "6") (pinfunction "-IN_6") (pintype "input"))
      (node (ref "R49") (pin "1") (pinfunction "1_1") (pintype "passive"))
      (node (ref "VCA2(RIGHT)") (pin "8") (pinfunction "OUT_8") (pintype "output"))
    )
    (net (code "110") (name "Net-(IC9A--IN)") (class "Default")
      (node (ref "C120") (pin "1") (pinfunction "1_1") (pintype "passive"))
      (node (ref "IC9") (pin "2") (pinfunction "-IN_2") (pintype "input"))
      (node (ref "R56") (pin "1") (pinfunction "1_1") (pintype "passive"))
      (node (ref "R57") (pin "2") (pinfunction "2_2") (pintype "passive"))
    )
    (net (code "111") (name "Net-(IC9B--IN)") (class "Default")
      (node (ref "C121") (pin "1") (pinfunction "1_1") (pintype "passive"))
      (node (ref "IC9") (pin "6") (pinfunction "-IN_6") (pintype "input"))
      (node (ref "R54") (pin "1") (pinfunction "1_1") (pintype "passive"))
      (node (ref "R55") (pin "2") (pinfunction "2_2") (pintype "passive"))
    )
    (net (code "112") (name "Net-(IC10-PA9)") (class "Default")
      (node (ref "IC10") (pin "101") (pinfunction "PA9_101") (pintype "bidirectional"))
      (node (ref "R19") (pin "1") (pinfunction "1_1") (pintype "passive"))
    )
    (net (code "113") (name "Net-(IC10-PD12)") (class "Default")
      (node (ref "IC10") (pin "81") (pinfunction "PD12_81") (pintype "bidirectional"))
      (node (ref "R31") (pin "2") (pinfunction "2_2") (pintype "passive"))
    )
    (net (code "114") (name "Net-(IC10-VCAP_1)") (class "Default")
      (node (ref "C71") (pin "1") (pinfunction "1_1") (pintype "passive"))
      (node (ref "IC10") (pin "71") (pinfunction "VCAP_1_71") (pintype "bidirectional"))
    )
    (net (code "115") (name "Net-(IC10-VCAP_2)") (class "Default")
      (node (ref "C72") (pin "1") (pinfunction "1_1") (pintype "passive"))
      (node (ref "IC10") (pin "106") (pinfunction "VCAP_2_106") (pintype "bidirectional"))
    )
    (net (code "116") (name "Net-(IC10-VDDA)") (class "Default")
      (node (ref "C80") (pin "2") (pinfunction "2_2") (pintype "passive"))
      (node (ref "FB6") (pin "2") (pinfunction "2_2") (pintype "bidirectional"))
      (node (ref "IC10") (pin "32") (pinfunction "VREF+_32") (pintype "bidirectional"))
      (node (ref "IC10") (pin "33") (pinfunction "VDDA_33") (pintype "bidirectional"))
    )
    (net (code "117") (name "Net-(IC11-SCLK)") (class "Default")
      (node (ref "IC11") (pin "6") (pinfunction "SCLK_6") (pintype "bidirectional"))
      (node (ref "IC3") (pin "6") (pinfunction "SCLK_6") (pintype "bidirectional"))
      (node (ref "R17") (pin "1") (pinfunction "1_1") (pintype "passive"))
    )
    (net (code "118") (name "Net-(IC11-SDI)") (class "Default")
      (node (ref "IC11") (pin "3") (pinfunction "SDI_3") (pintype "bidirectional"))
      (node (ref "IC3") (pin "3") (pinfunction "SDI_3") (pintype "bidirectional"))
      (node (ref "R4") (pin "1") (pinfunction "1_1") (pintype "passive"))
    )
    (net (code "119") (name "Net-(IC11-VOUTL)") (class "Default")
      (node (ref "IC11") (pin "11") (pinfunction "VOUTL_11") (pintype "bidirectional"))
      (node (ref "R32") (pin "1") (pinfunction "1_1") (pintype "passive"))
    )
    (net (code "120") (name "Net-(IC11-VOUTR)") (class "Default")
      (node (ref "IC11") (pin "14") (pinfunction "VOUTR_14") (pintype "bidirectional"))
      (node (ref "R45") (pin "1") (pinfunction "1_1") (pintype "passive"))
    )
    (net (code "121") (name "Net-(IC11-ZCEN)") (class "Default")
      (node (ref "IC11") (pin "1") (pinfunction "ZCEN_1") (pintype "bidirectional"))
      (node (ref "IC3") (pin "1") (pinfunction "ZCEN_1") (pintype "bidirectional"))
      (node (ref "R30") (pin "1") (pinfunction "1_1") (pintype "passive"))
    )
    (net (code "122") (name "Net-(IC11-~{CS})") (class "Default")
      (node (ref "IC11") (pin "2") (pinfunction "~{CS}_2") (pintype "bidirectional"))
      (node (ref "R28") (pin "1") (pinfunction "1_1") (pintype "passive"))
    )
    (net (code "123") (name "Net-(IC11-~{MUTE})") (class "Default")
      (node (ref "IC11") (pin "8") (pinfunction "~{MUTE}_8") (pintype "bidirectional"))
      (node (ref "IC3") (pin "8") (pinfunction "~{MUTE}_8") (pintype "bidirectional"))
      (node (ref "R3") (pin "1") (pinfunction "1_1") (pintype "passive"))
    )
    (net (code "124") (name "Net-(IC12-Pad3)") (class "Default")
      (node (ref "IC12") (pin "3") (pinfunction "3_3") (pintype "bidirectional"))
      (node (ref "R36") (pin "2") (pinfunction "2_2") (pintype "passive"))
      (node (ref "X1") (pin "2") (pinfunction "2_2") (pintype "bidirectional"))
    )
    (net (code "125") (name "Net-(IC12-Pad6)") (class "Default")
      (node (ref "IC12") (pin "6") (pinfunction "6_6") (pintype "bidirectional"))
      (node (ref "R37") (pin "2") (pinfunction "2_2") (pintype "passive"))
      (node (ref "X1") (pin "3") (pinfunction "3_3") (pintype "bidirectional"))
    )
    (net (code "126") (name "Net-(IC13-VBUS)") (class "Default")
      (node (ref "C94") (pin "2") (pinfunction "2_2") (pintype "passive"))
      (node (ref "FB5") (pin "2") (pinfunction "2_2") (pintype "bidirectional"))
      (node (ref "IC13") (pin "5") (pinfunction "VBUS_5") (pintype "bidirectional"))
      (node (ref "R79") (pin "2") (pinfunction "2_2") (pintype "passive"))
      (node (ref "R80") (pin "2") (pinfunction "2_2") (pintype "passive"))
      (node (ref "R81") (pin "2") (pinfunction "2_2") (pintype "passive"))
      (node (ref "R82") (pin "2") (pinfunction "2_2") (pintype "passive"))
    )
    (net (code "127") (name "Net-(IC16A--IN)") (class "Default")
      (node (ref "IC16") (pin "1") (pinfunction "OUT_1") (pintype "output"))
      (node (ref "IC16") (pin "2") (pinfunction "-IN_2") (pintype "input"))
      (node (ref "U4") (pin "1") (pinfunction "REF_1") (pintype "passive"))
      (node (ref "U6") (pin "2") (pinfunction "IN-_2") (pintype "input"))
    )
    (net (code "128") (name "Net-(IC17-REFCAPA)") (class "Default")
      (node (ref "C116") (pin "1") (pinfunction "1_1") (pintype "passive"))
      (node (ref "IC17") (pin "44") (pinfunction "REFCAPA_44") (pintype "bidirectional"))
      (node (ref "IC17") (pin "45") (pinfunction "REFCAPB_45") (pintype "bidirectional"))
    )
    (net (code "129") (name "Net-(IC17-REFIN{slash}REFOUT)") (class "Default")
      (node (ref "C115") (pin "1") (pinfunction "1_1") (pintype "passive"))
      (node (ref "IC17") (pin "42") (pinfunction "REFIN/REFOUT_42") (pintype "bidirectional"))
    )
    (net (code "130") (name "Net-(IC17-REF_SELECT)") (class "Default")
      (node (ref "IC17") (pin "34") (pinfunction "REF_SELECT_34") (pintype "bidirectional"))
      (node (ref "R96") (pin "2") (pinfunction "2_2") (pintype "passive"))
    )
    (net (code "131") (name "Net-(IC17-REGCAP_1)") (class "Default")
      (node (ref "C117") (pin "1") (pinfunction "1_1") (pintype "passive"))
      (node (ref "IC17") (pin "36") (pinfunction "REGCAP_1_36") (pintype "bidirectional"))
    )
    (net (code "132") (name "Net-(IC17-REGCAP_2)") (class "Default")
      (node (ref "C118") (pin "1") (pinfunction "1_1") (pintype "passive"))
      (node (ref "IC17") (pin "39") (pinfunction "REGCAP_2_39") (pintype "bidirectional"))
    )
    (net (code "133") (name "Net-(IC17-~{PAR}{slash}SER{slash}BYTE_SEL)") (class "Default")
      (node (ref "IC17") (pin "6") (pinfunction "~{PAR}/SER/BYTE_SEL_6") (pintype "bidirectional"))
      (node (ref "R14") (pin "1") (pinfunction "1_1") (pintype "passive"))
    )
    (net (code "134") (name "Net-(IC17-~{STBY})") (class "Default")
      (node (ref "IC17") (pin "7") (pinfunction "~{STBY}_7") (pintype "bidirectional"))
      (node (ref "R35") (pin "1") (pinfunction "1_1") (pintype "passive"))
    )
    (net (code "135") (name "Net-(IN_LEFT-IN+)") (class "Default")
      (node (ref "C17") (pin "2") (pinfunction "2_2") (pintype "passive"))
      (node (ref "IN_LEFT") (pin "3") (pinfunction "IN+_3") (pintype "input"))
      (node (ref "K4") (pin "S2") (pinfunction "S_S2") (pintype "passive"))
    )
    (net (code "136") (name "Net-(IN_LEFT-IN-)") (class "Default")
      (node (ref "C16") (pin "1") (pinfunction "1_1") (pintype "passive"))
      (node (ref "IN_LEFT") (pin "2") (pinfunction "IN-_2") (pintype "input"))
      (node (ref "K4") (pin "S1") (pinfunction "S_S1") (pintype "passive"))
    )
    (net (code "137") (name "Net-(IN_RIGHT-IN+)") (class "Default")
      (node (ref "C10") (pin "2") (pinfunction "2_2") (pintype "passive"))
      (node (ref "IN_RIGHT") (pin "3") (pinfunction "IN+_3") (pintype "input"))
      (node (ref "K1") (pin "S2") (pinfunction "S_S2") (pintype "passive"))
    )
    (net (code "138") (name "Net-(IN_RIGHT-IN-)") (class "Default")
      (node (ref "C9") (pin "1") (pinfunction "1_1") (pintype "passive"))
      (node (ref "IN_RIGHT") (pin "2") (pinfunction "IN-_2") (pintype "input"))
      (node (ref "K1") (pin "S1") (pinfunction "S_S1") (pintype "passive"))
    )
    (net (code "139") (name "Net-(J1-GREEN_K)") (class "Default")
      (node (ref "J1") (pin "11") (pinfunction "GREEN_K_11") (pintype "bidirectional"))
      (node (ref "R84") (pin "2") (pinfunction "2_2") (pintype "passive"))
    )
    (net (code "140") (name "Net-(J1-Pad7)") (class "Default")
      (node (ref "J1") (pin "7") (pinfunction "7_7") (pintype "bidirectional"))
      (node (ref "R29") (pin "2") (pinfunction "2_2") (pintype "passive"))
    )
    (net (code "141") (name "Net-(J1-Pad8)") (class "Default")
      (node (ref "J1") (pin "8") (pinfunction "8_8") (pintype "bidirectional"))
      (node (ref "R88") (pin "2") (pinfunction "2_2") (pintype "passive"))
    )
    (net (code "142") (name "Net-(J1-YELLOW_K)") (class "Default")
      (node (ref "J1") (pin "9") (pinfunction "YELLOW_K_9") (pintype "bidirectional"))
      (node (ref "R83") (pin "2") (pinfunction "2_2") (pintype "passive"))
    )
    (net (code "143") (name "Net-(K1B-O)") (class "Default")
      (node (ref "K1") (pin "Q1") (pinfunction "O_Q1") (pintype "passive"))
      (node (ref "K2") (pin "Q1") (pinfunction "O_Q1") (pintype "passive"))
    )
    (net (code "144") (name "Net-(K1C-O)") (class "Default")
      (node (ref "K1") (pin "Q2") (pinfunction "O_Q2") (pintype "passive"))
      (node (ref "K2") (pin "Q2") (pinfunction "O_Q2") (pintype "passive"))
    )
    (net (code "145") (name "Net-(K2B-S)") (class "Default")
      (node (ref "C110") (pin "2") (pinfunction "2_2") (pintype "passive"))
      (node (ref "K2") (pin "S1") (pinfunction "S_S1") (pintype "passive"))
      (node (ref "OUT_RIGHT") (pin "1") (pinfunction "OUT-_1") (pintype "output"))
    )
    (net (code "146") (name "Net-(K2C-S)") (class "Default")
      (node (ref "C111") (pin "2") (pinfunction "2_2") (pintype "passive"))
      (node (ref "K2") (pin "S2") (pinfunction "S_S2") (pintype "passive"))
      (node (ref "OUT_RIGHT") (pin "8") (pinfunction "OUT+_8") (pintype "output"))
    )
    (net (code "147") (name "Net-(K3B-O)") (class "Default")
      (node (ref "K3") (pin "Q1") (pinfunction "O_Q1") (pintype "passive"))
      (node (ref "K4") (pin "Q1") (pinfunction "O_Q1") (pintype "passive"))
    )
    (net (code "148") (name "Net-(K3B-S)") (class "Default")
      (node (ref "C113") (pin "2") (pinfunction "2_2") (pintype "passive"))
      (node (ref "K3") (pin "S1") (pinfunction "S_S1") (pintype "passive"))
      (node (ref "OUT_LEFT") (pin "1") (pinfunction "OUT-_1") (pintype "output"))
    )
    (net (code "149") (name "Net-(K3C-O)") (class "Default")
      (node (ref "K3") (pin "Q2") (pinfunction "O_Q2") (pintype "passive"))
      (node (ref "K4") (pin "Q2") (pinfunction "O_Q2") (pintype "passive"))
    )
    (net (code "150") (name "Net-(K3C-S)") (class "Default")
      (node (ref "C112") (pin "2") (pinfunction "2_2") (pintype "passive"))
      (node (ref "K3") (pin "S2") (pinfunction "S_S2") (pintype "passive"))
      (node (ref "OUT_LEFT") (pin "8") (pinfunction "OUT+_8") (pintype "output"))
    )
    (net (code "151") (name "Net-(K6B-P)") (class "Default")
      (node (ref "K6") (pin "P1") (pinfunction "P_P1") (pintype "passive"))
      (node (ref "K7") (pin "S1") (pinfunction "S_S1") (pintype "passive"))
      (node (ref "K8") (pin "Q1") (pinfunction "O_Q1") (pintype "passive"))
    )
    (net (code "152") (name "Net-(K6B-S)") (class "Default")
      (node (ref "K6") (pin "S1") (pinfunction "S_S1") (pintype "passive"))
      (node (ref "U7") (pin "5") (pinfunction "SEN_5") (pintype "output"))
      (node (ref "U7") (pin "6") (pinfunction "OUT_6") (pintype "output"))
    )
    (net (code "153") (name "Net-(K6C-P)") (class "Default")
      (node (ref "K6") (pin "P2") (pinfunction "P_P2") (pintype "passive"))
      (node (ref "K7") (pin "Q1") (pinfunction "O_Q1") (pintype "passive"))
      (node (ref "K8") (pin "S1") (pinfunction "S_S1") (pintype "passive"))
    )
    (net (code "154") (name "Net-(K6C-S)") (class "Default")
      (node (ref "K6") (pin "S2") (pinfunction "S_S2") (pintype "passive"))
      (node (ref "U8") (pin "5") (pinfunction "SEN_5") (pintype "output"))
      (node (ref "U8") (pin "6") (pinfunction "OUT_6") (pintype "output"))
    )
    (net (code "155") (name "Net-(LD1--)") (class "Default")
      (node (ref "LD1") (pin "1") (pinfunction "-_1") (pintype "passive"))
      (node (ref "R5") (pin "2") (pinfunction "2_2") (pintype "passive"))
    )
    (net (code "156") (name "Net-(LD2--)") (class "Default")
      (node (ref "LD2") (pin "1") (pinfunction "-_1") (pintype "passive"))
      (node (ref "R6") (pin "2") (pinfunction "2_2") (pintype "passive"))
    )
    (net (code "157") (name "Net-(LD3--)") (class "Default")
      (node (ref "LD3") (pin "1") (pinfunction "-_1") (pintype "passive"))
      (node (ref "R13") (pin "2") (pinfunction "2_2") (pintype "passive"))
    )
    (net (code "158") (name "Net-(LED1--)") (class "Default")
      (node (ref "LED1") (pin "1") (pinfunction "-_1") (pintype "passive"))
      (node (ref "R7") (pin "2") (pinfunction "2_2") (pintype "passive"))
    )
    (net (code "159") (name "Net-(LED2--)") (class "Default")
      (node (ref "LED2") (pin "1") (pinfunction "-_1") (pintype "passive"))
      (node (ref "R33") (pin "2") (pinfunction "2_2") (pintype "passive"))
    )
    (net (code "160") (name "Net-(LED3--)") (class "Default")
      (node (ref "LED3") (pin "1") (pinfunction "-_1") (pintype "passive"))
      (node (ref "R8") (pin "2") (pinfunction "2_2") (pintype "passive"))
    )
    (net (code "161") (name "Net-(LED4--)") (class "Default")
      (node (ref "LED4") (pin "1") (pinfunction "-_1") (pintype "passive"))
      (node (ref "R34") (pin "2") (pinfunction "2_2") (pintype "passive"))
    )
    (net (code "162") (name "Net-(LED5--)") (class "Default")
      (node (ref "LED5") (pin "1") (pinfunction "-_1") (pintype "passive"))
      (node (ref "R9") (pin "2") (pinfunction "2_2") (pintype "passive"))
    )
    (net (code "163") (name "Net-(LED6--)") (class "Default")
      (node (ref "LED6") (pin "1") (pinfunction "-_1") (pintype "passive"))
      (node (ref "R10") (pin "2") (pinfunction "2_2") (pintype "passive"))
    )
    (net (code "164") (name "Net-(LED7--)") (class "Default")
      (node (ref "LED7") (pin "1") (pinfunction "-_1") (pintype "passive"))
      (node (ref "R11") (pin "2") (pinfunction "2_2") (pintype "passive"))
    )
    (net (code "165") (name "Net-(LED8--)") (class "Default")
      (node (ref "LED8") (pin "1") (pinfunction "-_1") (pintype "passive"))
      (node (ref "R12") (pin "2") (pinfunction "2_2") (pintype "passive"))
    )
    (net (code "166") (name "Net-(OUT_LEFT-SEN+)") (class "Default")
      (node (ref "C112") (pin "1") (pinfunction "1_1") (pintype "passive"))
      (node (ref "OUT_LEFT") (pin "7") (pinfunction "SEN+_7") (pintype "output"))
    )
    (net (code "167") (name "Net-(OUT_LEFT-SEN-)") (class "Default")
      (node (ref "C113") (pin "1") (pinfunction "1_1") (pintype "passive"))
      (node (ref "OUT_LEFT") (pin "2") (pinfunction "SEN-_2") (pintype "passive"))
    )
    (net (code "168") (name "Net-(OUT_RIGHT-SEN+)") (class "Default")
      (node (ref "C111") (pin "1") (pinfunction "1_1") (pintype "passive"))
      (node (ref "OUT_RIGHT") (pin "7") (pinfunction "SEN+_7") (pintype "output"))
    )
    (net (code "169") (name "Net-(OUT_RIGHT-SEN-)") (class "Default")
      (node (ref "C110") (pin "1") (pinfunction "1_1") (pintype "passive"))
      (node (ref "OUT_RIGHT") (pin "2") (pinfunction "SEN-_2") (pintype "passive"))
    )
    (net (code "170") (name "Net-(T1-NC_4)") (class "Default")
      (node (ref "R89") (pin "2") (pinfunction "2_2") (pintype "passive"))
      (node (ref "T1") (pin "12") (pinfunction "NC_4_12") (pintype "bidirectional"))
    )
    (net (code "171") (name "Net-(T1-NC_6)") (class "Default")
      (node (ref "R90") (pin "2") (pinfunction "2_2") (pintype "passive"))
      (node (ref "T1") (pin "15") (pinfunction "NC_6_15") (pintype "bidirectional"))
    )
    (net (code "172") (name "Net-(T1-RX+)") (class "Default")
      (node (ref "J1") (pin "3") (pinfunction "3_3") (pintype "bidirectional"))
      (node (ref "T1") (pin "11") (pinfunction "RX+_11") (pintype "bidirectional"))
    )
    (net (code "173") (name "Net-(T1-RX-)") (class "Default")
      (node (ref "J1") (pin "6") (pinfunction "6_6") (pintype "bidirectional"))
      (node (ref "T1") (pin "9") (pinfunction "RX-_9") (pintype "bidirectional"))
    )
    (net (code "174") (name "Net-(T1-TX+)") (class "Default")
      (node (ref "J1") (pin "1") (pinfunction "1_1") (pintype "bidirectional"))
      (node (ref "T1") (pin "16") (pinfunction "TX+_16") (pintype "bidirectional"))
    )
    (net (code "175") (name "Net-(T1-TX-)") (class "Default")
      (node (ref "J1") (pin "2") (pinfunction "2_2") (pintype "bidirectional"))
      (node (ref "T1") (pin "14") (pinfunction "TX-_14") (pintype "bidirectional"))
    )
    (net (code "176") (name "Net-(VCA1(LEFT)-IN)") (class "Default")
      (node (ref "R52") (pin "2") (pinfunction "2_2") (pintype "passive"))
      (node (ref "VCA1(LEFT)") (pin "1") (pinfunction "IN_1") (pintype "input"))
    )
    (net (code "177") (name "Net-(VCA1(LEFT)-V-)") (class "Default")
      (node (ref "C61") (pin "1") (pinfunction "1_1") (pintype "passive"))
      (node (ref "R50") (pin "2") (pinfunction "2_2") (pintype "passive"))
      (node (ref "VCA1(LEFT)") (pin "5") (pinfunction "V-_5") (pintype "power_in"))
    )
    (net (code "178") (name "Net-(VCA2(RIGHT)-IN)") (class "Default")
      (node (ref "R53") (pin "2") (pinfunction "2_2") (pintype "passive"))
      (node (ref "VCA2(RIGHT)") (pin "1") (pinfunction "IN_1") (pintype "input"))
    )
    (net (code "179") (name "Net-(VCA2(RIGHT)-V-)") (class "Default")
      (node (ref "C58") (pin "1") (pinfunction "1_1") (pintype "passive"))
      (node (ref "R51") (pin "2") (pinfunction "2_2") (pintype "passive"))
      (node (ref "VCA2(RIGHT)") (pin "5") (pinfunction "V-_5") (pintype "power_in"))
    )
    (net (code "180") (name "OS0") (class "Default")
      (node (ref "IC10") (pin "98") (pinfunction "PC8_98") (pintype "bidirectional"))
      (node (ref "IC17") (pin "3") (pinfunction "OS_0_3") (pintype "bidirectional"))
    )
    (net (code "181") (name "OS1") (class "Default")
      (node (ref "IC10") (pin "99") (pinfunction "PC9_99") (pintype "bidirectional"))
      (node (ref "IC17") (pin "4") (pinfunction "OS_1_4") (pintype "bidirectional"))
    )
    (net (code "182") (name "OS2") (class "Default")
      (node (ref "IC10") (pin "111") (pinfunction "PC10_111") (pintype "bidirectional"))
      (node (ref "IC17") (pin "5") (pinfunction "OS_2_5") (pintype "bidirectional"))
    )
    (net (code "183") (name "OUT1_DRIVER") (class "Default")
      (node (ref "K1") (pin "2") (pinfunction "2_2") (pintype "passive"))
      (node (ref "K2") (pin "2") (pinfunction "2_2") (pintype "passive"))
      (node (ref "R33") (pin "1") (pinfunction "1_1") (pintype "passive"))
      (node (ref "R7") (pin "1") (pinfunction "1_1") (pintype "passive"))
      (node (ref "U12") (pin "16") (pinfunction "OUT1_16") (pintype "bidirectional"))
    )
    (net (code "184") (name "OUT2_DRIVER") (class "Default")
      (node (ref "K3") (pin "2") (pinfunction "2_2") (pintype "passive"))
      (node (ref "K4") (pin "2") (pinfunction "2_2") (pintype "passive"))
      (node (ref "R34") (pin "1") (pinfunction "1_1") (pintype "passive"))
      (node (ref "R8") (pin "1") (pinfunction "1_1") (pintype "passive"))
      (node (ref "U12") (pin "15") (pinfunction "OUT2_15") (pintype "bidirectional"))
    )
    (net (code "185") (name "OUT3_DRIVER") (class "Default")
      (node (ref "K5") (pin "2") (pinfunction "2_2") (pintype "passive"))
      (node (ref "R9") (pin "1") (pinfunction "1_1") (pintype "passive"))
      (node (ref "U12") (pin "14") (pinfunction "OUT3_14") (pintype "bidirectional"))
    )
    (net (code "186") (name "OUT4_DRIVER") (class "Default")
      (node (ref "K6") (pin "2") (pinfunction "2_2") (pintype "passive"))
      (node (ref "R10") (pin "1") (pinfunction "1_1") (pintype "passive"))
      (node (ref "U12") (pin "13") (pinfunction "OUT4_13") (pintype "bidirectional"))
    )
    (net (code "187") (name "OUT5_DRIVER") (class "Default")
      (node (ref "K7") (pin "2") (pinfunction "2_2") (pintype "passive"))
      (node (ref "R11") (pin "1") (pinfunction "1_1") (pintype "passive"))
      (node (ref "U12") (pin "12") (pinfunction "OUT5_12") (pintype "bidirectional"))
    )
    (net (code "188") (name "OUT6_DRIVER") (class "Default")
      (node (ref "K8") (pin "2") (pinfunction "2_2") (pintype "passive"))
      (node (ref "R12") (pin "1") (pinfunction "1_1") (pintype "passive"))
      (node (ref "U12") (pin "11") (pinfunction "OUT6_11") (pintype "bidirectional"))
    )
    (net (code "189") (name "OUT_L{slash}M") (class "Default")
      (node (ref "K8") (pin "P1") (pinfunction "P_P1") (pintype "passive"))
      (node (ref "OUT_LEFT") (pin "4") (pinfunction "IN_4") (pintype "input"))
    )
    (net (code "190") (name "OUT_R{slash}S") (class "Default")
      (node (ref "K7") (pin "P1") (pinfunction "P_P1") (pintype "passive"))
      (node (ref "OUT_RIGHT") (pin "4") (pinfunction "IN_4") (pintype "input"))
    )
    (net (code "191") (name "PB12") (class "Default")
      (node (ref "IC10") (pin "73") (pinfunction "PB12_73") (pintype "bidirectional"))
      (node (ref "TP05") (pin "P$1") (pinfunction "TP_P$1") (pintype "input"))
    )
    (net (code "192") (name "POSITIVE_IN(L{slash}M)") (class "Default")
      (node (ref "IN2(L/M)") (pin "2") (pinfunction "2_2") (pintype "bidirectional"))
      (node (ref "K4") (pin "P2") (pinfunction "P_P2") (pintype "passive"))
    )
    (net (code "193") (name "POSITIVE_IN(R{slash}S)") (class "Default")
      (node (ref "IN1(R/S)") (pin "2") (pinfunction "2_2") (pintype "bidirectional"))
      (node (ref "K1") (pin "P2") (pinfunction "P_P2") (pintype "passive"))
    )
    (net (code "194") (name "R") (class "Default")
      (node (ref "IC16") (pin "3") (pinfunction "+IN_3") (pintype "input"))
      (node (ref "IC3") (pin "16") (pinfunction "VINR_16") (pintype "bidirectional"))
      (node (ref "IN_RIGHT") (pin "5") (pinfunction "SEN_5") (pintype "output"))
      (node (ref "IN_RIGHT") (pin "6") (pinfunction "OUT_6") (pintype "output"))
      (node (ref "K5") (pin "Q2") (pinfunction "O_Q2") (pintype "passive"))
    )
    (net (code "195") (name "RANGE") (class "Default")
      (node (ref "IC10") (pin "112") (pinfunction "PC11_112") (pintype "bidirectional"))
      (node (ref "IC17") (pin "8") (pinfunction "RANGE_8") (pintype "bidirectional"))
    )
    (net (code "196") (name "RD") (class "Default")
      (node (ref "IC10") (pin "116") (pinfunction "PD2_116") (pintype "bidirectional"))
      (node (ref "IC17") (pin "12") (pinfunction "~{RD}/SCLK_12") (pintype "bidirectional"))
    )
    (net (code "197") (name "RD_N") (class "Default")
      (node (ref "IC13") (pin "6") (pinfunction "I/O4_6") (pintype "bidirectional"))
      (node (ref "IC6") (pin "22") (pinfunction "RXN_22") (pintype "bidirectional"))
      (node (ref "R82") (pin "1") (pinfunction "1_1") (pintype "passive"))
      (node (ref "T1") (pin "8") (pinfunction "RD-_8") (pintype "bidirectional"))
    )
    (net (code "198") (name "RD_P") (class "Default")
      (node (ref "IC13") (pin "1") (pinfunction "I/O1_1") (pintype "bidirectional"))
      (node (ref "IC6") (pin "23") (pinfunction "RXP_23") (pintype "bidirectional"))
      (node (ref "R81") (pin "1") (pinfunction "1_1") (pintype "passive"))
      (node (ref "T1") (pin "6") (pinfunction "RD+_6") (pintype "bidirectional"))
    )
    (net (code "199") (name "RELAIS1") (class "Default")
      (node (ref "IC10") (pin "57") (pinfunction "PG1_57") (pintype "bidirectional"))
      (node (ref "U12") (pin "1") (pinfunction "IN1_1") (pintype "bidirectional"))
    )
    (net (code "200") (name "RELAIS2") (class "Default")
      (node (ref "IC10") (pin "56") (pinfunction "PG0_56") (pintype "bidirectional"))
      (node (ref "U12") (pin "2") (pinfunction "IN2_2") (pintype "bidirectional"))
    )
    (net (code "201") (name "RELAIS3") (class "Default")
      (node (ref "IC10") (pin "132") (pinfunction "PG15_132") (pintype "bidirectional"))
      (node (ref "U12") (pin "3") (pinfunction "IN3_3") (pintype "bidirectional"))
    )
    (net (code "202") (name "RELAIS4") (class "Default")
      (node (ref "IC10") (pin "125") (pinfunction "PG10_125") (pintype "bidirectional"))
      (node (ref "U12") (pin "4") (pinfunction "IN4_4") (pintype "bidirectional"))
    )
    (net (code "203") (name "RELAIS5") (class "Default")
      (node (ref "IC10") (pin "127") (pinfunction "PG12_127") (pintype "bidirectional"))
      (node (ref "U12") (pin "5") (pinfunction "IN5_5") (pintype "bidirectional"))
    )
    (net (code "204") (name "RELAIS6") (class "Default")
      (node (ref "IC10") (pin "124") (pinfunction "PG9_124") (pintype "bidirectional"))
      (node (ref "U12") (pin "6") (pinfunction "IN6_6") (pintype "bidirectional"))
    )
    (net (code "205") (name "RELAIS_TO_STAR_GND") (class "Default")
      (node (ref "R104") (pin "1") (pinfunction "1_1") (pintype "passive"))
      (node (ref "U12") (pin "8") (pinfunction "GND_8") (pintype "bidirectional"))
    )
    (net (code "206") (name "RESET") (class "Default")
      (node (ref "IC10") (pin "87") (pinfunction "PG2_87") (pintype "bidirectional"))
      (node (ref "IC17") (pin "11") (pinfunction "RESET_11") (pintype "bidirectional"))
    )
    (net (code "207") (name "RMII_CRS_DV") (class "Default")
      (node (ref "IC10") (pin "43") (pinfunction "PA7_43") (pintype "bidirectional"))
      (node (ref "R26") (pin "1") (pinfunction "1_1") (pintype "passive"))
    )
    (net (code "208") (name "RMII_MDC") (class "Default")
      (node (ref "IC10") (pin "27") (pinfunction "PC1_27") (pintype "bidirectional"))
      (node (ref "IC6") (pin "13") (pinfunction "MDC_13") (pintype "bidirectional"))
    )
    (net (code "209") (name "RMII_MDIO") (class "Default")
      (node (ref "IC10") (pin "36") (pinfunction "PA2_36") (pintype "bidirectional"))
      (node (ref "IC6") (pin "12") (pinfunction "MDIO_12") (pintype "bidirectional"))
      (node (ref "R22") (pin "2") (pinfunction "2_2") (pintype "passive"))
    )
    (net (code "210") (name "RMII_REF_CLK") (class "Default")
      (node (ref "IC10") (pin "35") (pinfunction "PA1_35") (pintype "bidirectional"))
      (node (ref "IC6") (pin "14") (pinfunction "NINT/REFCLKO_14") (pintype "output"))
      (node (ref "R23") (pin "1") (pinfunction "1_1") (pintype "passive"))
    )
    (net (code "211") (name "RMII_RXD0") (class "Default")
      (node (ref "IC10") (pin "44") (pinfunction "PC4_44") (pintype "bidirectional"))
      (node (ref "R25") (pin "1") (pinfunction "1_1") (pintype "passive"))
    )
    (net (code "212") (name "RMII_RXD1") (class "Default")
      (node (ref "IC10") (pin "45") (pinfunction "PC5_45") (pintype "bidirectional"))
      (node (ref "R24") (pin "1") (pinfunction "1_1") (pintype "passive"))
    )
    (net (code "213") (name "RMII_TXD0") (class "Default")
      (node (ref "IC10") (pin "128") (pinfunction "PG13_128") (pintype "bidirectional"))
      (node (ref "IC6") (pin "17") (pinfunction "TXD0_17") (pintype "bidirectional"))
    )
    (net (code "214") (name "RMII_TXD1") (class "Default")
      (node (ref "IC10") (pin "74") (pinfunction "PB13_74") (pintype "bidirectional"))
      (node (ref "IC6") (pin "18") (pinfunction "TXD1_18") (pintype "bidirectional"))
    )
    (net (code "215") (name "RMII_TX_EN") (class "Default")
      (node (ref "IC10") (pin "126") (pinfunction "PG11_126") (pintype "bidirectional"))
      (node (ref "IC6") (pin "16") (pinfunction "TXEN_16") (pintype "bidirectional"))
    )
    (net (code "216") (name "R{slash}S_IN(VCA2_IN)") (class "Default")
      (node (ref "C67") (pin "1") (pinfunction "1_1") (pintype "passive"))
      (node (ref "IC17") (pin "51") (pinfunction "V2_51") (pintype "bidirectional"))
      (node (ref "K5") (pin "P2") (pinfunction "P_P2") (pintype "passive"))
    )
    (net (code "217") (name "R{slash}S_OUT(OUT_STAGE_RIGHT)") (class "Default")
      (node (ref "IC1") (pin "5") (pinfunction "+IN_5") (pintype "input"))
      (node (ref "IC5") (pin "7") (pinfunction "OUT_7") (pintype "output"))
      (node (ref "K6") (pin "Q2") (pinfunction "O_Q2") (pintype "passive"))
      (node (ref "R42") (pin "2") (pinfunction "2_2") (pintype "passive"))
    )
    (net (code "218") (name "R{slash}S_OUT(OUT_STAGE_RIGHT)_BEFORE") (class "Default")
      (node (ref "IC17") (pin "61") (pinfunction "V6_61") (pintype "bidirectional"))
    )
    (net (code "219") (name "R{slash}S_OUT(VCA2_OUT)") (class "Default")
      (node (ref "C56") (pin "2") (pinfunction "2_2") (pintype "passive"))
      (node (ref "IC17") (pin "57") (pinfunction "V4_57") (pintype "bidirectional"))
      (node (ref "IC3") (pin "9") (pinfunction "VINL_9") (pintype "bidirectional"))
      (node (ref "IC8") (pin "7") (pinfunction "OUT_7") (pintype "output"))
      (node (ref "R49") (pin "2") (pinfunction "2_2") (pintype "passive"))
    )
    (net (code "220") (name "S") (class "Default")
      (node (ref "K5") (pin "S2") (pinfunction "S_S2") (pintype "passive"))
      (node (ref "U6") (pin "5") (pinfunction "SEN_5") (pintype "output"))
      (node (ref "U6") (pin "6") (pinfunction "OUT_6") (pintype "output"))
    )
    (net (code "221") (name "SCLK_DAC") (class "Default")
      (node (ref "IC10") (pin "69") (pinfunction "PB10_69") (pintype "bidirectional"))
      (node (ref "R17") (pin "2") (pinfunction "2_2") (pintype "passive"))
      (node (ref "R92") (pin "2") (pinfunction "2_2") (pintype "passive"))
      (node (ref "TP03") (pin "P$1") (pinfunction "TP_P$1") (pintype "input"))
    )
    (net (code "222") (name "SWCLK") (class "Default")
      (node (ref "IC10") (pin "109") (pinfunction "PA14_109") (pintype "bidirectional"))
      (node (ref "PROG.") (pin "1") (pinfunction "1_1") (pintype "bidirectional"))
    )
    (net (code "223") (name "SWDIO") (class "Default")
      (node (ref "IC10") (pin "105") (pinfunction "PA13_105") (pintype "bidirectional"))
      (node (ref "PROG.") (pin "3") (pinfunction "3_3") (pintype "bidirectional"))
    )
    (net (code "224") (name "SYM1") (class "Default")
      (node (ref "R38") (pin "1") (pinfunction "1_1") (pintype "passive"))
      (node (ref "R40") (pin "2") (pinfunction "2_2") (pintype "passive"))
      (node (ref "VCA1(LEFT)") (pin "4") (pinfunction "SYM_4") (pintype "passive"))
    )
    (net (code "225") (name "SYM2") (class "Default")
      (node (ref "R41") (pin "1") (pinfunction "1_1") (pintype "passive"))
      (node (ref "R43") (pin "2") (pinfunction "2_2") (pintype "passive"))
      (node (ref "VCA2(RIGHT)") (pin "4") (pinfunction "SYM_4") (pintype "passive"))
    )
    (net (code "226") (name "TD_N") (class "Default")
      (node (ref "IC13") (pin "4") (pinfunction "I/O3_4") (pintype "bidirectional"))
      (node (ref "IC6") (pin "20") (pinfunction "TXN_20") (pintype "bidirectional"))
      (node (ref "R80") (pin "1") (pinfunction "1_1") (pintype "passive"))
      (node (ref "T1") (pin "3") (pinfunction "TD-_3") (pintype "bidirectional"))
    )
    (net (code "227") (name "TD_P") (class "Default")
      (node (ref "IC13") (pin "3") (pinfunction "I/O2_3") (pintype "bidirectional"))
      (node (ref "IC6") (pin "21") (pinfunction "TXP_21") (pintype "bidirectional"))
      (node (ref "R79") (pin "1") (pinfunction "1_1") (pintype "passive"))
      (node (ref "T1") (pin "1") (pinfunction "TD+_1") (pintype "bidirectional"))
    )
    (net (code "228") (name "USART1_RX") (class "Default")
      (node (ref "IC10") (pin "76") (pinfunction "PB15_76") (pintype "bidirectional"))
    )
    (net (code "229") (name "USART1_TX") (class "Default")
      (node (ref "IC10") (pin "136") (pinfunction "PB6_136") (pintype "bidirectional"))
    )
    (net (code "230") (name "USART3_RX") (class "Default")
      (node (ref "IC10") (pin "77") (pinfunction "PD8_77") (pintype "bidirectional"))
      (node (ref "TP06") (pin "P$1") (pinfunction "TP_P$1") (pintype "input"))
    )
    (net (code "231") (name "USART3_TX") (class "Default")
      (node (ref "IC10") (pin "78") (pinfunction "PD9_78") (pintype "bidirectional"))
      (node (ref "TP07") (pin "P$1") (pinfunction "TP_P$1") (pintype "input"))
    )
    (net (code "232") (name "USART6_RX") (class "Default")
      (node (ref "DISPLAY1") (pin "2") (pinfunction "2_2") (pintype "bidirectional"))
      (node (ref "IC10") (pin "97") (pinfunction "PC7_97") (pintype "bidirectional"))
    )
    (net (code "233") (name "USART6_TX") (class "Default")
      (node (ref "DISPLAY1") (pin "1") (pinfunction "1_1") (pintype "bidirectional"))
      (node (ref "IC10") (pin "96") (pinfunction "PC6_96") (pintype "bidirectional"))
    )
    (net (code "234") (name "USB_ID") (class "Default")
      (node (ref "IC10") (pin "102") (pinfunction "PA10_102") (pintype "bidirectional"))
    )
    (net (code "235") (name "USB_N") (class "Default")
      (node (ref "IC10") (pin "103") (pinfunction "PA11_103") (pintype "bidirectional"))
      (node (ref "R36") (pin "1") (pinfunction "1_1") (pintype "passive"))
    )
    (net (code "236") (name "USB_OVERCURRENT") (class "Default")
      (node (ref "IC10") (pin "92") (pinfunction "PG7_92") (pintype "bidirectional"))
    )
    (net (code "237") (name "USB_P") (class "Default")
      (node (ref "IC10") (pin "104") (pinfunction "PA12_104") (pintype "bidirectional"))
      (node (ref "R37") (pin "1") (pinfunction "1_1") (pintype "passive"))
    )
    (net (code "238") (name "USB_POWERSWITCHON") (class "Default")
      (node (ref "IC10") (pin "91") (pinfunction "PG6_91") (pintype "bidirectional"))
    )
    (net (code "239") (name "USB_SOF") (class "Default")
      (node (ref "IC10") (pin "100") (pinfunction "PA8_100") (pintype "bidirectional"))
    )
    (net (code "240") (name "USB_VBUS") (class "Default")
      (node (ref "IC12") (pin "1") (pinfunction "1_1") (pintype "bidirectional"))
      (node (ref "R19") (pin "2") (pinfunction "2_2") (pintype "passive"))
      (node (ref "X1") (pin "1") (pinfunction "1_1") (pintype "bidirectional"))
    )
    (net (code "241") (name "V+") (class "Default")
      (node (ref "ANALOG_VOLT_IN") (pin "1") (pinfunction "1_1") (pintype "bidirectional"))
      (node (ref "C103") (pin "1") (pinfunction "1_1") (pintype "passive"))
      (node (ref "C104") (pin "1") (pinfunction "1_1") (pintype "passive"))
      (node (ref "C12") (pin "1") (pinfunction "1_1") (pintype "passive"))
      (node (ref "C19") (pin "1") (pinfunction "1_1") (pintype "passive"))
      (node (ref "C21") (pin "1") (pinfunction "1_1") (pintype "passive"))
      (node (ref "C22") (pin "1") (pinfunction "1_1") (pintype "passive"))
      (node (ref "C25") (pin "1") (pinfunction "1_1") (pintype "passive"))
      (node (ref "C27") (pin "1") (pinfunction "1_1") (pintype "passive"))
      (node (ref "C29") (pin "1") (pinfunction "1_1") (pintype "passive"))
      (node (ref "C3") (pin "1") (pinfunction "1_1") (pintype "passive"))
      (node (ref "C37") (pin "1") (pinfunction "1_1") (pintype "passive"))
      (node (ref "C38") (pin "1") (pinfunction "1_1") (pintype "passive"))
      (node (ref "C4") (pin "1") (pinfunction "1_1") (pintype "passive"))
      (node (ref "C48") (pin "1") (pinfunction "1_1") (pintype "passive"))
      (node (ref "C50") (pin "1") (pinfunction "1_1") (pintype "passive"))
      (node (ref "C54") (pin "1") (pinfunction "1_1") (pintype "passive"))
      (node (ref "C6") (pin "1") (pinfunction "1_1") (pintype "passive"))
      (node (ref "C60") (pin "1") (pinfunction "1_1") (pintype "passive"))
      (node (ref "C62") (pin "1") (pinfunction "1_1") (pintype "passive"))
      (node (ref "C63") (pin "1") (pinfunction "1_1") (pintype "passive"))
      (node (ref "C8") (pin "1") (pinfunction "1_1") (pintype "passive"))
      (node (ref "D1") (pin "1") (pinfunction "K_1") (pintype "output"))
      (node (ref "D2") (pin "1") (pinfunction "K_1") (pintype "output"))
      (node (ref "D5") (pin "1") (pinfunction "K_1") (pintype "output"))
      (node (ref "D8") (pin "1") (pinfunction "K_1") (pintype "output"))
      (node (ref "IC1") (pin "8") (pinfunction "V+_8") (pintype "power_in"))
      (node (ref "IC11") (pin "12") (pinfunction "VA+_12") (pintype "bidirectional"))
      (node (ref "IC16") (pin "8") (pinfunction "V+_8") (pintype "power_in"))
      (node (ref "IC3") (pin "12") (pinfunction "VA+_12") (pintype "bidirectional"))
      (node (ref "IC4") (pin "8") (pinfunction "V+_8") (pintype "power_in"))
      (node (ref "IC5") (pin "8") (pinfunction "V+_8") (pintype "power_in"))
      (node (ref "IC8") (pin "8") (pinfunction "V+_8") (pintype "power_in"))
      (node (ref "IC9") (pin "8") (pinfunction "V+_8") (pintype "power_in"))
      (node (ref "IN_LEFT") (pin "7") (pinfunction "V+_7") (pintype "power_in"))
      (node (ref "IN_RIGHT") (pin "7") (pinfunction "V+_7") (pintype "power_in"))
      (node (ref "K1") (pin "1") (pinfunction "1_1") (pintype "passive"))
      (node (ref "K2") (pin "1") (pinfunction "1_1") (pintype "passive"))
      (node (ref "K3") (pin "1") (pinfunction "1_1") (pintype "passive"))
      (node (ref "K4") (pin "1") (pinfunction "1_1") (pintype "passive"))
      (node (ref "K5") (pin "1") (pinfunction "1_1") (pintype "passive"))
      (node (ref "K6") (pin "1") (pinfunction "1_1") (pintype "passive"))
      (node (ref "K7") (pin "1") (pinfunction "1_1") (pintype "passive"))
      (node (ref "K8") (pin "1") (pinfunction "1_1") (pintype "passive"))
      (node (ref "LED1") (pin "2") (pinfunction "+_2") (pintype "passive"))
      (node (ref "LED2") (pin "2") (pinfunction "+_2") (pintype "passive"))
      (node (ref "LED3") (pin "2") (pinfunction "+_2") (pintype "passive"))
      (node (ref "LED4") (pin "2") (pinfunction "+_2") (pintype "passive"))
      (node (ref "LED5") (pin "2") (pinfunction "+_2") (pintype "passive"))
      (node (ref "LED6") (pin "2") (pinfunction "+_2") (pintype "passive"))
      (node (ref "LED7") (pin "2") (pinfunction "+_2") (pintype "passive"))
      (node (ref "LED8") (pin "2") (pinfunction "+_2") (pintype "passive"))
      (node (ref "OUT_LEFT") (pin "6") (pinfunction "V+_6") (pintype "power_in"))
      (node (ref "OUT_RIGHT") (pin "6") (pinfunction "V+_6") (pintype "power_in"))
      (node (ref "R98") (pin "2") (pinfunction "2_2") (pintype "passive"))
      (node (ref "U1") (pin "1") (pinfunction "VI_1") (pintype "input"))
      (node (ref "U12") (pin "9") (pinfunction "COM_9") (pintype "bidirectional"))
      (node (ref "U4") (pin "7") (pinfunction "V+_7") (pintype "power_in"))
      (node (ref "U6") (pin "7") (pinfunction "V+_7") (pintype "power_in"))
      (node (ref "U7") (pin "7") (pinfunction "V+_7") (pintype "power_in"))
      (node (ref "U8") (pin "7") (pinfunction "V+_7") (pintype "power_in"))
      (node (ref "VCA1(LEFT)") (pin "7") (pinfunction "V+_7") (pintype "power_in"))
      (node (ref "VCA2(RIGHT)") (pin "7") (pinfunction "V+_7") (pintype "power_in"))
    )
    (net (code "242") (name "V-") (class "Default")
      (node (ref "ANALOG_VOLT_IN") (pin "2") (pinfunction "2_2") (pintype "bidirectional"))
      (node (ref "C1") (pin "1") (pinfunction "1_1") (pintype "passive"))
      (node (ref "C11") (pin "1") (pinfunction "1_1") (pintype "passive"))
      (node (ref "C13") (pin "1") (pinfunction "1_1") (pintype "passive"))
      (node (ref "C2") (pin "1") (pinfunction "1_1") (pintype "passive"))
      (node (ref "C20") (pin "1") (pinfunction "1_1") (pintype "passive"))
      (node (ref "C23") (pin "1") (pinfunction "1_1") (pintype "passive"))
      (node (ref "C26") (pin "1") (pinfunction "1_1") (pintype "passive"))
      (node (ref "C28") (pin "1") (pinfunction "1_1") (pintype "passive"))
      (node (ref "C30") (pin "1") (pinfunction "1_1") (pintype "passive"))
      (node (ref "C31") (pin "1") (pinfunction "1_1") (pintype "passive"))
      (node (ref "C43") (pin "1") (pinfunction "1_1") (pintype "passive"))
      (node (ref "C45") (pin "1") (pinfunction "1_1") (pintype "passive"))
      (node (ref "C49") (pin "1") (pinfunction "1_1") (pintype "passive"))
      (node (ref "C5") (pin "1") (pinfunction "1_1") (pintype "passive"))
      (node (ref "C53") (pin "1") (pinfunction "1_1") (pintype "passive"))
      (node (ref "C57") (pin "1") (pinfunction "1_1") (pintype "passive"))
      (node (ref "C68") (pin "1") (pinfunction "1_1") (pintype "passive"))
      (node (ref "C7") (pin "1") (pinfunction "1_1") (pintype "passive"))
      (node (ref "D10") (pin "2") (pinfunction "A_2") (pintype "input"))
      (node (ref "D3") (pin "2") (pinfunction "A_2") (pintype "input"))
      (node (ref "D4") (pin "2") (pinfunction "A_2") (pintype "input"))
      (node (ref "D9") (pin "2") (pinfunction "A_2") (pintype "input"))
      (node (ref "IC1") (pin "4") (pinfunction "V-_4") (pintype "power_in"))
      (node (ref "IC11") (pin "13") (pinfunction "VA-_13") (pintype "bidirectional"))
      (node (ref "IC16") (pin "4") (pinfunction "V-_4") (pintype "power_in"))
      (node (ref "IC3") (pin "13") (pinfunction "VA-_13") (pintype "bidirectional"))
      (node (ref "IC4") (pin "4") (pinfunction "V-_4") (pintype "power_in"))
      (node (ref "IC5") (pin "4") (pinfunction "V-_4") (pintype "power_in"))
      (node (ref "IC8") (pin "4") (pinfunction "V-_4") (pintype "power_in"))
      (node (ref "IC9") (pin "4") (pinfunction "V-_4") (pintype "power_in"))
      (node (ref "IN_LEFT") (pin "4") (pinfunction "V-_4") (pintype "power_in"))
      (node (ref "IN_RIGHT") (pin "4") (pinfunction "V-_4") (pintype "power_in"))
      (node (ref "OUT_LEFT") (pin "5") (pinfunction "V-_5") (pintype "power_in"))
      (node (ref "OUT_RIGHT") (pin "5") (pinfunction "V-_5") (pintype "power_in"))
      (node (ref "R40") (pin "1") (pinfunction "1_1") (pintype "passive"))
      (node (ref "R43") (pin "1") (pinfunction "1_1") (pintype "passive"))
      (node (ref "R50") (pin "1") (pinfunction "1_1") (pintype "passive"))
      (node (ref "R51") (pin "1") (pinfunction "1_1") (pintype "passive"))
      (node (ref "R97") (pin "1") (pinfunction "1_1") (pintype "passive"))
      (node (ref "U4") (pin "4") (pinfunction "V-_4") (pintype "power_in"))
      (node (ref "U6") (pin "4") (pinfunction "V-_4") (pintype "power_in"))
      (node (ref "U7") (pin "4") (pinfunction "V-_4") (pintype "power_in"))
      (node (ref "U8") (pin "4") (pinfunction "V-_4") (pintype "power_in"))
    )
    (net (code "243") (name "ZCEN") (class "Default")
      (node (ref "IC10") (pin "80") (pinfunction "PD11_80") (pintype "bidirectional"))
      (node (ref "R30") (pin "2") (pinfunction "2_2") (pintype "passive"))
    )
    (net (code "244") (name "unconnected-(DIGITAL_VOLT-Pad2)") (class "Default")
      (node (ref "DIGITAL_VOLT") (pin "2") (pinfunction "2_2") (pintype "bidirectional"))
    )
    (net (code "245") (name "unconnected-(IC3-SDO-Pad7)") (class "Default")
      (node (ref "IC3") (pin "7") (pinfunction "SDO_7") (pintype "bidirectional"))
    )
    (net (code "246") (name "unconnected-(IC10-PA15-Pad110)") (class "Default")
      (node (ref "IC10") (pin "110") (pinfunction "PA15_110") (pintype "bidirectional"))
    )
    (net (code "247") (name "unconnected-(IC10-PB2-Pad48)") (class "Default")
      (node (ref "IC10") (pin "48") (pinfunction "PB2_48") (pintype "bidirectional"))
    )
    (net (code "248") (name "unconnected-(IC10-PB3-Pad133)") (class "Default")
      (node (ref "IC10") (pin "133") (pinfunction "PB3_133") (pintype "bidirectional"))
    )
    (net (code "249") (name "unconnected-(IC10-PB8-Pad139)") (class "Default")
      (node (ref "IC10") (pin "139") (pinfunction "PB8_139") (pintype "bidirectional"))
    )
    (net (code "250") (name "unconnected-(IC10-PB9-Pad140)") (class "Default")
      (node (ref "IC10") (pin "140") (pinfunction "PB9_140") (pintype "bidirectional"))
    )
    (net (code "251") (name "unconnected-(IC10-PB11-Pad70)") (class "Default")
      (node (ref "IC10") (pin "70") (pinfunction "PB11_70") (pintype "bidirectional"))
    )
    (net (code "252") (name "unconnected-(IC10-PC2-Pad28)") (class "Default")
      (node (ref "IC10") (pin "28") (pinfunction "PC2_28") (pintype "bidirectional"))
    )
    (net (code "253") (name "unconnected-(IC10-PC13-Pad7)") (class "Default")
      (node (ref "IC10") (pin "7") (pinfunction "PC13_7") (pintype "bidirectional"))
    )
    (net (code "254") (name "unconnected-(IC10-PD0-Pad114)") (class "Default")
      (node (ref "IC10") (pin "114") (pinfunction "PD0_114") (pintype "bidirectional"))
    )
    (net (code "255") (name "unconnected-(IC10-PD3-Pad117)") (class "Default")
      (node (ref "IC10") (pin "117") (pinfunction "PD3_117") (pintype "bidirectional"))
    )
    (net (code "256") (name "unconnected-(IC10-PD4-Pad118)") (class "Default")
      (node (ref "IC10") (pin "118") (pinfunction "PD4_118") (pintype "bidirectional"))
    )
    (net (code "257") (name "unconnected-(IC10-PD5-Pad119)") (class "Default")
      (node (ref "IC10") (pin "119") (pinfunction "PD5_119") (pintype "bidirectional"))
    )
    (net (code "258") (name "unconnected-(IC10-PD13-Pad82)") (class "Default")
      (node (ref "IC10") (pin "82") (pinfunction "PD13_82") (pintype "bidirectional"))
    )
    (net (code "259") (name "unconnected-(IC10-PD14-Pad85)") (class "Default")
      (node (ref "IC10") (pin "85") (pinfunction "PD14_85") (pintype "bidirectional"))
    )
    (net (code "260") (name "unconnected-(IC10-PD15-Pad86)") (class "Default")
      (node (ref "IC10") (pin "86") (pinfunction "PD15_86") (pintype "bidirectional"))
    )
    (net (code "261") (name "unconnected-(IC10-PF0-Pad10)") (class "Default")
      (node (ref "IC10") (pin "10") (pinfunction "PF0_10") (pintype "bidirectional"))
    )
    (net (code "262") (name "unconnected-(IC10-PF1-Pad11)") (class "Default")
      (node (ref "IC10") (pin "11") (pinfunction "PF1_11") (pintype "bidirectional"))
    )
    (net (code "263") (name "unconnected-(IC10-PF2-Pad12)") (class "Default")
      (node (ref "IC10") (pin "12") (pinfunction "PF2_12") (pintype "bidirectional"))
    )
    (net (code "264") (name "unconnected-(IC10-PF3-Pad13)") (class "Default")
      (node (ref "IC10") (pin "13") (pinfunction "PF3_13") (pintype "bidirectional"))
    )
    (net (code "265") (name "unconnected-(IC10-PF4-Pad14)") (class "Default")
      (node (ref "IC10") (pin "14") (pinfunction "PF4_14") (pintype "bidirectional"))
    )
    (net (code "266") (name "unconnected-(IC10-PF5-Pad15)") (class "Default")
      (node (ref "IC10") (pin "15") (pinfunction "PF5_15") (pintype "bidirectional"))
    )
    (net (code "267") (name "unconnected-(IC10-PF6-Pad18)") (class "Default")
      (node (ref "IC10") (pin "18") (pinfunction "PF6_18") (pintype "bidirectional"))
    )
    (net (code "268") (name "unconnected-(IC10-PF7-Pad19)") (class "Default")
      (node (ref "IC10") (pin "19") (pinfunction "PF7_19") (pintype "bidirectional"))
    )
    (net (code "269") (name "unconnected-(IC10-PF8-Pad20)") (class "Default")
      (node (ref "IC10") (pin "20") (pinfunction "PF8_20") (pintype "bidirectional"))
    )
    (net (code "270") (name "unconnected-(IC10-PF10-Pad22)") (class "Default")
      (node (ref "IC10") (pin "22") (pinfunction "PF10_22") (pintype "bidirectional"))
    )
    (net (code "271") (name "unconnected-(IC10-PF11-Pad49)") (class "Default")
      (node (ref "IC10") (pin "49") (pinfunction "PF11_49") (pintype "bidirectional"))
    )
    (net (code "272") (name "unconnected-(IC10-PF12-Pad50)") (class "Default")
      (node (ref "IC10") (pin "50") (pinfunction "PF12_50") (pintype "bidirectional"))
    )
    (net (code "273") (name "unconnected-(IC10-PF13-Pad53)") (class "Default")
      (node (ref "IC10") (pin "53") (pinfunction "PF13_53") (pintype "bidirectional"))
    )
    (net (code "274") (name "unconnected-(IC10-PF14-Pad54)") (class "Default")
      (node (ref "IC10") (pin "54") (pinfunction "PF14_54") (pintype "bidirectional"))
    )
    (net (code "275") (name "unconnected-(IC10-PF15-Pad55)") (class "Default")
      (node (ref "IC10") (pin "55") (pinfunction "PF15_55") (pintype "bidirectional"))
    )
    (net (code "276") (name "unconnected-(IC10-PG4-Pad89)") (class "Default")
      (node (ref "IC10") (pin "89") (pinfunction "PG4_89") (pintype "bidirectional"))
    )
    (net (code "277") (name "unconnected-(IC10-PG5-Pad90)") (class "Default")
      (node (ref "IC10") (pin "90") (pinfunction "PG5_90") (pintype "bidirectional"))
    )
    (net (code "278") (name "unconnected-(IC10-PG8-Pad93)") (class "Default")
      (node (ref "IC10") (pin "93") (pinfunction "PG8_93") (pintype "bidirectional"))
    )
    (net (code "279") (name "unconnected-(IC10-PG14-Pad129)") (class "Default")
      (node (ref "IC10") (pin "129") (pinfunction "PG14_129") (pintype "bidirectional"))
    )
    (net (code "280") (name "unconnected-(IC11-SDO-Pad7)") (class "Default")
      (node (ref "IC11") (pin "7") (pinfunction "SDO_7") (pintype "bidirectional"))
    )
    (net (code "281") (name "unconnected-(IC12-Pad4)") (class "Default")
      (node (ref "IC12") (pin "4") (pinfunction "4_4") (pintype "bidirectional"))
    )
    (net (code "282") (name "unconnected-(J1-Pad4)") (class "Default")
      (node (ref "J1") (pin "4") (pinfunction "4_4") (pintype "bidirectional"))
    )
    (net (code "283") (name "unconnected-(J1-Pad5)") (class "Default")
      (node (ref "J1") (pin "5") (pinfunction "5_5") (pintype "bidirectional"))
    )
    (net (code "284") (name "unconnected-(K7C-O-PadQ2)") (class "Default")
      (node (ref "K7") (pin "Q2") (pinfunction "O_Q2") (pintype "passive"))
    )
    (net (code "285") (name "unconnected-(K7C-P-PadP2)") (class "Default")
      (node (ref "K7") (pin "P2") (pinfunction "P_P2") (pintype "passive"))
    )
    (net (code "286") (name "unconnected-(K7C-S-PadS2)") (class "Default")
      (node (ref "K7") (pin "S2") (pinfunction "S_S2") (pintype "passive"))
    )
    (net (code "287") (name "unconnected-(K8C-O-PadQ2)") (class "Default")
      (node (ref "K8") (pin "Q2") (pinfunction "O_Q2") (pintype "passive"))
    )
    (net (code "288") (name "unconnected-(K8C-P-PadP2)") (class "Default")
      (node (ref "K8") (pin "P2") (pinfunction "P_P2") (pintype "passive"))
    )
    (net (code "289") (name "unconnected-(K8C-S-PadS2)") (class "Default")
      (node (ref "K8") (pin "S2") (pinfunction "S_S2") (pintype "passive"))
    )
    (net (code "290") (name "unconnected-(T1-NC_1-Pad4)") (class "Default")
      (node (ref "T1") (pin "4") (pinfunction "NC_1_4") (pintype "bidirectional"))
    )
    (net (code "291") (name "unconnected-(T1-NC_2-Pad5)") (class "Default")
      (node (ref "T1") (pin "5") (pinfunction "NC_2_5") (pintype "bidirectional"))
    )
    (net (code "292") (name "unconnected-(T1-NC_3-Pad10)") (class "Default")
      (node (ref "T1") (pin "10") (pinfunction "NC_3_10") (pintype "bidirectional"))
    )
    (net (code "293") (name "unconnected-(T1-NC_5-Pad13)") (class "Default")
      (node (ref "T1") (pin "13") (pinfunction "NC_5_13") (pintype "bidirectional"))
    )
    (net (code "294") (name "unconnected-(U12-IN7-Pad7)") (class "Default")
      (node (ref "U12") (pin "7") (pinfunction "IN7_7") (pintype "bidirectional"))
    )
    (net (code "295") (name "unconnected-(U12-OUT7-Pad10)") (class "Default")
      (node (ref "U12") (pin "10") (pinfunction "OUT7_10") (pintype "bidirectional"))
    )
  )
)
